# motherboard_schematic_ver_1_0.net
KiCad netlist of a schematic drawn in EAGLE
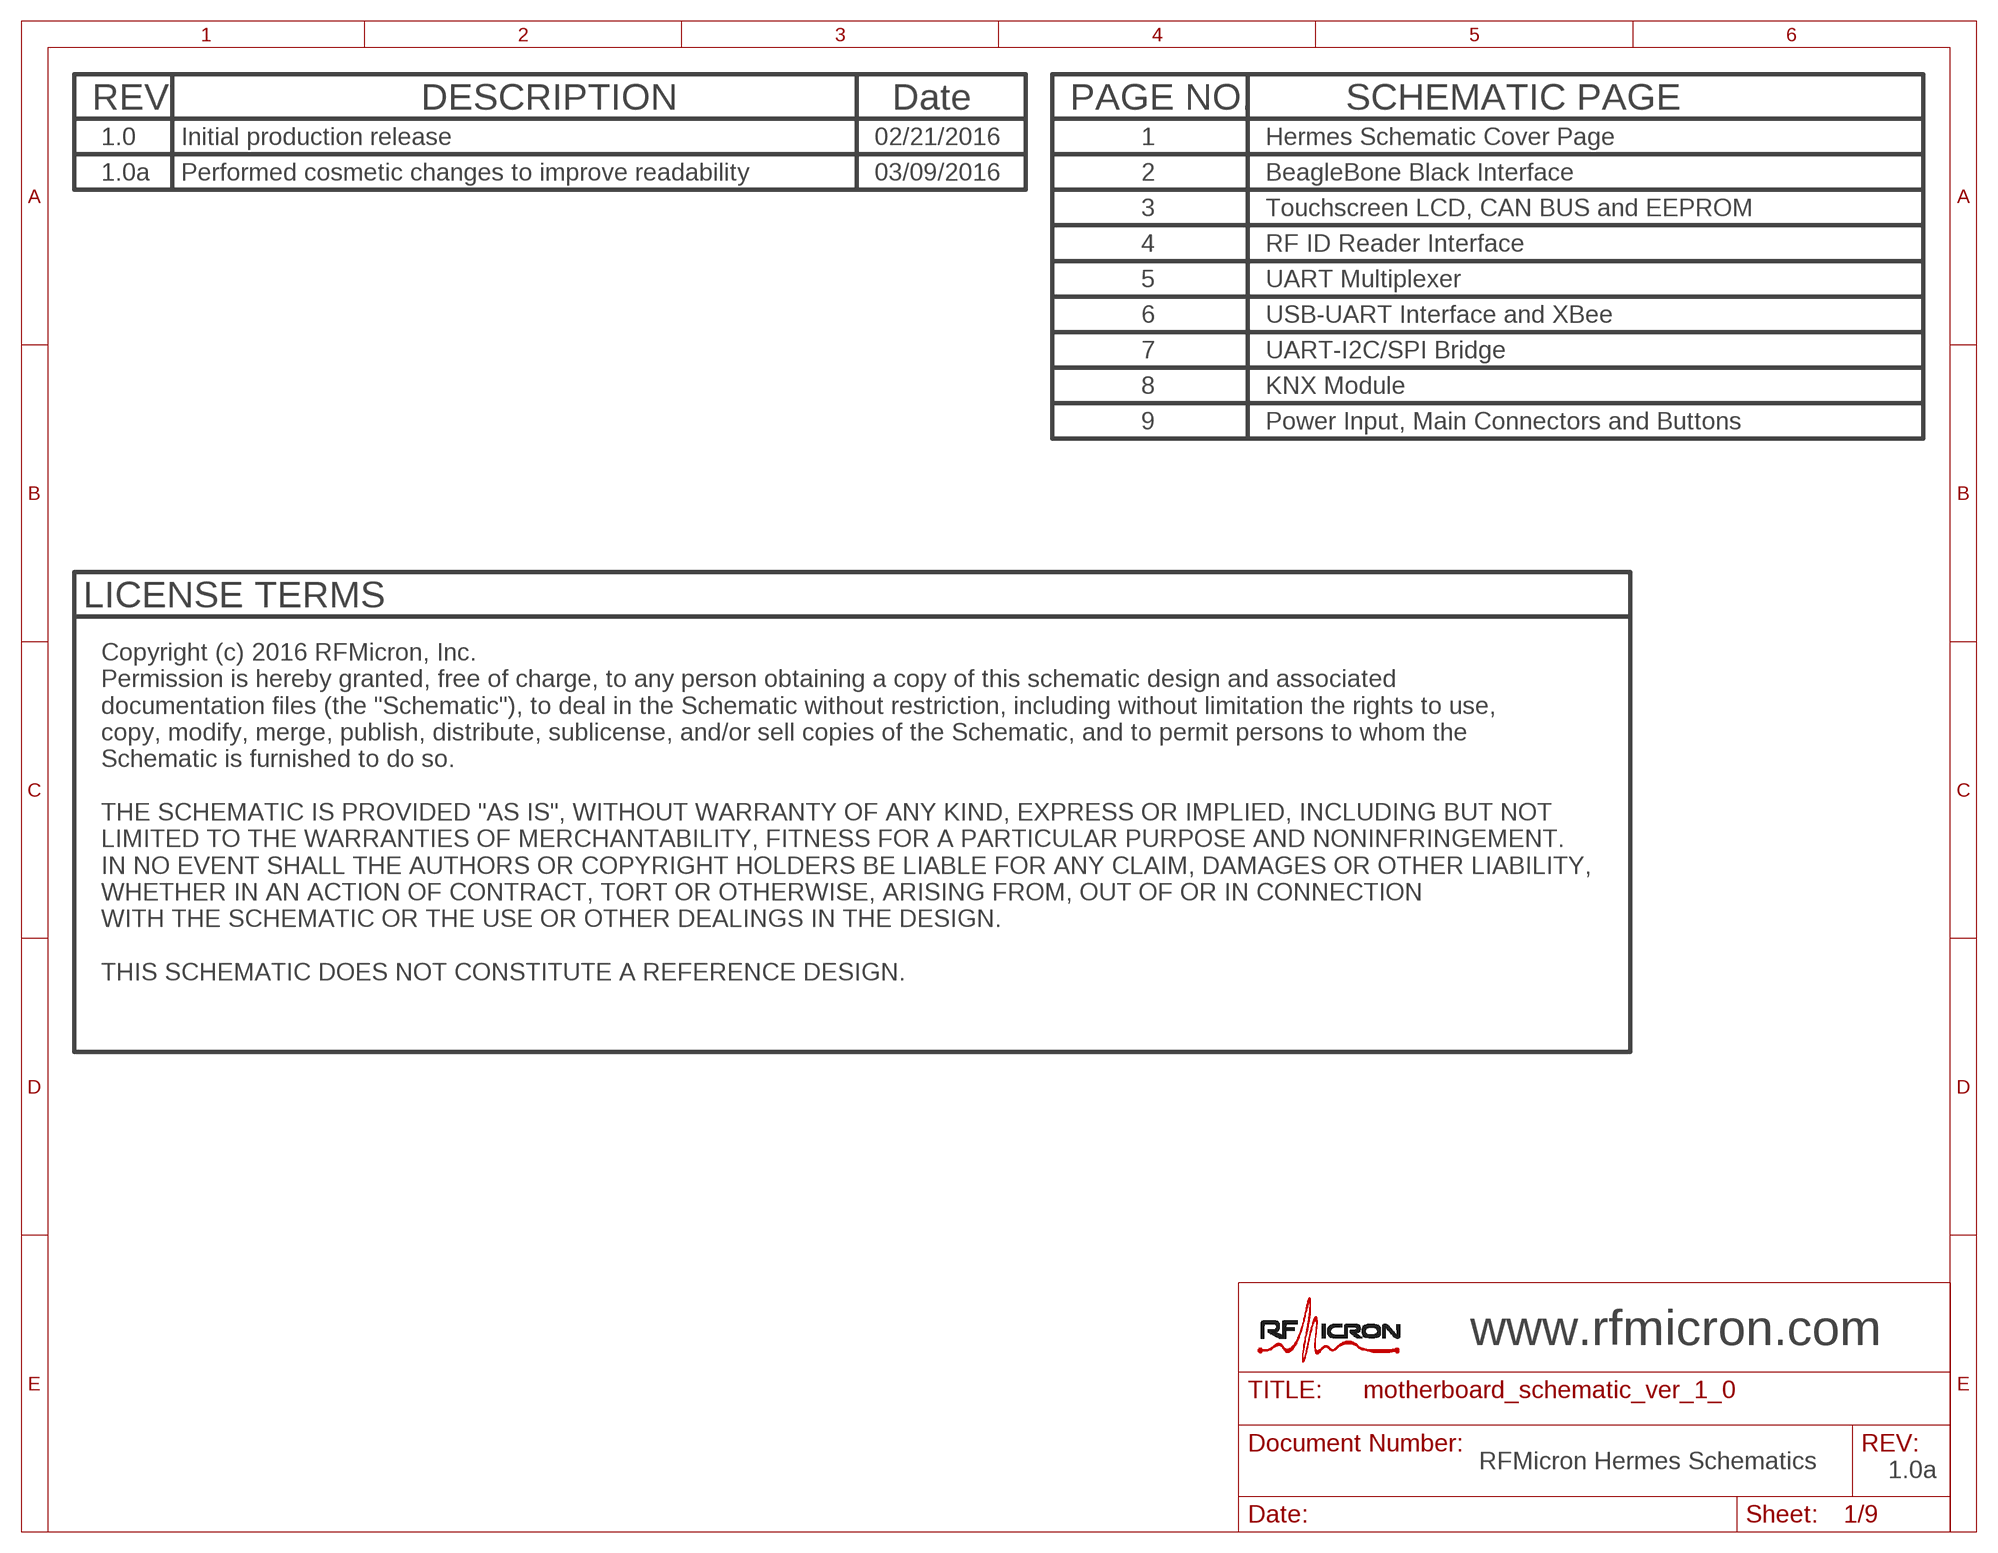
[diagram p0: schematic, sheet 1]
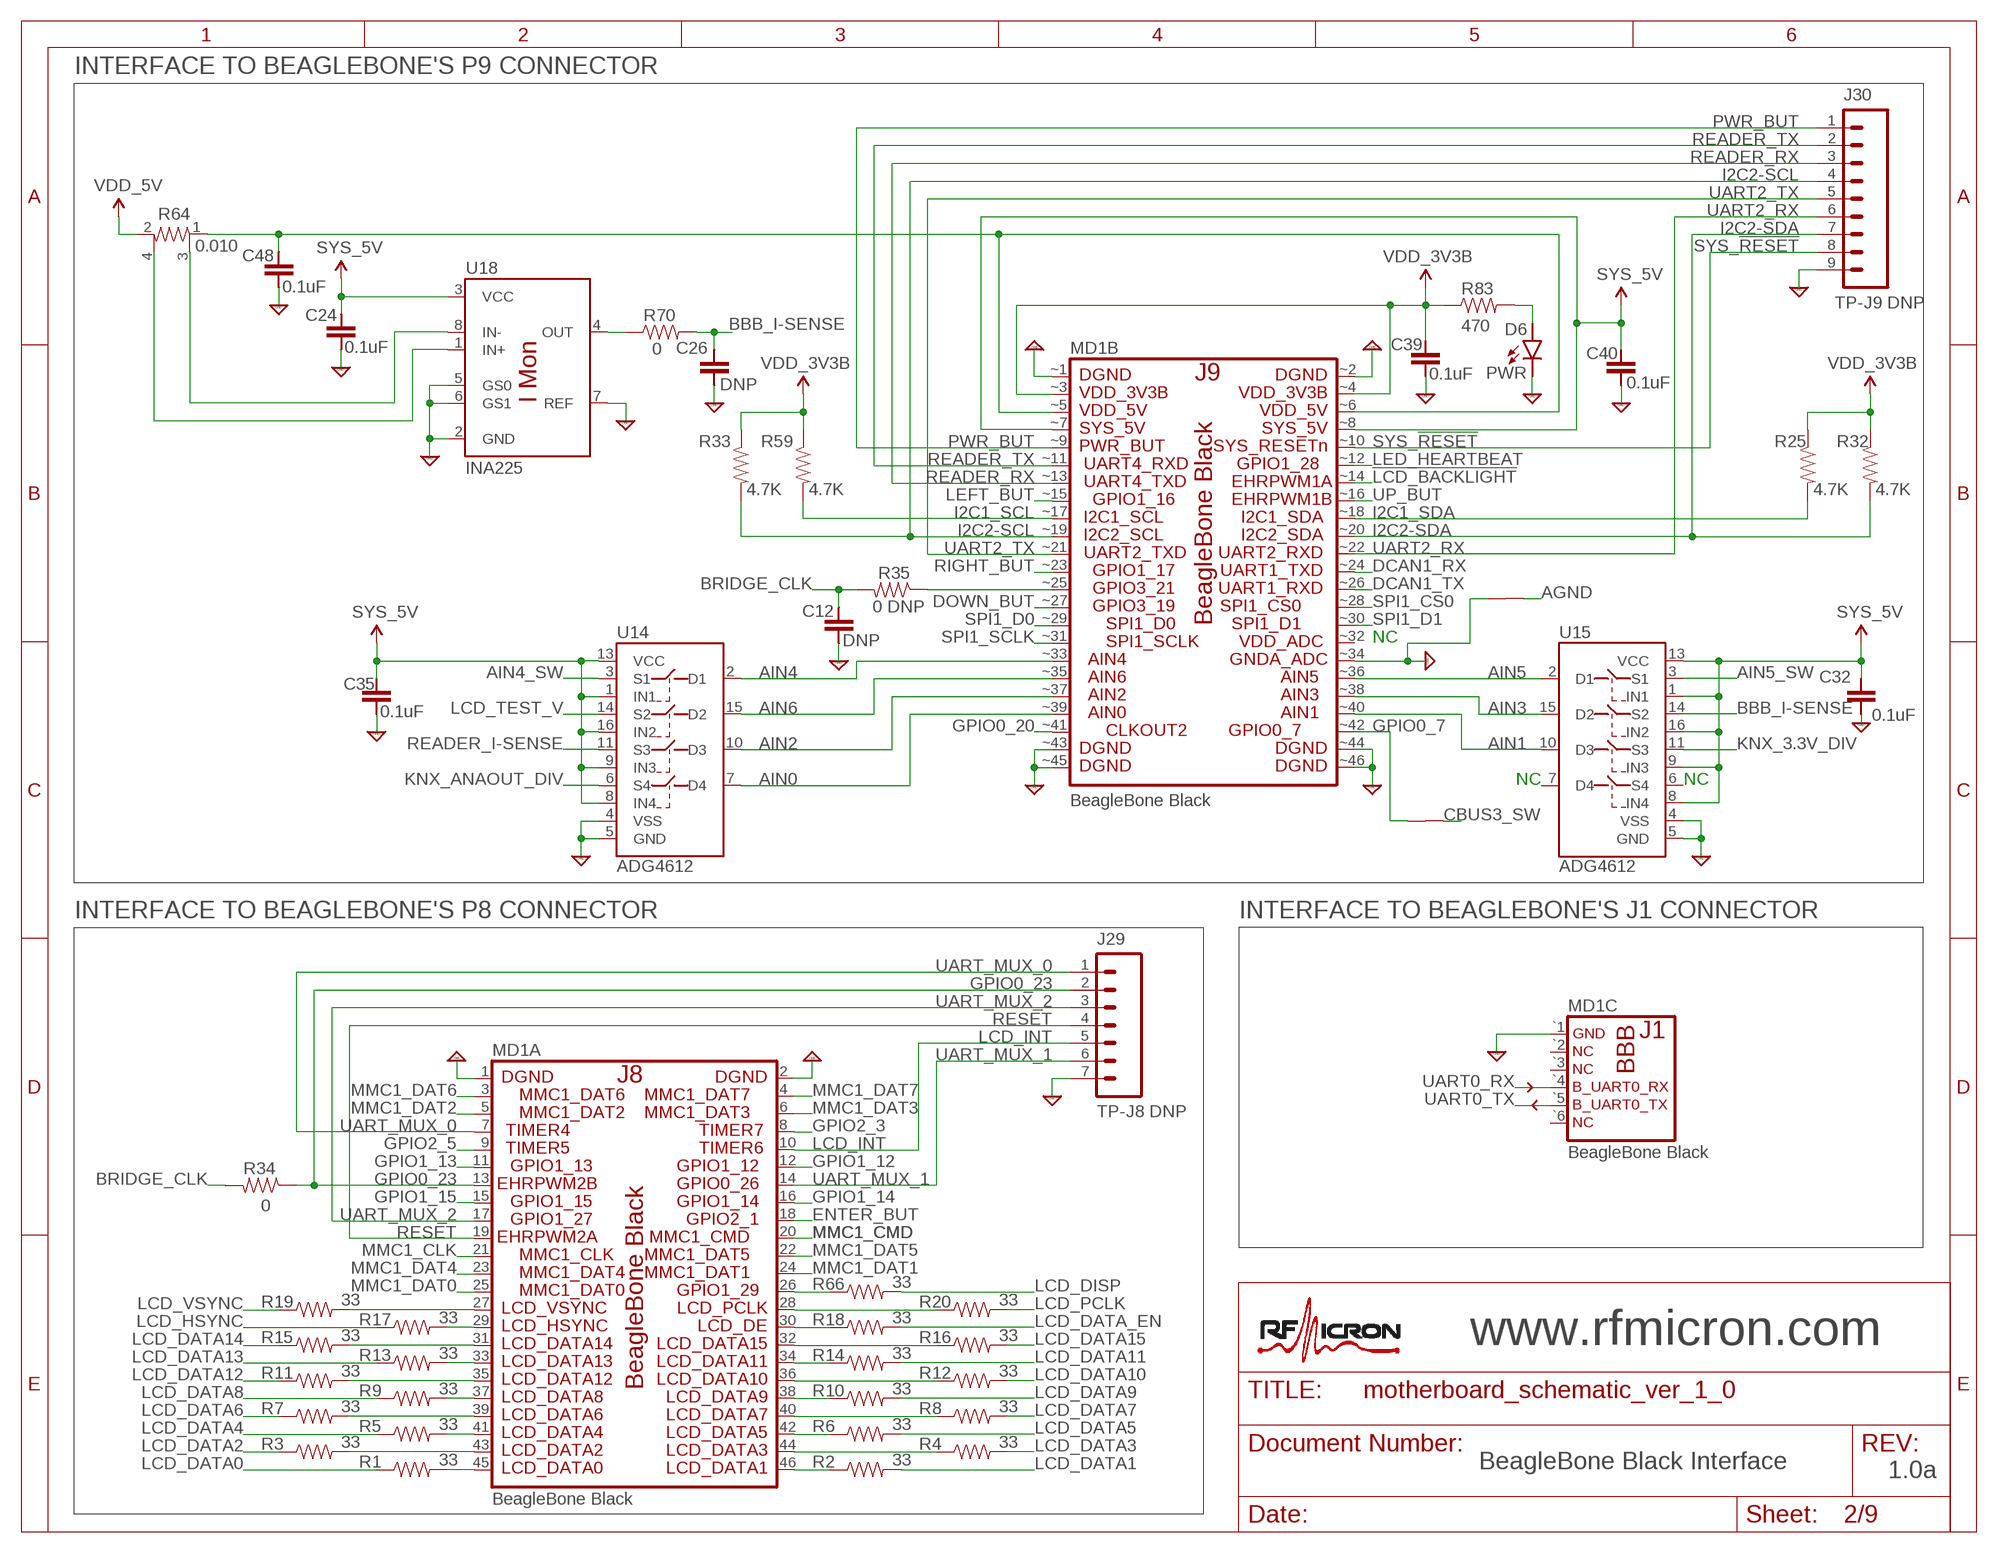
[diagram p1: schematic, sheet 2]
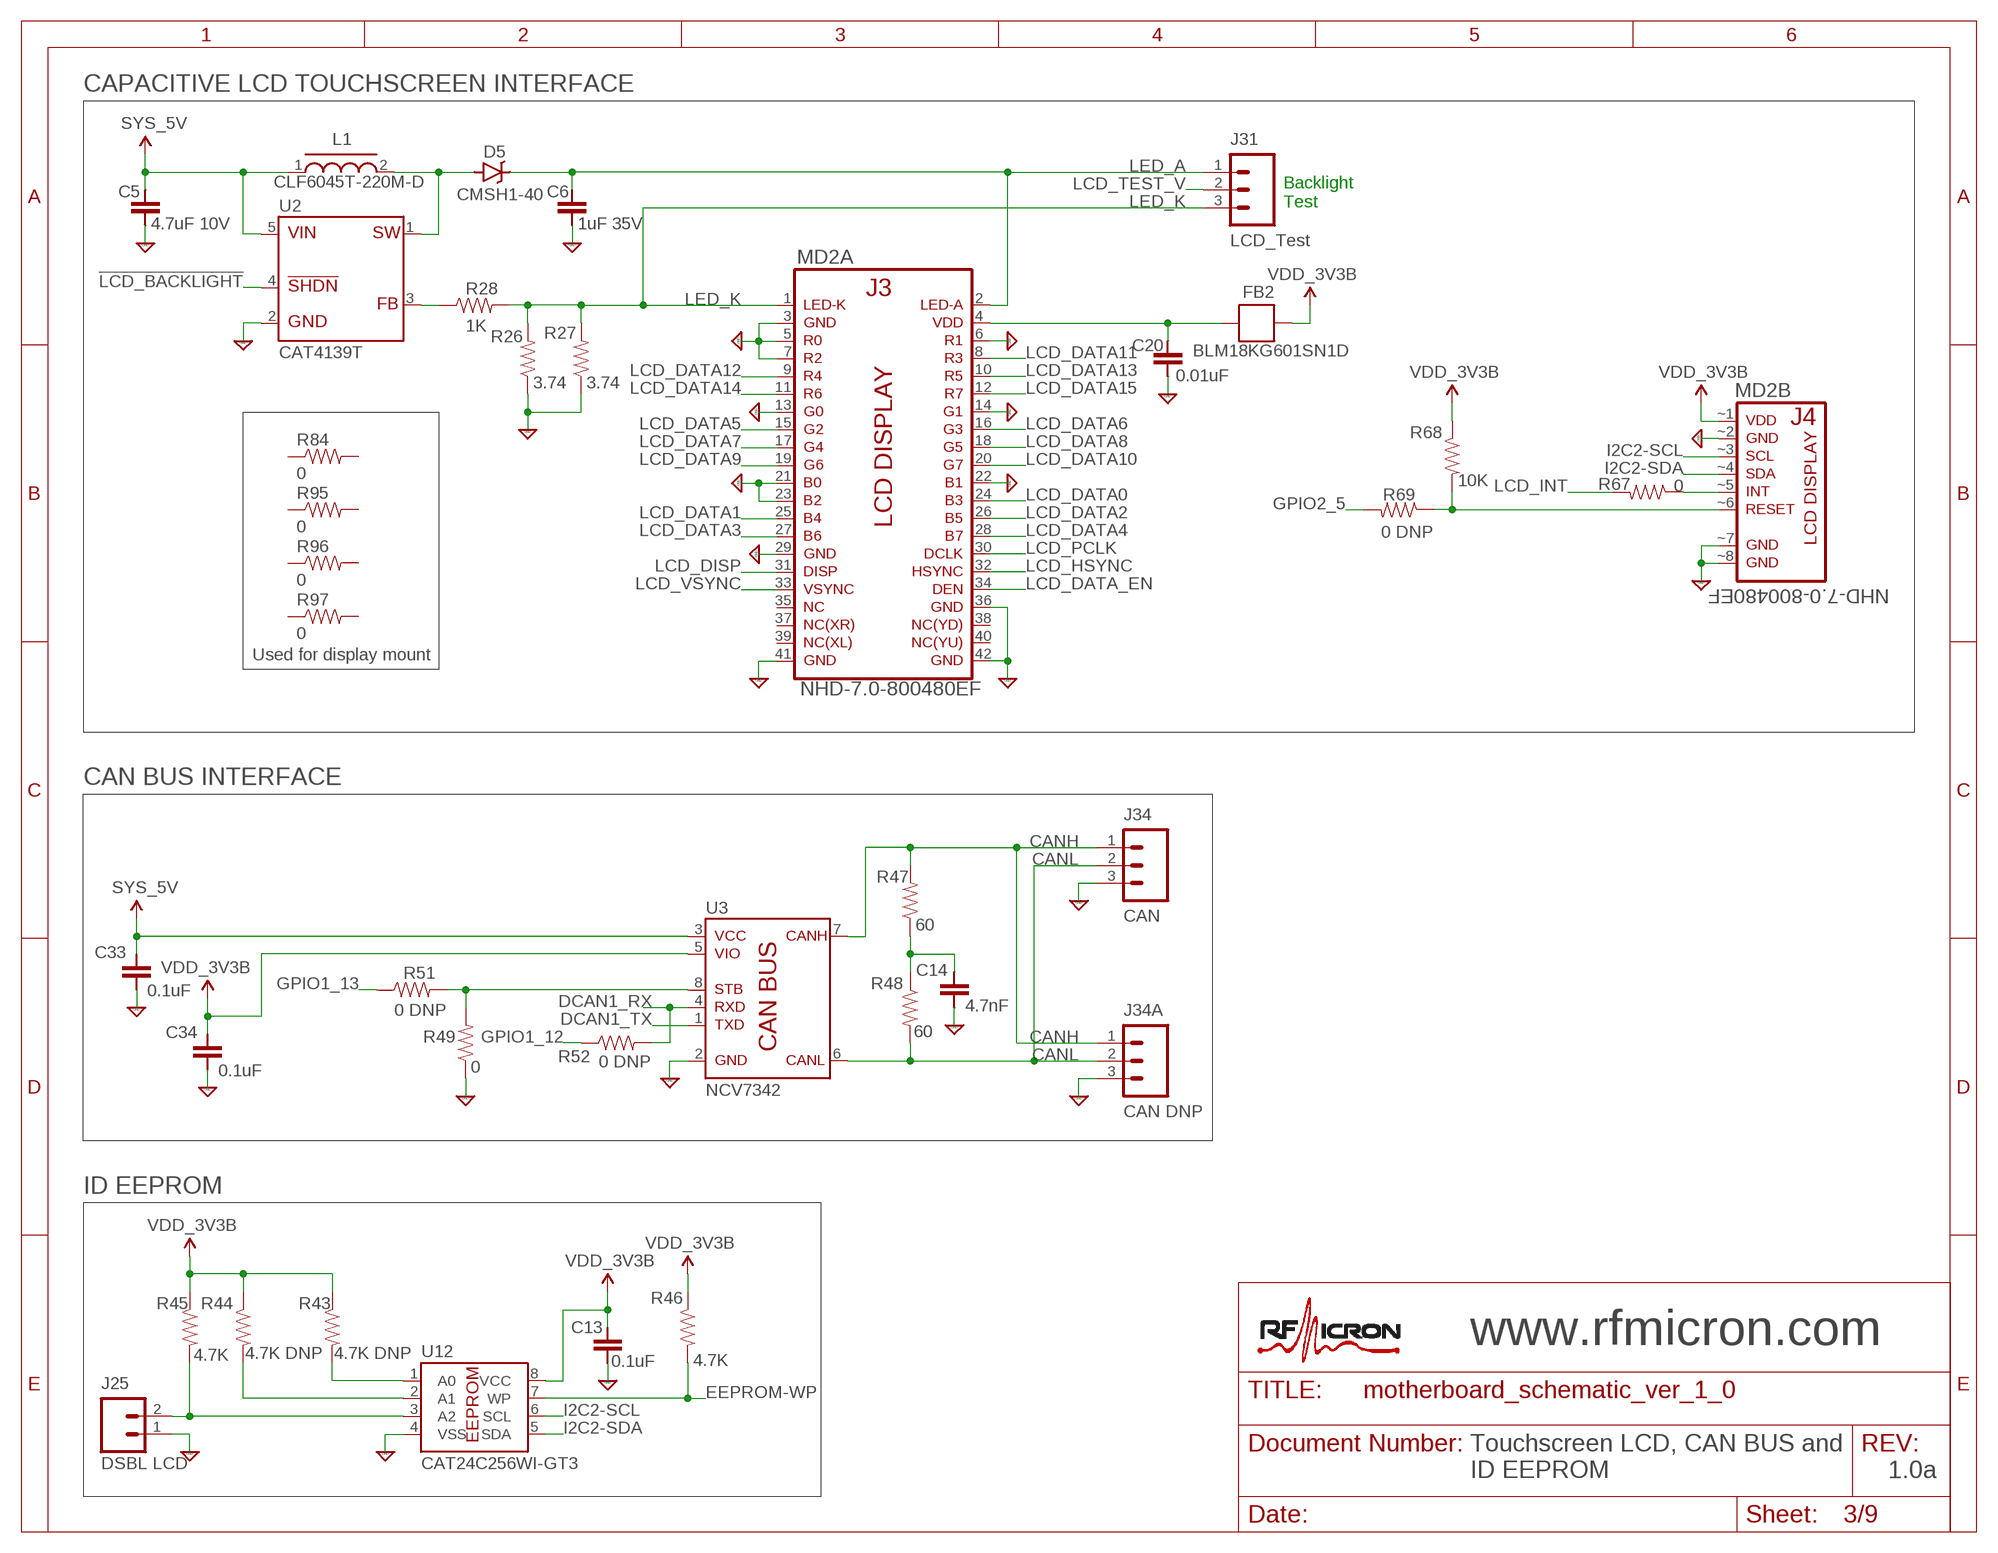
[diagram p2: schematic, sheet 3]
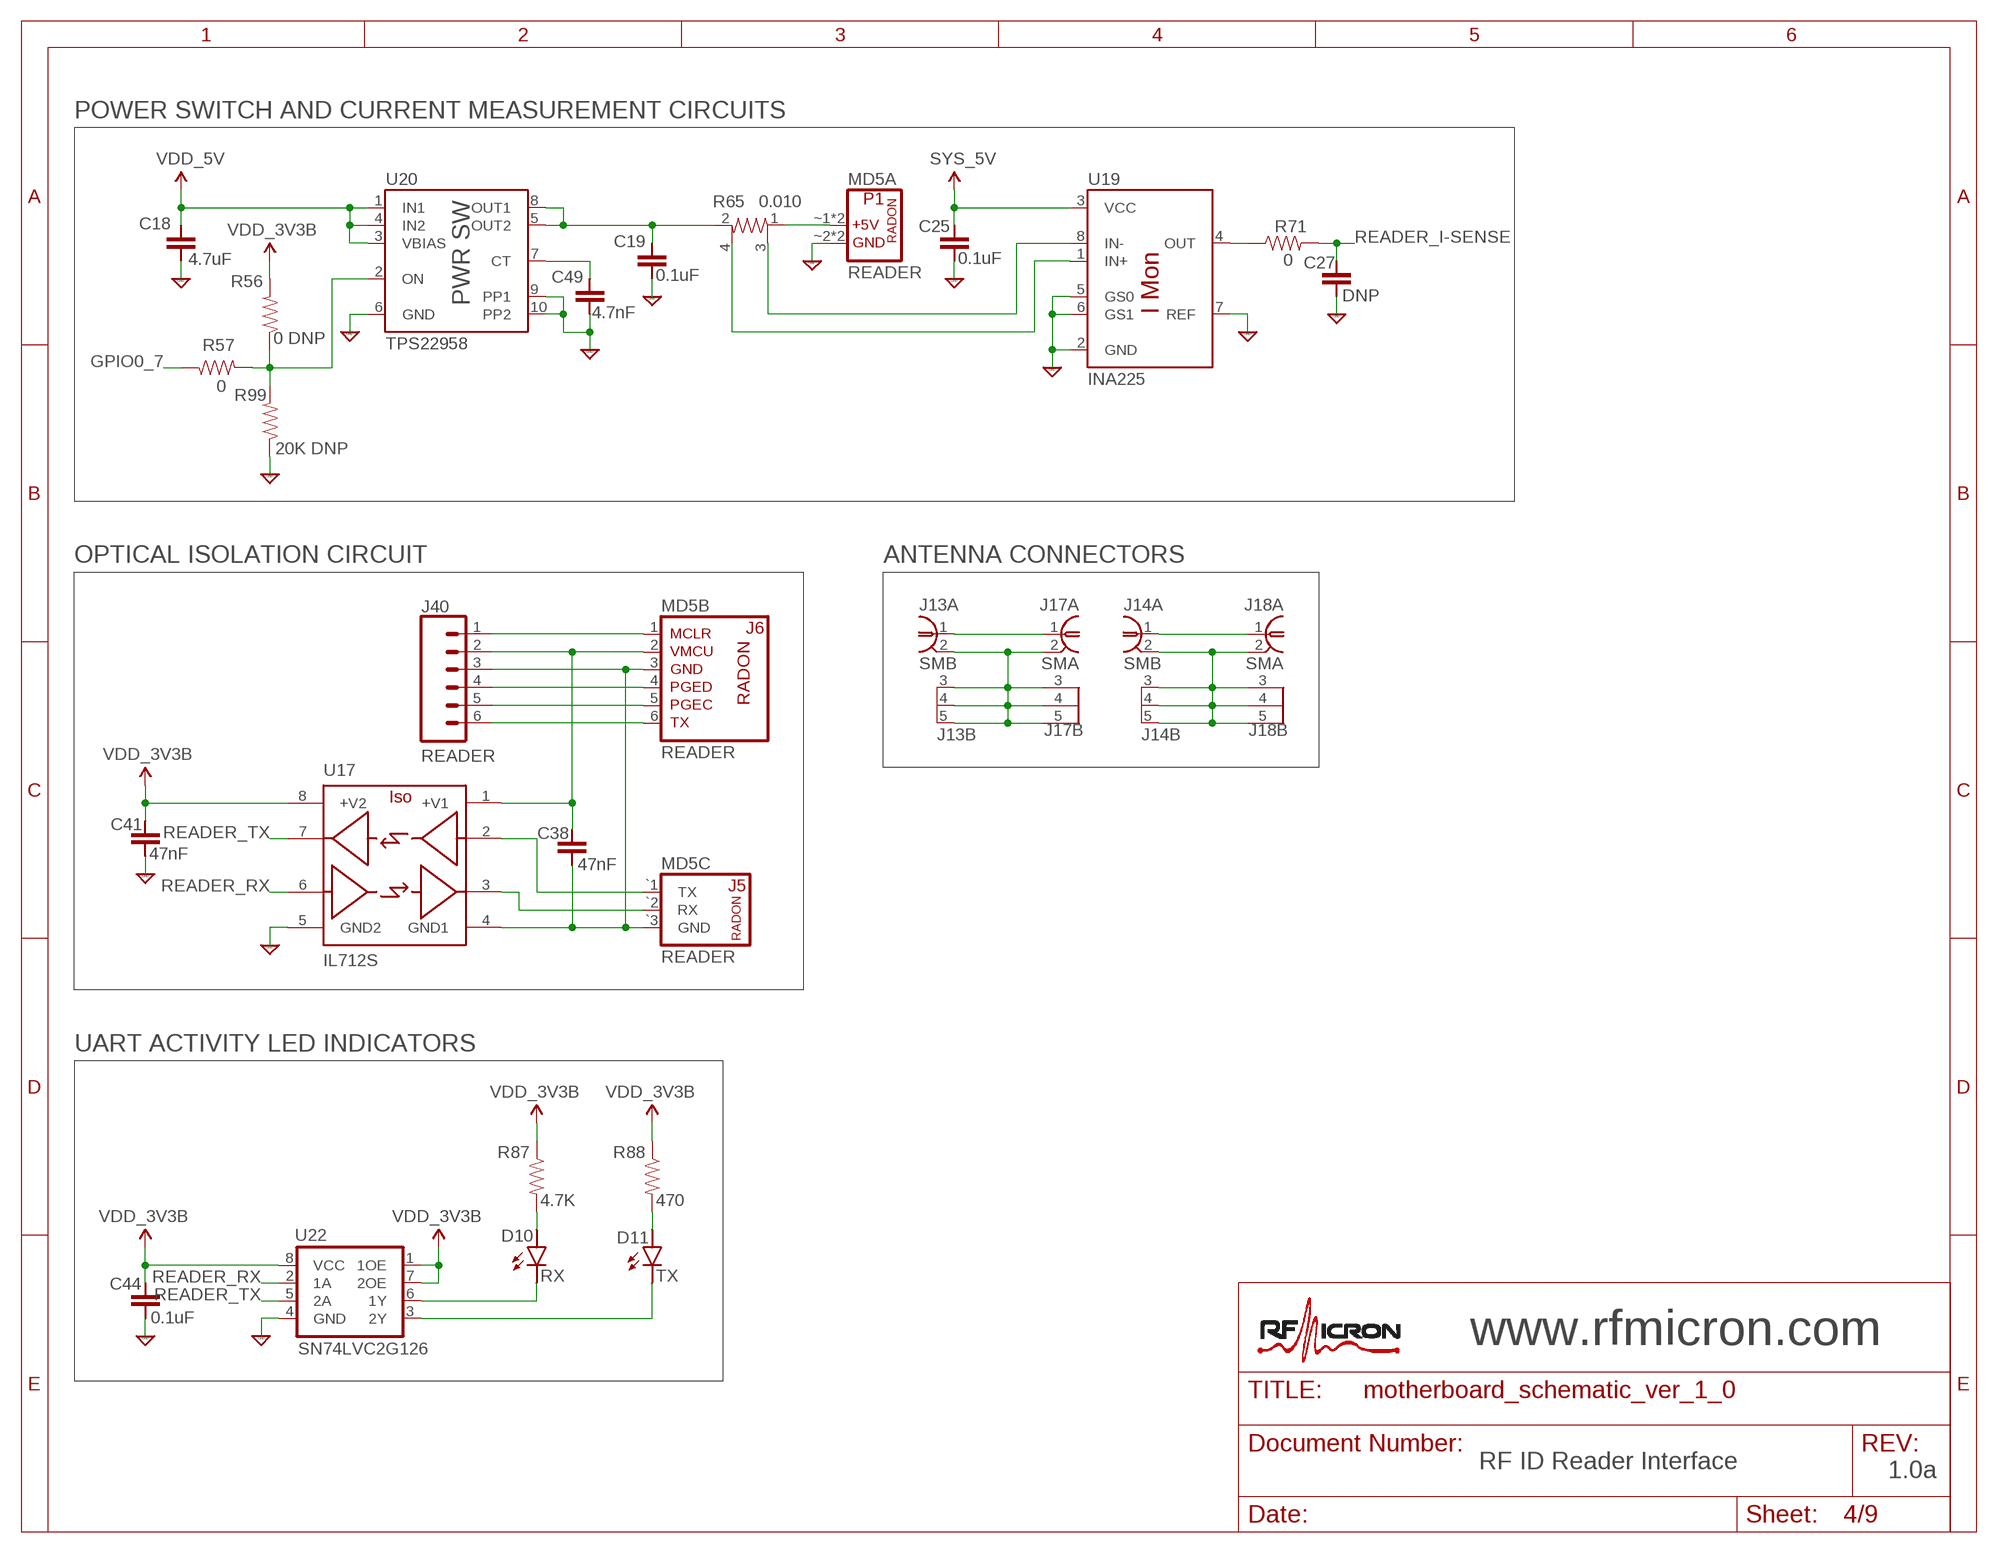
[diagram p3: schematic, sheet 4]
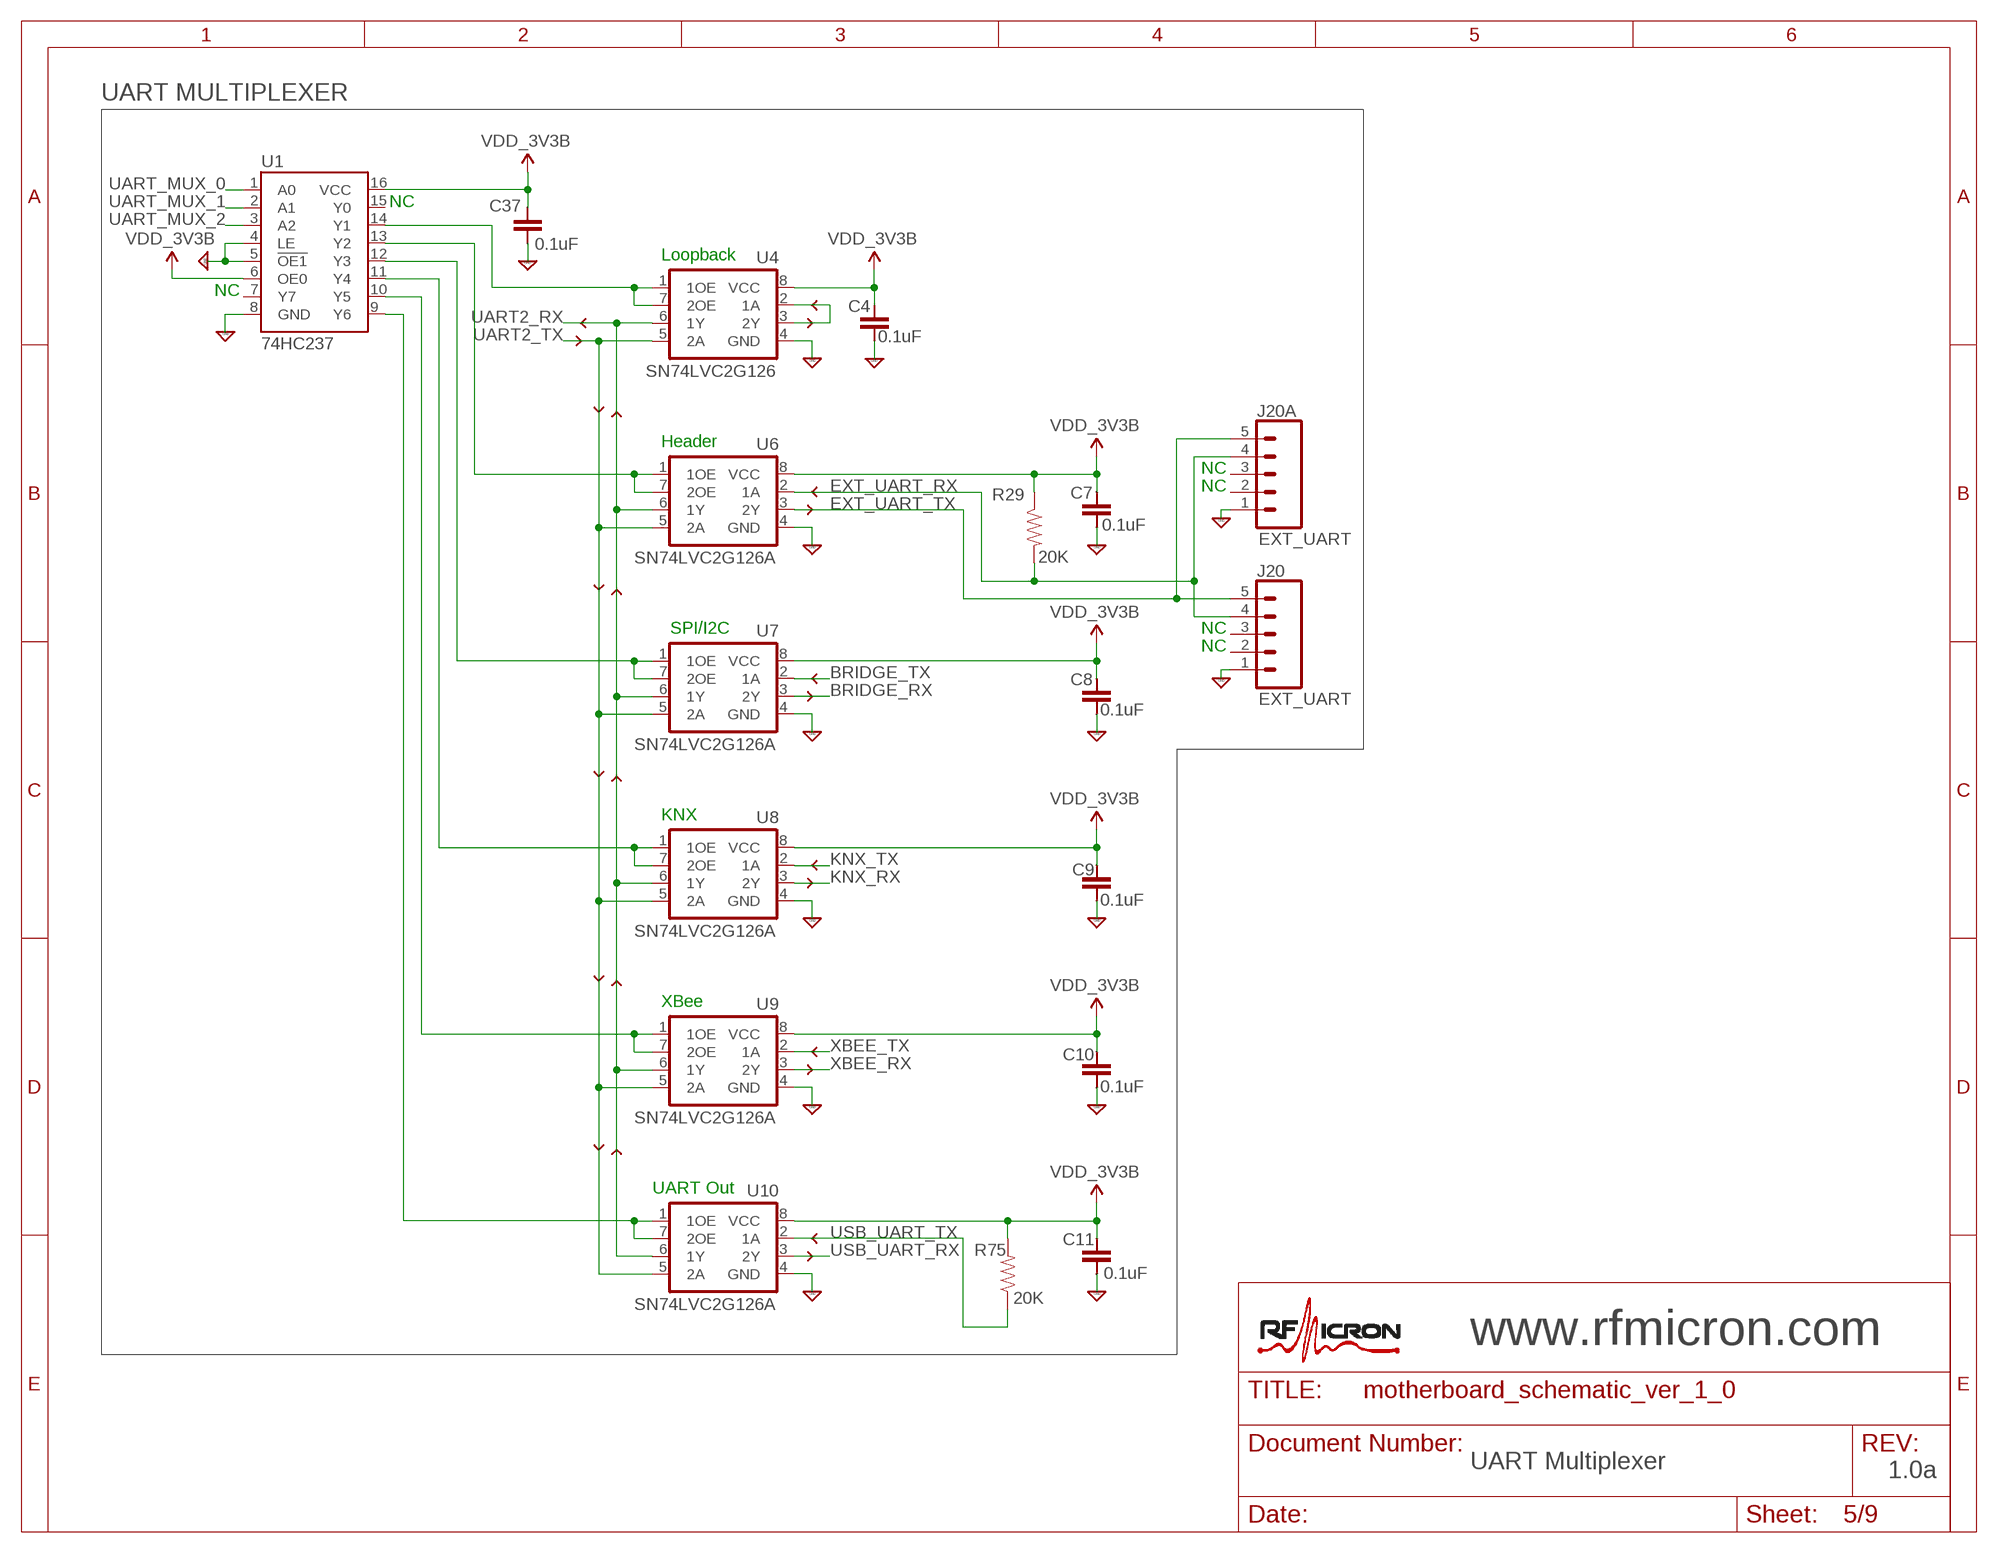
[diagram p4: schematic, sheet 5]
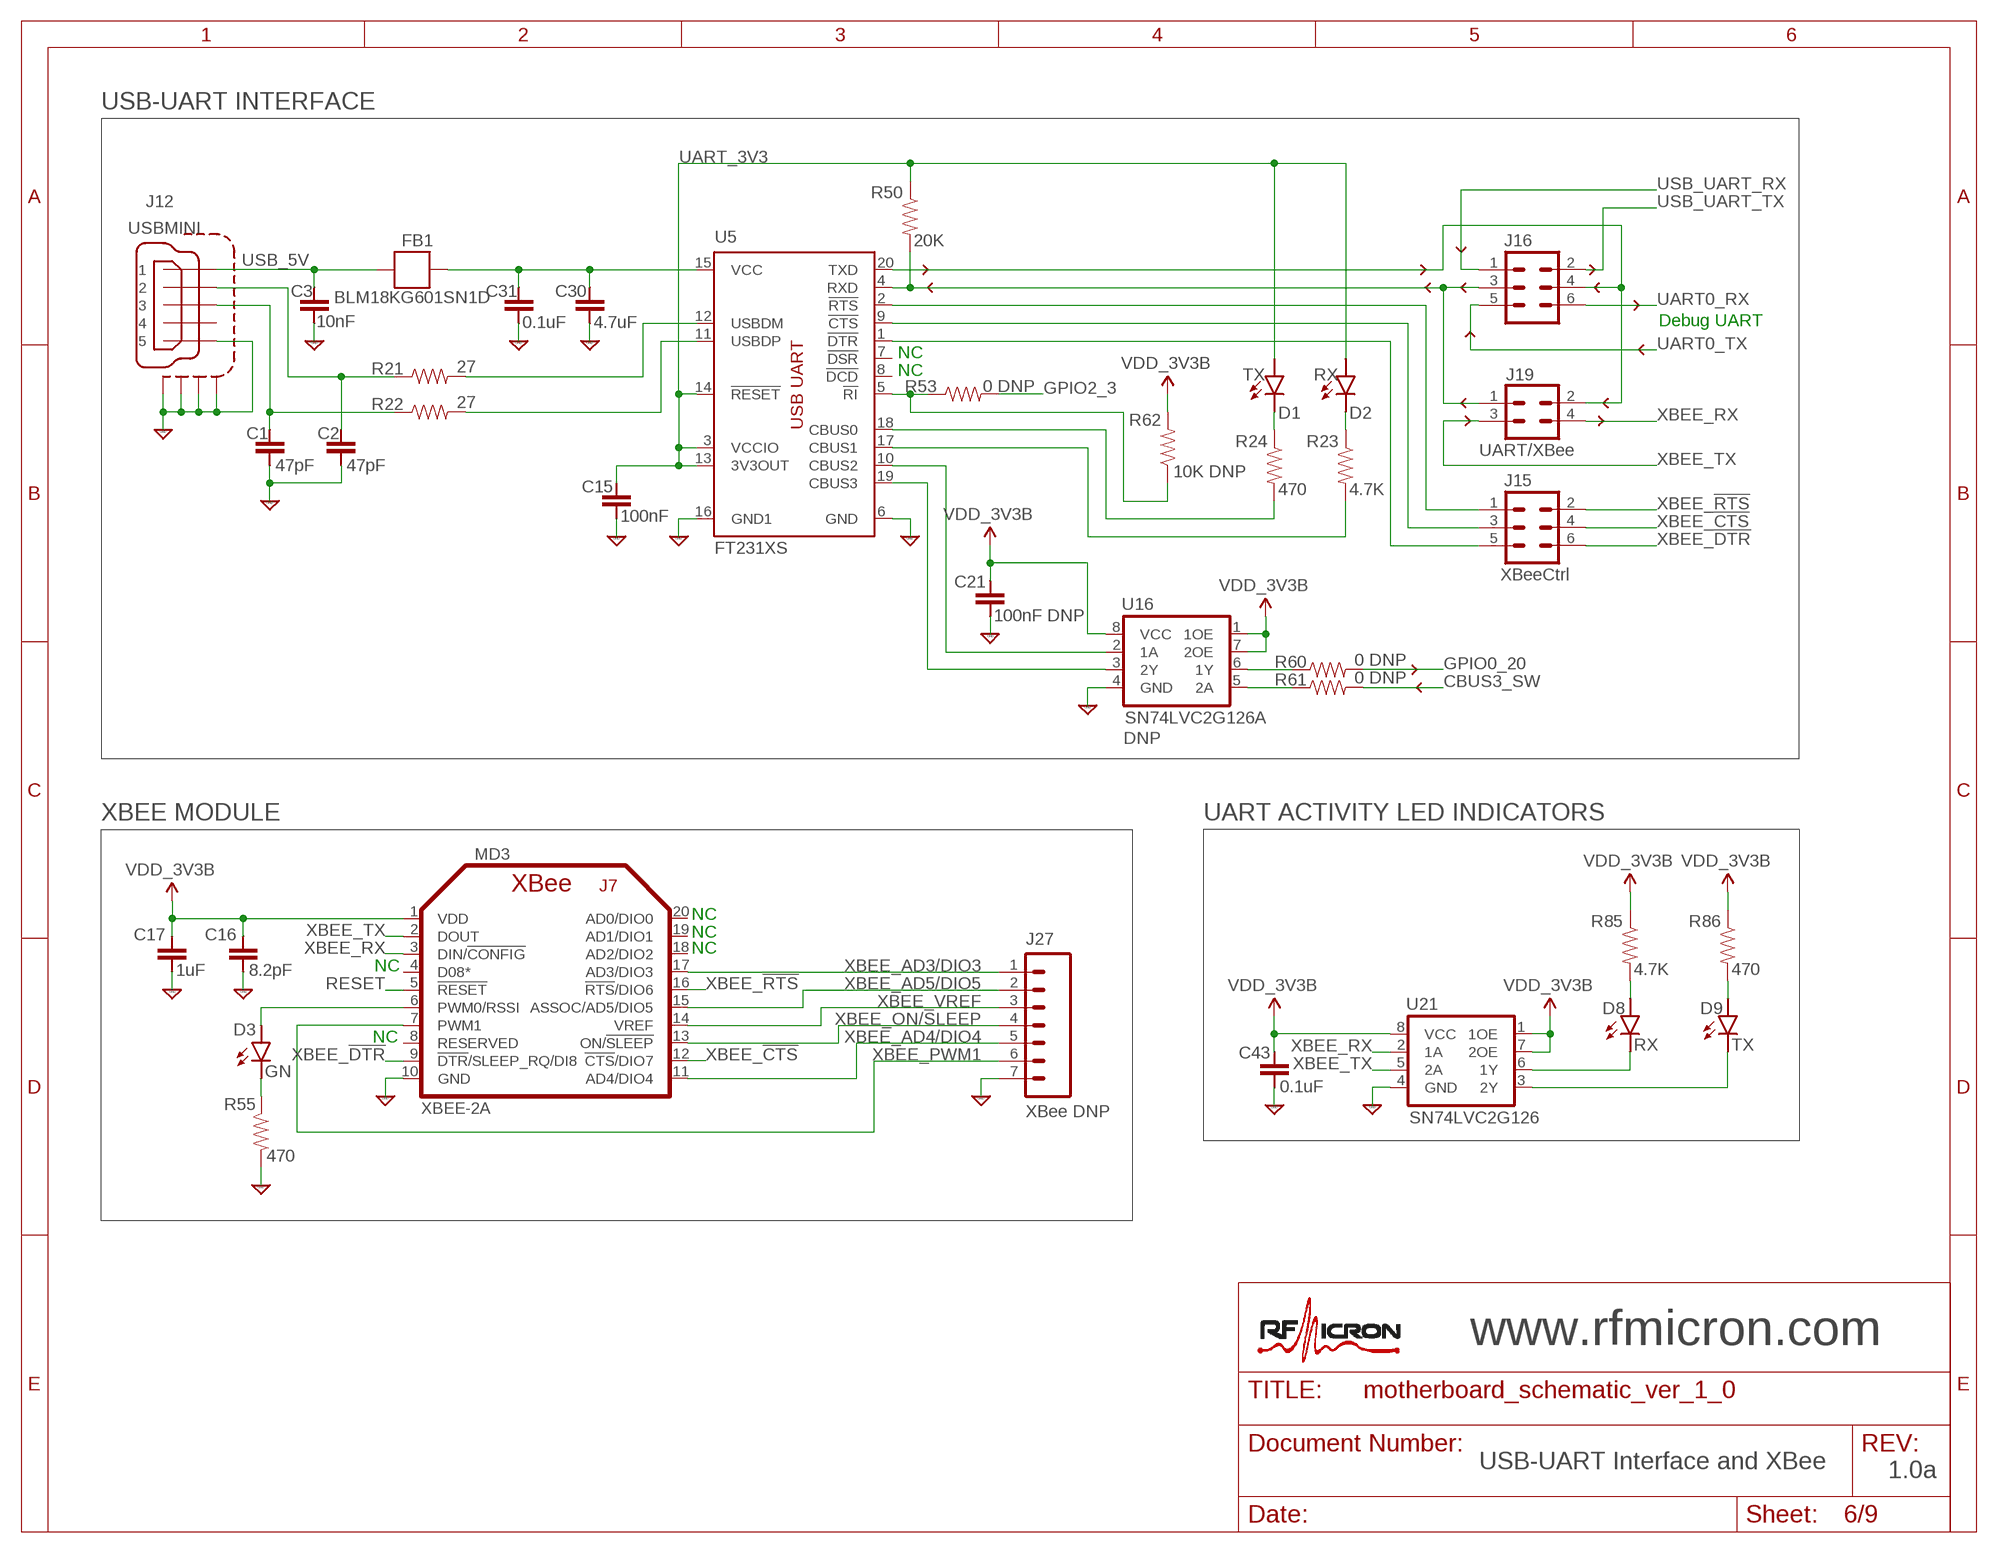
[diagram p5: schematic, sheet 6]
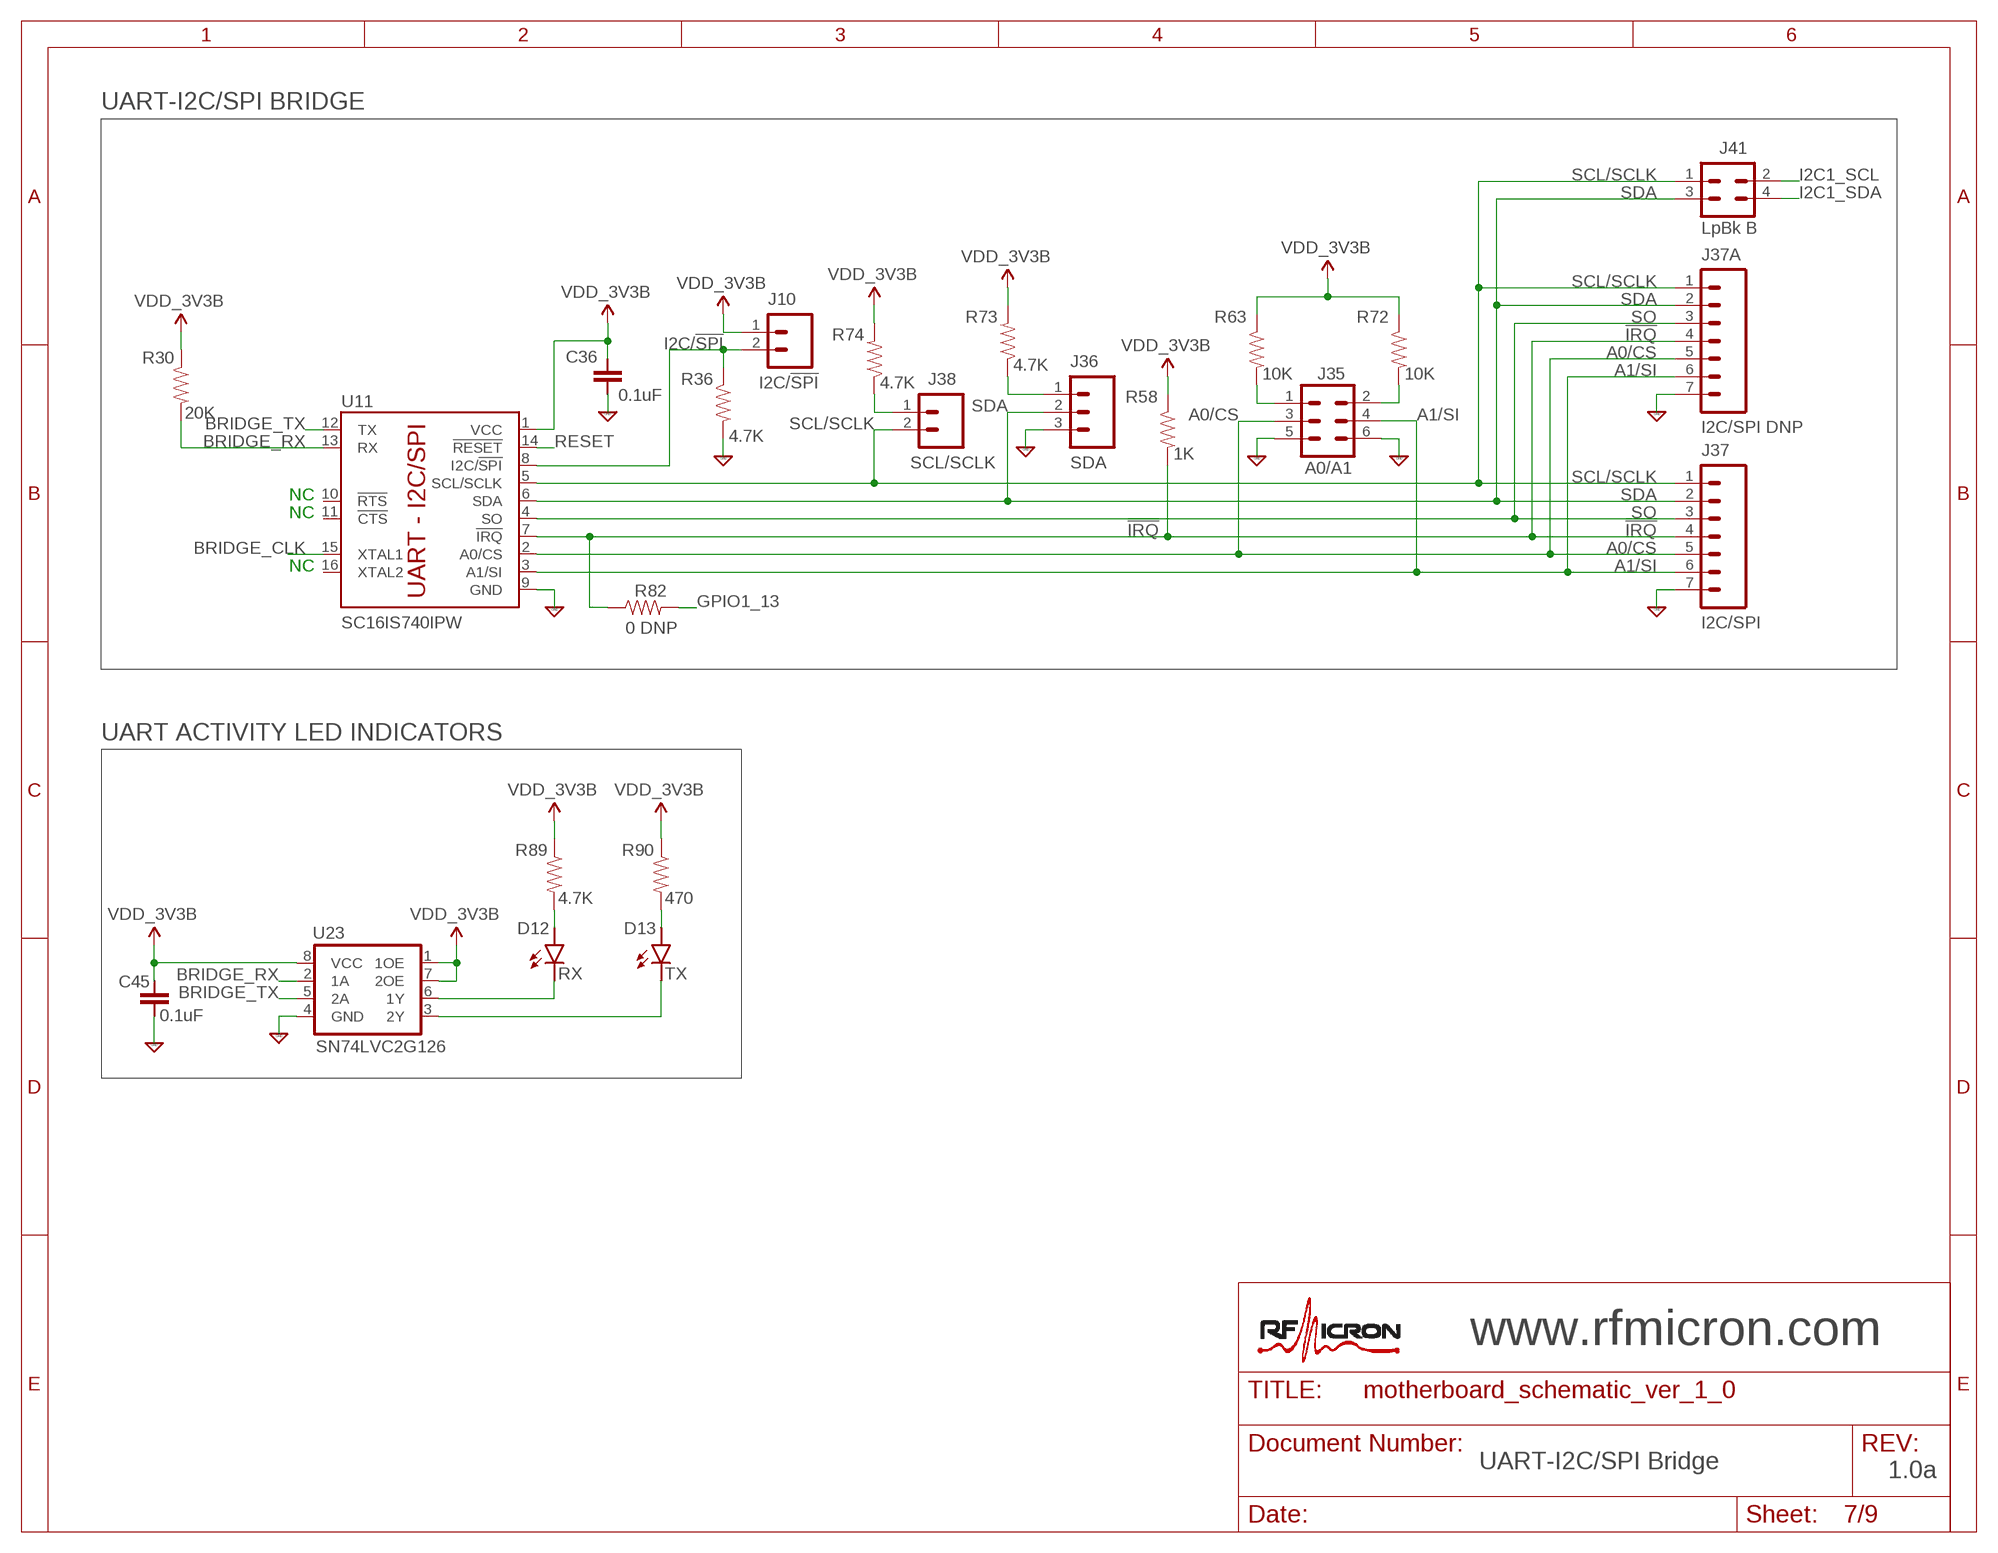
[diagram p6: schematic, sheet 7]
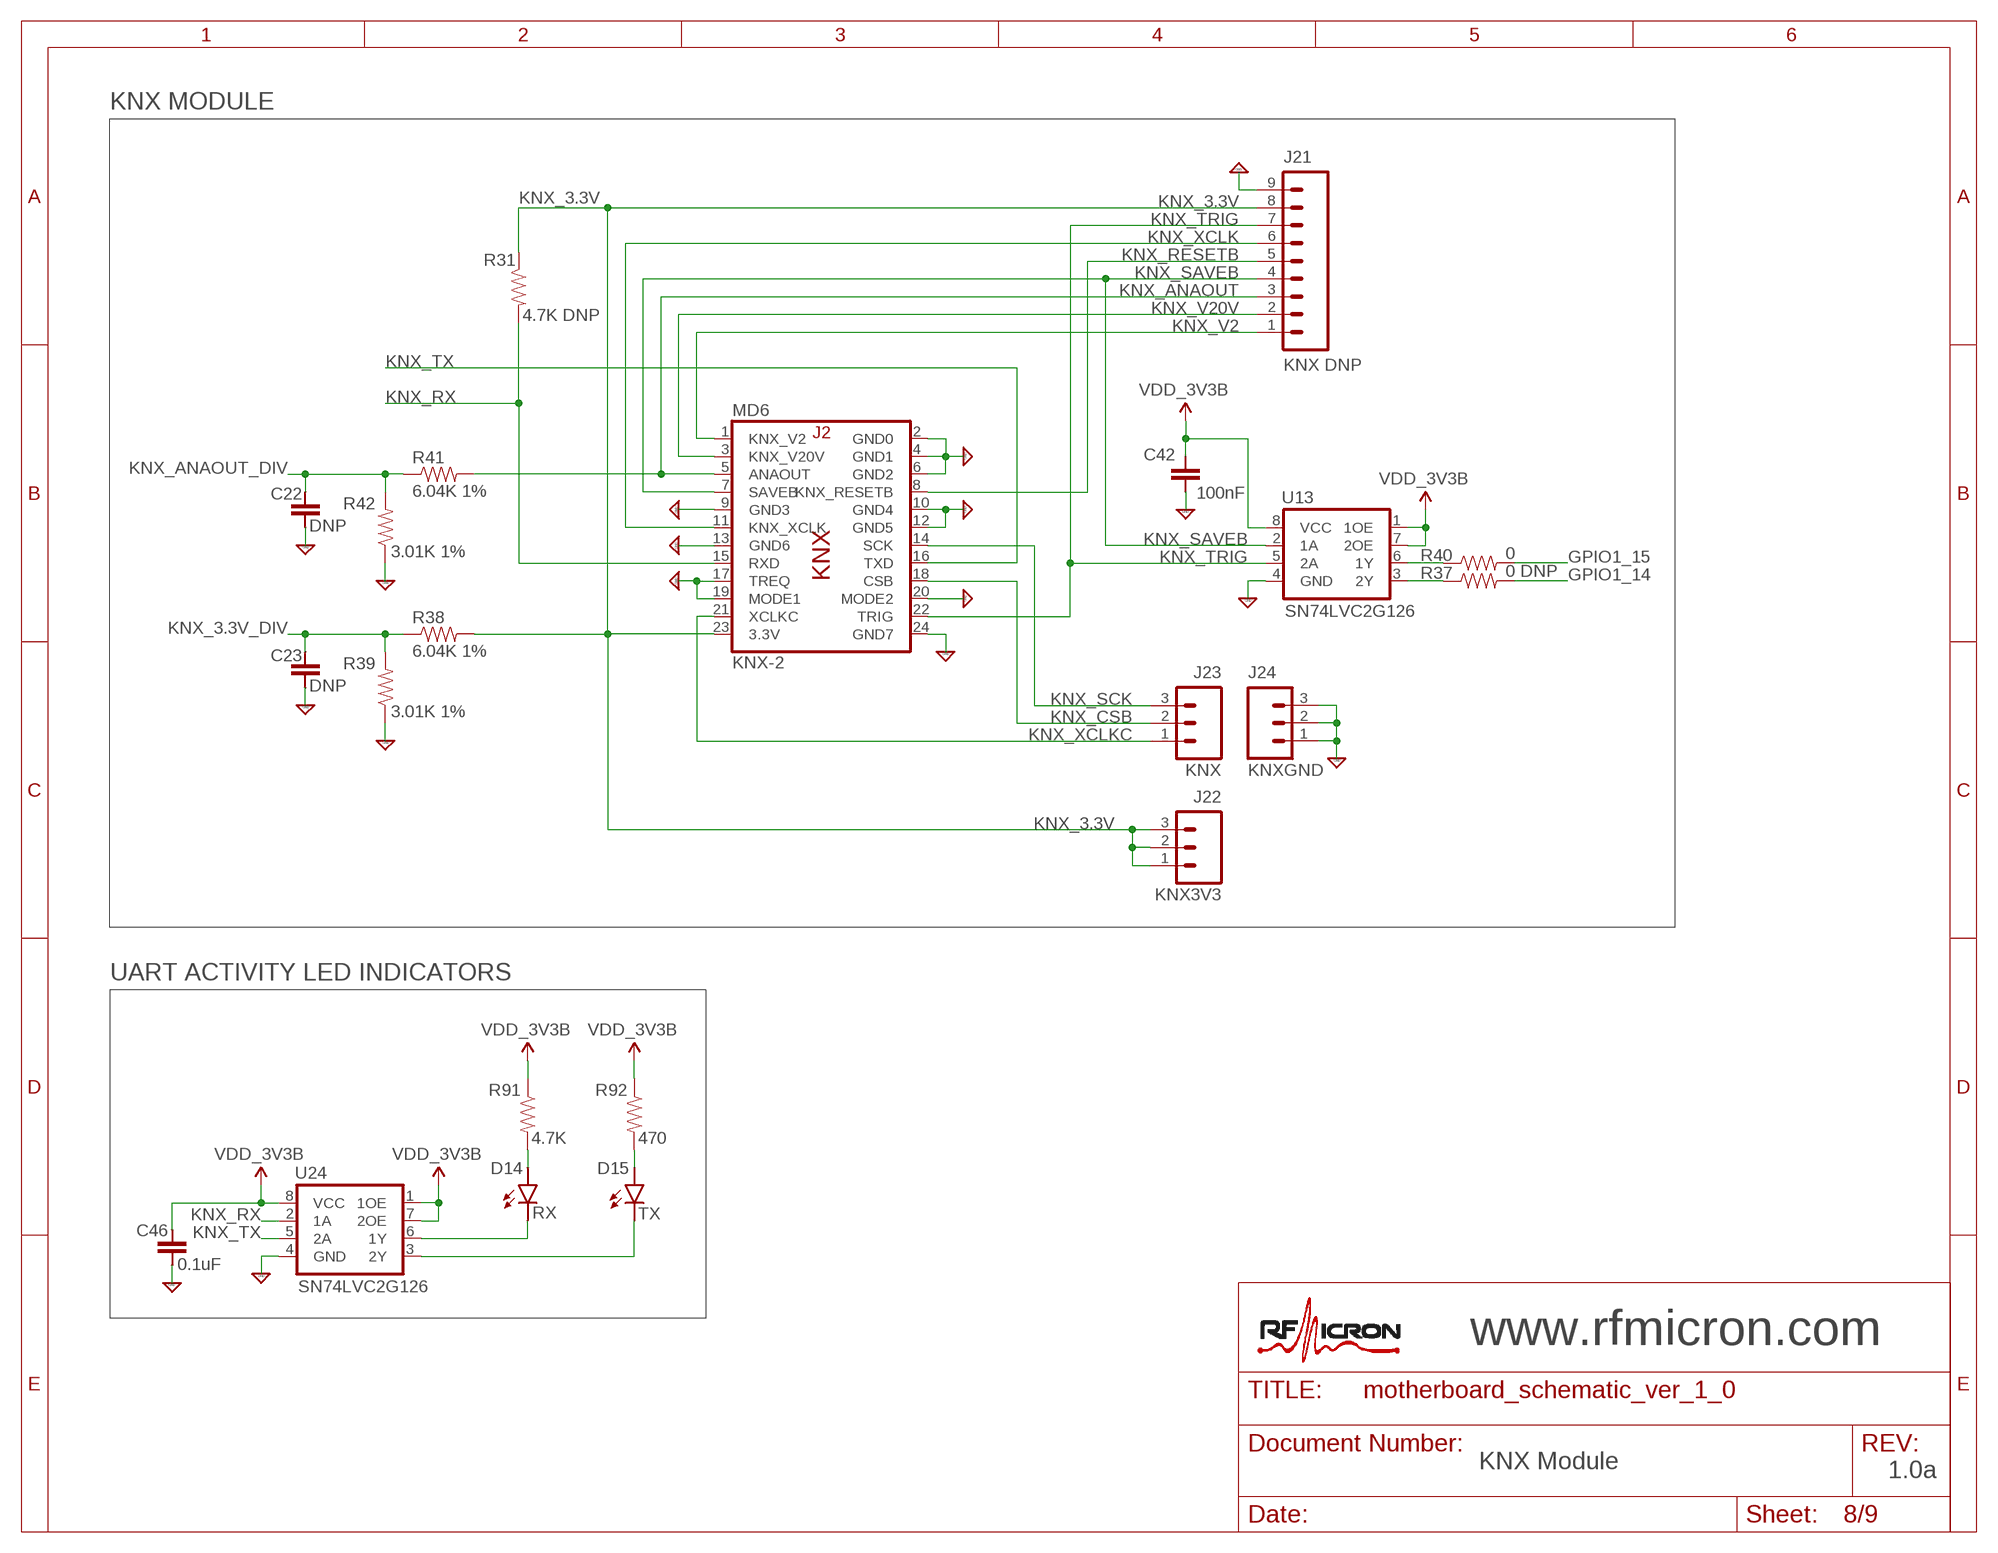
[diagram p7: schematic, sheet 8]
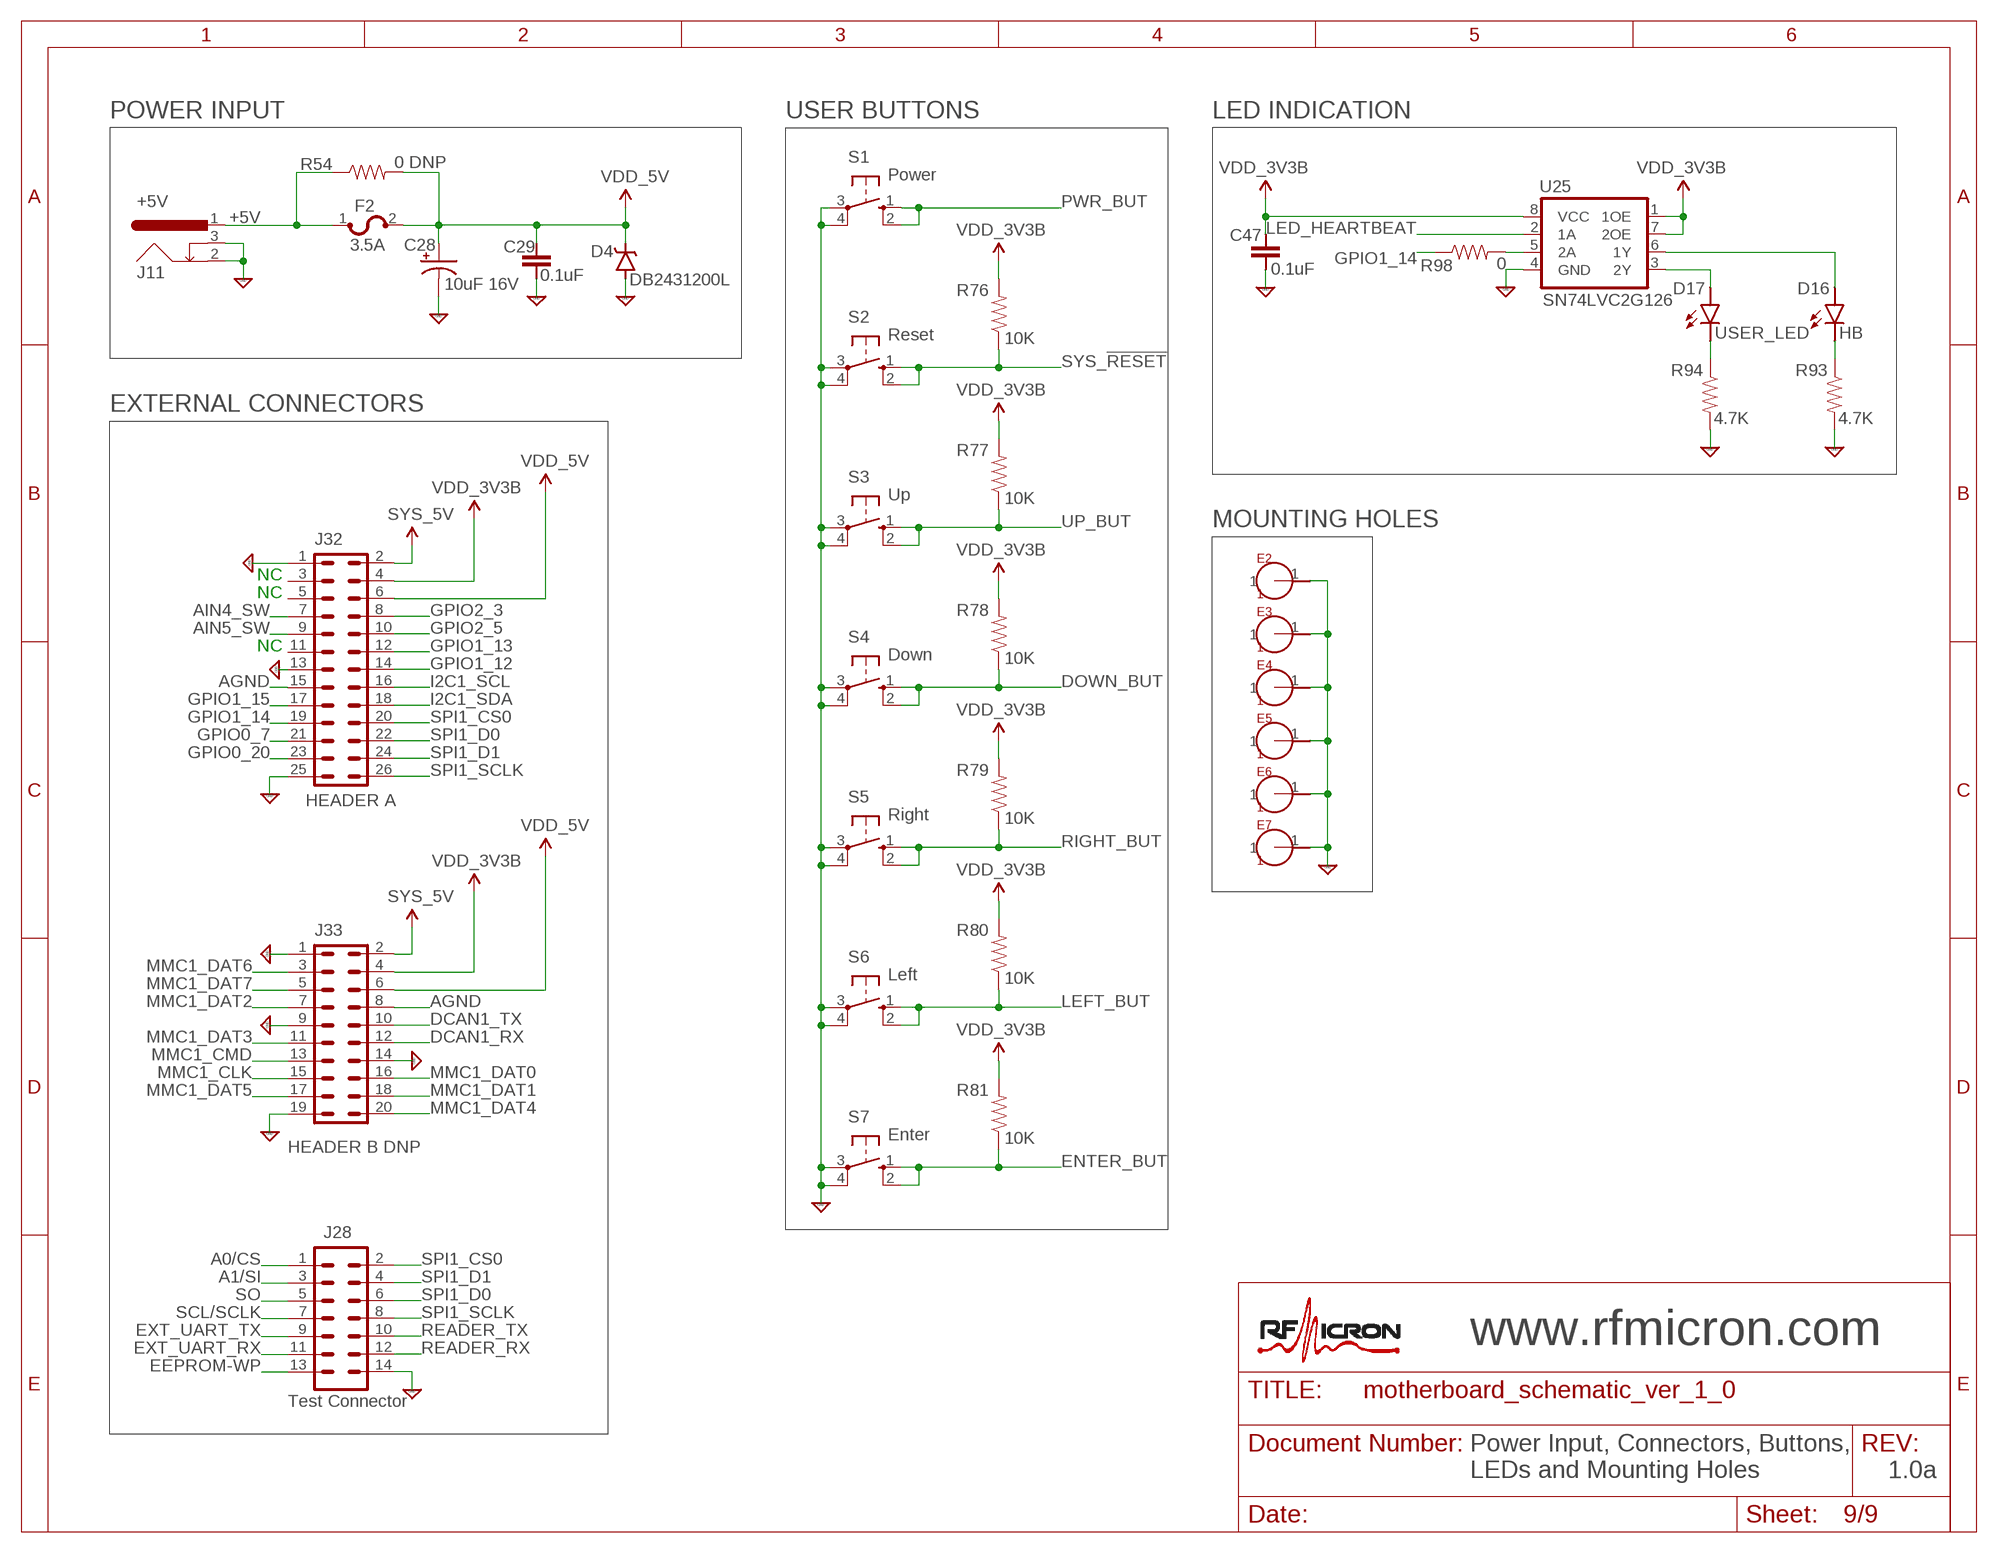
[diagram p8: schematic, sheet 9]

(export (version "E")
  (design (tool "Eeschema 10.0.6"))
  (components
    (comp (ref "C28")
      (value "10uF 16V")
      (footprint "eagle-import:EIA3216")
      (libsource (lib "eagle-import") (part "CAP_POL1206"))
    )
    (comp (ref "C29")
      (value "0.1uF")
      (footprint "eagle-import:0603-CAP")
      (libsource (lib "eagle-import") (part "CAP0603"))
    )
    (comp (ref "C47")
      (value "0.1uF")
      (footprint "eagle-import:0603-CAP")
      (libsource (lib "eagle-import") (part "CAP0603"))
    )
    (comp (ref "D4")
      (value "DB2431200L")
      (footprint "eagle-import:SC-110A-POWER_DIODE")
      (libsource (lib "eagle-import") (part "DIODE-SCHOTTKY3"))
    )
    (comp (ref "D16")
      (value "HB")
      (footprint "eagle-import:LED-1206")
      (libsource (lib "eagle-import") (part "LED1206"))
    )
    (comp (ref "D17")
      (value "USER_LED")
      (footprint "eagle-import:LED-1206")
      (libsource (lib "eagle-import") (part "LED1206"))
    )
    (comp (ref "E2")
      (value "1")
      (footprint "eagle-import:MTHOLE4-40")
      (libsource (lib "eagle-import") (part "HOLE-MOUNT1"))
    )
    (comp (ref "E3")
      (value "1")
      (footprint "eagle-import:MTHOLE4-40")
      (libsource (lib "eagle-import") (part "HOLE-MOUNT1"))
    )
    (comp (ref "E4")
      (value "1")
      (footprint "eagle-import:MTHOLE4-40")
      (libsource (lib "eagle-import") (part "HOLE-MOUNT1"))
    )
    (comp (ref "E5")
      (value "1")
      (footprint "eagle-import:MTHOLE4-40")
      (libsource (lib "eagle-import") (part "HOLE-MOUNT1"))
    )
    (comp (ref "E6")
      (value "1")
      (footprint "eagle-import:MTHOLE4-40")
      (libsource (lib "eagle-import") (part "HOLE-MOUNT1"))
    )
    (comp (ref "E7")
      (value "1")
      (footprint "eagle-import:MTHOLE4-40")
      (libsource (lib "eagle-import") (part "HOLE-MOUNT1"))
    )
    (comp (ref "F2")
      (value "3.5A")
      (footprint "eagle-import:FUSE_OMNI-BLOCK-154")
      (libsource (lib "eagle-import") (part "FUSE_OMNI-BLOCK-154-SM"))
    )
    (comp (ref "J11")
      (value "+5V")
      (footprint "eagle-import:POWER_JACK_PTH")
      (libsource (lib "eagle-import") (part "POWER_JACKPTH"))
    )
    (comp (ref "J28")
      (value "Test Connector")
      (footprint "eagle-import:2X7SM")
      (libsource (lib "eagle-import") (part "M2X7SM"))
    )
    (comp (ref "J32")
      (value "HEADER A")
      (footprint "eagle-import:2X13-SM")
      (libsource (lib "eagle-import") (part "M2X13SM"))
    )
    (comp (ref "J33")
      (value "HEADER B DNP")
      (footprint "eagle-import:2X10SM")
      (libsource (lib "eagle-import") (part "M10X2SM"))
    )
    (comp (ref "R54")
      (value "0 DNP")
      (footprint "eagle-import:1206")
      (libsource (lib "eagle-import") (part "RESISTOR1206"))
    )
    (comp (ref "R76")
      (value "10K")
      (footprint "eagle-import:0603-RES")
      (libsource (lib "eagle-import") (part "RESISTOR0603"))
    )
    (comp (ref "R77")
      (value "10K")
      (footprint "eagle-import:0603-RES")
      (libsource (lib "eagle-import") (part "RESISTOR0603"))
    )
    (comp (ref "R78")
      (value "10K")
      (footprint "eagle-import:0603-RES")
      (libsource (lib "eagle-import") (part "RESISTOR0603"))
    )
    (comp (ref "R79")
      (value "10K")
      (footprint "eagle-import:0603-RES")
      (libsource (lib "eagle-import") (part "RESISTOR0603"))
    )
    (comp (ref "R80")
      (value "10K")
      (footprint "eagle-import:0603-RES")
      (libsource (lib "eagle-import") (part "RESISTOR0603"))
    )
    (comp (ref "R81")
      (value "10K")
      (footprint "eagle-import:0603-RES")
      (libsource (lib "eagle-import") (part "RESISTOR0603"))
    )
    (comp (ref "R93")
      (value "4.7K")
      (footprint "eagle-import:0603-RES")
      (libsource (lib "eagle-import") (part "RESISTOR0603"))
    )
    (comp (ref "R94")
      (value "4.7K")
      (footprint "eagle-import:0603-RES")
      (libsource (lib "eagle-import") (part "RESISTOR0603"))
    )
    (comp (ref "R98")
      (value "0")
      (footprint "eagle-import:0603-RES")
      (libsource (lib "eagle-import") (part "RESISTOR0603"))
    )
    (comp (ref "S1")
      (value "Power")
      (footprint "eagle-import:EVQ-PAC04M")
      (libsource (lib "eagle-import") (part "10-XXT"))
    )
    (comp (ref "S2")
      (value "Reset")
      (footprint "eagle-import:EVQ-PAC04M")
      (libsource (lib "eagle-import") (part "10-XXT"))
    )
    (comp (ref "S3")
      (value "Up")
      (footprint "eagle-import:EVQ-PAC04M")
      (libsource (lib "eagle-import") (part "10-XXT"))
    )
    (comp (ref "S4")
      (value "Down")
      (footprint "eagle-import:EVQ-PAC04M")
      (libsource (lib "eagle-import") (part "10-XXT"))
    )
    (comp (ref "S5")
      (value "Right")
      (footprint "eagle-import:EVQ-PAC04M")
      (libsource (lib "eagle-import") (part "10-XXT"))
    )
    (comp (ref "S6")
      (value "Left")
      (footprint "eagle-import:EVQ-PAC04M")
      (libsource (lib "eagle-import") (part "10-XXT"))
    )
    (comp (ref "S7")
      (value "Enter")
      (footprint "eagle-import:EVQ-PAC04M")
      (libsource (lib "eagle-import") (part "10-XXT"))
    )
    (comp (ref "U25")
      (value "SN74LVC2G126")
      (footprint "eagle-import:SM8-TI-A")
      (libsource (lib "eagle-import") (part "SN74LVC2G126-ALTA"))
    )
    (comp (ref "C36")
      (value "0.1uF")
      (footprint "eagle-import:0603-CAP")
      (libsource (lib "eagle-import") (part "CAP0603"))
    )
    (comp (ref "C45")
      (value "0.1uF")
      (footprint "eagle-import:0603-CAP")
      (libsource (lib "eagle-import") (part "CAP0603"))
    )
    (comp (ref "D12")
      (value "RX")
      (footprint "eagle-import:LED-1206")
      (libsource (lib "eagle-import") (part "LED1206"))
    )
    (comp (ref "D13")
      (value "TX")
      (footprint "eagle-import:LED-1206")
      (libsource (lib "eagle-import") (part "LED1206"))
    )
    (comp (ref "J10")
      (value "I2C/!SPI")
      (footprint "eagle-import:1X2")
      (libsource (lib "eagle-import") (part "M02ATH"))
    )
    (comp (ref "J35")
      (value "A0/A1")
      (footprint "eagle-import:2X3SM")
      (libsource (lib "eagle-import") (part "M03X2SM"))
    )
    (comp (ref "J36")
      (value "SDA")
      (footprint "eagle-import:1X03-SPECIAL")
      (libsource (lib "eagle-import") (part "M03SP"))
    )
    (comp (ref "J37")
      (value "I2C/SPI")
      (footprint "eagle-import:PHOENIX1725708-7")
      (libsource (lib "eagle-import") (part "M07PH"))
    )
    (comp (ref "J37A")
      (value "I2C/SPI DNP")
      (footprint "eagle-import:1X07-SPECIAL")
      (libsource (lib "eagle-import") (part "M07SP"))
    )
    (comp (ref "J38")
      (value "SCL/SCLK")
      (footprint "eagle-import:1X2")
      (libsource (lib "eagle-import") (part "M02ATH"))
    )
    (comp (ref "J41")
      (value "LpBk B")
      (footprint "eagle-import:2X2SM")
      (libsource (lib "eagle-import") (part "2X2SM"))
    )
    (comp (ref "R30")
      (value "20K")
      (footprint "eagle-import:0603-RES")
      (libsource (lib "eagle-import") (part "RESISTOR0603"))
    )
    (comp (ref "R36")
      (value "4.7K")
      (footprint "eagle-import:0603-RES")
      (libsource (lib "eagle-import") (part "RESISTOR0603"))
    )
    (comp (ref "R58")
      (value "1K")
      (footprint "eagle-import:0603-RES")
      (libsource (lib "eagle-import") (part "RESISTOR0603"))
    )
    (comp (ref "R63")
      (value "10K")
      (footprint "eagle-import:0603-RES")
      (libsource (lib "eagle-import") (part "RESISTOR0603"))
    )
    (comp (ref "R72")
      (value "10K")
      (footprint "eagle-import:0603-RES")
      (libsource (lib "eagle-import") (part "RESISTOR0603"))
    )
    (comp (ref "R73")
      (value "4.7K")
      (footprint "eagle-import:0603-RES")
      (libsource (lib "eagle-import") (part "RESISTOR0603"))
    )
    (comp (ref "R74")
      (value "4.7K")
      (footprint "eagle-import:0603-RES")
      (libsource (lib "eagle-import") (part "RESISTOR0603"))
    )
    (comp (ref "R82")
      (value "0 DNP")
      (footprint "eagle-import:0603-RES")
      (libsource (lib "eagle-import") (part "RESISTOR0603"))
    )
    (comp (ref "R89")
      (value "4.7K")
      (footprint "eagle-import:0603-RES")
      (libsource (lib "eagle-import") (part "RESISTOR0603"))
    )
    (comp (ref "R90")
      (value "470")
      (footprint "eagle-import:0603-RES")
      (libsource (lib "eagle-import") (part "RESISTOR0603"))
    )
    (comp (ref "U11")
      (value "SC16IS740IPW")
      (footprint "eagle-import:TSSOP16")
      (libsource (lib "eagle-import") (part "SC16IS740IPW"))
    )
    (comp (ref "U23")
      (value "SN74LVC2G126")
      (footprint "eagle-import:SM8-TI-A")
      (libsource (lib "eagle-import") (part "SN74LVC2G126-ALTA"))
    )
    (comp (ref "C5")
      (value "4.7uF 10V")
      (footprint "eagle-import:0603-CAP")
      (libsource (lib "eagle-import") (part "CAP0603"))
    )
    (comp (ref "C6")
      (value "1uF 35V")
      (footprint "eagle-import:0603-CAP")
      (libsource (lib "eagle-import") (part "CAP0603"))
    )
    (comp (ref "C13")
      (value "0.1uF")
      (footprint "eagle-import:0603-CAP")
      (libsource (lib "eagle-import") (part "CAP0603"))
    )
    (comp (ref "C14")
      (value "4.7nF")
      (footprint "eagle-import:0603-CAP")
      (libsource (lib "eagle-import") (part "CAP0603"))
    )
    (comp (ref "C20")
      (value "0.01uF")
      (footprint "eagle-import:0603-CAP")
      (libsource (lib "eagle-import") (part "CAP0603"))
    )
    (comp (ref "C33")
      (value "0.1uF")
      (footprint "eagle-import:0603-CAP")
      (libsource (lib "eagle-import") (part "CAP0603"))
    )
    (comp (ref "C34")
      (value "0.1uF")
      (footprint "eagle-import:0603-CAP")
      (libsource (lib "eagle-import") (part "CAP0603"))
    )
    (comp (ref "D5")
      (value "CMSH1-40")
      (footprint "eagle-import:SMB-DIODE")
      (libsource (lib "eagle-import") (part "DIODE-SCHOTTKY1"))
    )
    (comp (ref "FB2")
      (value "BLM18KG601SN1D")
      (footprint "eagle-import:0603")
      (libsource (lib "eagle-import") (part "FERRITEBEAD"))
    )
    (comp (ref "J25")
      (value "DSBL LCD")
      (footprint "eagle-import:1X2SM")
      (libsource (lib "eagle-import") (part "M02ASM"))
    )
    (comp (ref "J31")
      (value "LCD_Test")
      (footprint "eagle-import:1X03-SPECIAL")
      (libsource (lib "eagle-import") (part "M03SP"))
    )
    (comp (ref "J34")
      (value "CAN")
      (footprint "eagle-import:PHOENIX1725669-3")
      (libsource (lib "eagle-import") (part "M03PH"))
    )
    (comp (ref "J34A")
      (value "CAN DNP")
      (footprint "eagle-import:1X03-SPECIAL")
      (libsource (lib "eagle-import") (part "M03SP"))
    )
    (comp (ref "L1")
      (value "CLF6045T-220M-D")
      (footprint "eagle-import:TDK_CA")
      (libsource (lib "eagle-import") (part "TDK-CA_INDUCT"))
    )
    (comp (ref "MD2")
      (value "NHD-7.0-800480EF")
      (footprint "eagle-import:NEWHAVEN_LCD_NHD-7.0-800480EF")
      (libsource (lib "eagle-import") (part "NEWHAVEN_LCD_NHD-7.0-800480EF"))
    )
    (comp (ref "R26")
      (value "3.74")
      (footprint "eagle-import:0603-RES")
      (libsource (lib "eagle-import") (part "RESISTOR0603"))
    )
    (comp (ref "R27")
      (value "3.74")
      (footprint "eagle-import:0603-RES")
      (libsource (lib "eagle-import") (part "RESISTOR0603"))
    )
    (comp (ref "R28")
      (value "1K")
      (footprint "eagle-import:0603-RES")
      (libsource (lib "eagle-import") (part "RESISTOR0603"))
    )
    (comp (ref "R43")
      (value "4.7K DNP")
      (footprint "eagle-import:0603-RES")
      (libsource (lib "eagle-import") (part "RESISTOR0603"))
    )
    (comp (ref "R44")
      (value "4.7K DNP")
      (footprint "eagle-import:0603-RES")
      (libsource (lib "eagle-import") (part "RESISTOR0603"))
    )
    (comp (ref "R45")
      (value "4.7K")
      (footprint "eagle-import:0603-RES")
      (libsource (lib "eagle-import") (part "RESISTOR0603"))
    )
    (comp (ref "R46")
      (value "4.7K")
      (footprint "eagle-import:0603-RES")
      (libsource (lib "eagle-import") (part "RESISTOR0603"))
    )
    (comp (ref "R47")
      (value "60")
      (footprint "eagle-import:0603-RES")
      (libsource (lib "eagle-import") (part "RESISTOR0603"))
    )
    (comp (ref "R48")
      (value "60")
      (footprint "eagle-import:0603-RES")
      (libsource (lib "eagle-import") (part "RESISTOR0603"))
    )
    (comp (ref "R49")
      (value "0")
      (footprint "eagle-import:0603-RES")
      (libsource (lib "eagle-import") (part "RESISTOR0603"))
    )
    (comp (ref "R51")
      (value "0 DNP")
      (footprint "eagle-import:0603-RES")
      (libsource (lib "eagle-import") (part "RESISTOR0603"))
    )
    (comp (ref "R52")
      (value "0 DNP")
      (footprint "eagle-import:0603-RES")
      (libsource (lib "eagle-import") (part "RESISTOR0603"))
    )
    (comp (ref "R67")
      (value "0")
      (footprint "eagle-import:0603-RES")
      (libsource (lib "eagle-import") (part "RESISTOR0603"))
    )
    (comp (ref "R68")
      (value "10K")
      (footprint "eagle-import:0603-RES")
      (libsource (lib "eagle-import") (part "RESISTOR0603"))
    )
    (comp (ref "R69")
      (value "0 DNP")
      (footprint "eagle-import:0603-RES")
      (libsource (lib "eagle-import") (part "RESISTOR0603"))
    )
    (comp (ref "R84")
      (value "0")
      (footprint "eagle-import:0805-RES")
      (libsource (lib "eagle-import") (part "RESISTOR0805"))
    )
    (comp (ref "R95")
      (value "0")
      (footprint "eagle-import:0805-RES")
      (libsource (lib "eagle-import") (part "RESISTOR0805"))
    )
    (comp (ref "R96")
      (value "0")
      (footprint "eagle-import:0805-RES")
      (libsource (lib "eagle-import") (part "RESISTOR0805"))
    )
    (comp (ref "R97")
      (value "0")
      (footprint "eagle-import:0805-RES")
      (libsource (lib "eagle-import") (part "RESISTOR0805"))
    )
    (comp (ref "U2")
      (value "CAT4139T")
      (footprint "eagle-import:TSOT-23-5")
      (libsource (lib "eagle-import") (part "CAT4139T"))
    )
    (comp (ref "U3")
      (value "NCV7342")
      (footprint "eagle-import:SOIC08")
      (libsource (lib "eagle-import") (part "NCV7342"))
    )
    (comp (ref "U12")
      (value "CAT24C256WI-GT3")
      (footprint "eagle-import:SO08")
      (libsource (lib "eagle-import") (part "EEPROM-I2CSMD"))
    )
    (comp (ref "C12")
      (value "DNP")
      (footprint "eagle-import:0603-CAP")
      (libsource (lib "eagle-import") (part "CAP0603"))
    )
    (comp (ref "C24")
      (value "0.1uF")
      (footprint "eagle-import:0603-CAP")
      (libsource (lib "eagle-import") (part "CAP0603"))
    )
    (comp (ref "C26")
      (value "DNP")
      (footprint "eagle-import:0603-CAP")
      (libsource (lib "eagle-import") (part "CAP0603"))
    )
    (comp (ref "C32")
      (value "0.1uF")
      (footprint "eagle-import:0603-CAP")
      (libsource (lib "eagle-import") (part "CAP0603"))
    )
    (comp (ref "C35")
      (value "0.1uF")
      (footprint "eagle-import:0603-CAP")
      (libsource (lib "eagle-import") (part "CAP0603"))
    )
    (comp (ref "C39")
      (value "0.1uF")
      (footprint "eagle-import:0603-CAP")
      (libsource (lib "eagle-import") (part "CAP0603"))
    )
    (comp (ref "C40")
      (value "0.1uF")
      (footprint "eagle-import:0603-CAP")
      (libsource (lib "eagle-import") (part "CAP0603"))
    )
    (comp (ref "C48")
      (value "0.1uF")
      (footprint "eagle-import:0603-CAP")
      (libsource (lib "eagle-import") (part "CAP0603"))
    )
    (comp (ref "D6")
      (value "PWR")
      (footprint "eagle-import:LED-1206")
      (libsource (lib "eagle-import") (part "LED1206"))
    )
    (comp (ref "E1")
      (value "NAMECHANGE")
      (footprint "eagle-import:NAMECHANGE")
      (libsource (lib "eagle-import") (part "NAMECHANGE"))
    )
    (comp (ref "E8")
      (value "NAMECHANGE")
      (footprint "eagle-import:NAMECHANGE")
      (libsource (lib "eagle-import") (part "NAMECHANGE"))
    )
    (comp (ref "J29")
      (value "TP-J8 DNP")
      (footprint "eagle-import:1X07-SPECIAL")
      (libsource (lib "eagle-import") (part "M07SP"))
    )
    (comp (ref "J30")
      (value "TP-J9 DNP")
      (footprint "eagle-import:1X09-SPECIAL")
      (libsource (lib "eagle-import") (part "M09SPECIAL"))
    )
    (comp (ref "MD1")
      (value "BeagleBone Black")
      (footprint "eagle-import:BBONE_BK")
      (libsource (lib "eagle-import") (part "BBONE_BKBOT_UP"))
    )
    (comp (ref "R1")
      (value "33")
      (footprint "eagle-import:0603-RES")
      (libsource (lib "eagle-import") (part "RESISTOR0603"))
    )
    (comp (ref "R2")
      (value "33")
      (footprint "eagle-import:0603-RES")
      (libsource (lib "eagle-import") (part "RESISTOR0603"))
    )
    (comp (ref "R3")
      (value "33")
      (footprint "eagle-import:0603-RES")
      (libsource (lib "eagle-import") (part "RESISTOR0603"))
    )
    (comp (ref "R4")
      (value "33")
      (footprint "eagle-import:0603-RES")
      (libsource (lib "eagle-import") (part "RESISTOR0603"))
    )
    (comp (ref "R5")
      (value "33")
      (footprint "eagle-import:0603-RES")
      (libsource (lib "eagle-import") (part "RESISTOR0603"))
    )
    (comp (ref "R6")
      (value "33")
      (footprint "eagle-import:0603-RES")
      (libsource (lib "eagle-import") (part "RESISTOR0603"))
    )
    (comp (ref "R7")
      (value "33")
      (footprint "eagle-import:0603-RES")
      (libsource (lib "eagle-import") (part "RESISTOR0603"))
    )
    (comp (ref "R8")
      (value "33")
      (footprint "eagle-import:0603-RES")
      (libsource (lib "eagle-import") (part "RESISTOR0603"))
    )
    (comp (ref "R9")
      (value "33")
      (footprint "eagle-import:0603-RES")
      (libsource (lib "eagle-import") (part "RESISTOR0603"))
    )
    (comp (ref "R10")
      (value "33")
      (footprint "eagle-import:0603-RES")
      (libsource (lib "eagle-import") (part "RESISTOR0603"))
    )
    (comp (ref "R11")
      (value "33")
      (footprint "eagle-import:0603-RES")
      (libsource (lib "eagle-import") (part "RESISTOR0603"))
    )
    (comp (ref "R12")
      (value "33")
      (footprint "eagle-import:0603-RES")
      (libsource (lib "eagle-import") (part "RESISTOR0603"))
    )
    (comp (ref "R13")
      (value "33")
      (footprint "eagle-import:0603-RES")
      (libsource (lib "eagle-import") (part "RESISTOR0603"))
    )
    (comp (ref "R14")
      (value "33")
      (footprint "eagle-import:0603-RES")
      (libsource (lib "eagle-import") (part "RESISTOR0603"))
    )
    (comp (ref "R15")
      (value "33")
      (footprint "eagle-import:0603-RES")
      (libsource (lib "eagle-import") (part "RESISTOR0603"))
    )
    (comp (ref "R16")
      (value "33")
      (footprint "eagle-import:0603-RES")
      (libsource (lib "eagle-import") (part "RESISTOR0603"))
    )
    (comp (ref "R17")
      (value "33")
      (footprint "eagle-import:0603-RES")
      (libsource (lib "eagle-import") (part "RESISTOR0603"))
    )
    (comp (ref "R18")
      (value "33")
      (footprint "eagle-import:0603-RES")
      (libsource (lib "eagle-import") (part "RESISTOR0603"))
    )
    (comp (ref "R19")
      (value "33")
      (footprint "eagle-import:0603-RES")
      (libsource (lib "eagle-import") (part "RESISTOR0603"))
    )
    (comp (ref "R20")
      (value "33")
      (footprint "eagle-import:0603-RES")
      (libsource (lib "eagle-import") (part "RESISTOR0603"))
    )
    (comp (ref "R25")
      (value "4.7K")
      (footprint "eagle-import:0603-RES")
      (libsource (lib "eagle-import") (part "RESISTOR0603"))
    )
    (comp (ref "R32")
      (value "4.7K")
      (footprint "eagle-import:0603-RES")
      (libsource (lib "eagle-import") (part "RESISTOR0603"))
    )
    (comp (ref "R33")
      (value "4.7K")
      (footprint "eagle-import:0603-RES")
      (libsource (lib "eagle-import") (part "RESISTOR0603"))
    )
    (comp (ref "R34")
      (value "0")
      (footprint "eagle-import:0603-RES")
      (libsource (lib "eagle-import") (part "RESISTOR0603"))
    )
    (comp (ref "R35")
      (value "0 DNP")
      (footprint "eagle-import:0603-RES")
      (libsource (lib "eagle-import") (part "RESISTOR0603"))
    )
    (comp (ref "R59")
      (value "4.7K")
      (footprint "eagle-import:0603-RES")
      (libsource (lib "eagle-import") (part "RESISTOR0603"))
    )
    (comp (ref "R64")
      (value "0.010")
      (footprint "eagle-import:RESIST_4-TERM_VISHAY")
      (libsource (lib "eagle-import") (part "RESISTOR_4-TERM1"))
    )
    (comp (ref "R66")
      (value "33")
      (footprint "eagle-import:0603-RES")
      (libsource (lib "eagle-import") (part "RESISTOR0603"))
    )
    (comp (ref "R70")
      (value "0")
      (footprint "eagle-import:0603-RES")
      (libsource (lib "eagle-import") (part "RESISTOR0603"))
    )
    (comp (ref "R83")
      (value "470")
      (footprint "eagle-import:0603-RES")
      (libsource (lib "eagle-import") (part "RESISTOR0603"))
    )
    (comp (ref "U14")
      (value "ADG4612")
      (footprint "eagle-import:TSSOP16")
      (libsource (lib "eagle-import") (part "ADG4612"))
    )
    (comp (ref "U15")
      (value "ADG4612")
      (footprint "eagle-import:TSSOP16")
      (libsource (lib "eagle-import") (part "ADG4612"))
    )
    (comp (ref "U18")
      (value "INA225")
      (footprint "eagle-import:MSOP8")
      (libsource (lib "eagle-import") (part "INA225"))
    )
    (comp (ref "C1")
      (value "47pF")
      (footprint "eagle-import:0603-CAP")
      (libsource (lib "eagle-import") (part "CAP0603"))
    )
    (comp (ref "C2")
      (value "47pF")
      (footprint "eagle-import:0603-CAP")
      (libsource (lib "eagle-import") (part "CAP0603"))
    )
    (comp (ref "C3")
      (value "10nF")
      (footprint "eagle-import:0603-CAP")
      (libsource (lib "eagle-import") (part "CAP0603"))
    )
    (comp (ref "C15")
      (value "100nF")
      (footprint "eagle-import:0603-CAP")
      (libsource (lib "eagle-import") (part "CAP0603"))
    )
    (comp (ref "C16")
      (value "8.2pF")
      (footprint "eagle-import:0603-CAP")
      (libsource (lib "eagle-import") (part "CAP0603"))
    )
    (comp (ref "C17")
      (value "1uF")
      (footprint "eagle-import:0603-CAP")
      (libsource (lib "eagle-import") (part "CAP0603"))
    )
    (comp (ref "C21")
      (value "100nF DNP")
      (footprint "eagle-import:0603-CAP")
      (libsource (lib "eagle-import") (part "CAP0603"))
    )
    (comp (ref "C30")
      (value "4.7uF")
      (footprint "eagle-import:0603-CAP")
      (libsource (lib "eagle-import") (part "CAP0603"))
    )
    (comp (ref "C31")
      (value "0.1uF")
      (footprint "eagle-import:0603-CAP")
      (libsource (lib "eagle-import") (part "CAP0603"))
    )
    (comp (ref "C43")
      (value "0.1uF")
      (footprint "eagle-import:0603-CAP")
      (libsource (lib "eagle-import") (part "CAP0603"))
    )
    (comp (ref "D1")
      (value "TX")
      (footprint "eagle-import:LED-1206")
      (libsource (lib "eagle-import") (part "LED1206"))
    )
    (comp (ref "D2")
      (value "RX")
      (footprint "eagle-import:LED-1206")
      (libsource (lib "eagle-import") (part "LED1206"))
    )
    (comp (ref "D3")
      (value "GN")
      (footprint "eagle-import:LED-1206")
      (libsource (lib "eagle-import") (part "LED1206"))
    )
    (comp (ref "D8")
      (value "RX")
      (footprint "eagle-import:LED-1206")
      (libsource (lib "eagle-import") (part "LED1206"))
    )
    (comp (ref "D9")
      (value "TX")
      (footprint "eagle-import:LED-1206")
      (libsource (lib "eagle-import") (part "LED1206"))
    )
    (comp (ref "FB1")
      (value "BLM18KG601SN1D")
      (footprint "eagle-import:0603")
      (libsource (lib "eagle-import") (part "FERRITEBEAD"))
    )
    (comp (ref "J12")
      (value "USBMINI")
      (footprint "eagle-import:USBMINI-TH")
      (libsource (lib "eagle-import") (part "USBMINI-32007-400TH"))
    )
    (comp (ref "J15")
      (value "XBeeCtrl")
      (footprint "eagle-import:2X3")
      (libsource (lib "eagle-import") (part "M03X2NL"))
    )
    (comp (ref "J16")
      (value "M03X2SM")
      (footprint "eagle-import:2X3SM")
      (libsource (lib "eagle-import") (part "M03X2SM"))
    )
    (comp (ref "J19")
      (value "UART/XBee")
      (footprint "eagle-import:2X2SM")
      (libsource (lib "eagle-import") (part "2X2SM"))
    )
    (comp (ref "J27")
      (value "XBee DNP")
      (footprint "eagle-import:1X07-SPECIAL")
      (libsource (lib "eagle-import") (part "M07SP"))
    )
    (comp (ref "MD3")
      (value "XBEE-2A")
      (footprint "eagle-import:XBEE-2")
      (libsource (lib "eagle-import") (part "XBEE-2A"))
    )
    (comp (ref "R21")
      (value "27")
      (footprint "eagle-import:0603-RES")
      (libsource (lib "eagle-import") (part "RESISTOR0603"))
    )
    (comp (ref "R22")
      (value "27")
      (footprint "eagle-import:0603-RES")
      (libsource (lib "eagle-import") (part "RESISTOR0603"))
    )
    (comp (ref "R23")
      (value "4.7K")
      (footprint "eagle-import:0603-RES")
      (libsource (lib "eagle-import") (part "RESISTOR0603"))
    )
    (comp (ref "R24")
      (value "470")
      (footprint "eagle-import:0603-RES")
      (libsource (lib "eagle-import") (part "RESISTOR0603"))
    )
    (comp (ref "R50")
      (value "20K")
      (footprint "eagle-import:0603-RES")
      (libsource (lib "eagle-import") (part "RESISTOR0603"))
    )
    (comp (ref "R53")
      (value "0 DNP")
      (footprint "eagle-import:0603-RES")
      (libsource (lib "eagle-import") (part "RESISTOR0603"))
    )
    (comp (ref "R55")
      (value "470")
      (footprint "eagle-import:0603-RES")
      (libsource (lib "eagle-import") (part "RESISTOR0603"))
    )
    (comp (ref "R60")
      (value "0 DNP")
      (footprint "eagle-import:0603-RES")
      (libsource (lib "eagle-import") (part "RESISTOR0603"))
    )
    (comp (ref "R61")
      (value "0 DNP")
      (footprint "eagle-import:0603-RES")
      (libsource (lib "eagle-import") (part "RESISTOR0603"))
    )
    (comp (ref "R62")
      (value "10K DNP")
      (footprint "eagle-import:0603-RES")
      (libsource (lib "eagle-import") (part "RESISTOR0603"))
    )
    (comp (ref "R85")
      (value "4.7K")
      (footprint "eagle-import:0603-RES")
      (libsource (lib "eagle-import") (part "RESISTOR0603"))
    )
    (comp (ref "R86")
      (value "470")
      (footprint "eagle-import:0603-RES")
      (libsource (lib "eagle-import") (part "RESISTOR0603"))
    )
    (comp (ref "U5")
      (value "FT231XS")
      (footprint "eagle-import:SSOP20-.150")
      (libsource (lib "eagle-import") (part "FT231XX"))
    )
    (comp (ref "U16")
      (value "SN74LVC2G126A")
      (footprint "eagle-import:SM8-TI-A")
      (libsource (lib "eagle-import") (part "SN74LVC2G126A"))
    )
    (comp (ref "U21")
      (value "SN74LVC2G126")
      (footprint "eagle-import:SM8-TI-A")
      (libsource (lib "eagle-import") (part "SN74LVC2G126-ALTA"))
    )
    (comp (ref "C18")
      (value "4.7uF")
      (footprint "eagle-import:0603-CAP")
      (libsource (lib "eagle-import") (part "CAP0603"))
    )
    (comp (ref "C19")
      (value "0.1uF")
      (footprint "eagle-import:0603-CAP")
      (libsource (lib "eagle-import") (part "CAP0603"))
    )
    (comp (ref "C25")
      (value "0.1uF")
      (footprint "eagle-import:0603-CAP")
      (libsource (lib "eagle-import") (part "CAP0603"))
    )
    (comp (ref "C27")
      (value "DNP")
      (footprint "eagle-import:0603-CAP")
      (libsource (lib "eagle-import") (part "CAP0603"))
    )
    (comp (ref "C38")
      (value "47nF")
      (footprint "eagle-import:0603-CAP")
      (libsource (lib "eagle-import") (part "CAP0603"))
    )
    (comp (ref "C41")
      (value "47nF")
      (footprint "eagle-import:0603-CAP")
      (libsource (lib "eagle-import") (part "CAP0603"))
    )
    (comp (ref "C44")
      (value "0.1uF")
      (footprint "eagle-import:0603-CAP")
      (libsource (lib "eagle-import") (part "CAP0603"))
    )
    (comp (ref "C49")
      (value "4.7nF")
      (footprint "eagle-import:0603-CAP")
      (libsource (lib "eagle-import") (part "CAP0603"))
    )
    (comp (ref "D10")
      (value "RX")
      (footprint "eagle-import:LED-1206")
      (libsource (lib "eagle-import") (part "LED1206"))
    )
    (comp (ref "D11")
      (value "TX")
      (footprint "eagle-import:LED-1206")
      (libsource (lib "eagle-import") (part "LED1206"))
    )
    (comp (ref "J13")
      (value "SMB")
      (footprint "eagle-import:SMB-SMD")
      (libsource (lib "eagle-import") (part "SMB-SMDA"))
    )
    (comp (ref "J14")
      (value "SMB")
      (footprint "eagle-import:SMB-SMD")
      (libsource (lib "eagle-import") (part "SMB-SMDA"))
    )
    (comp (ref "J17")
      (value "SMA")
      (footprint "eagle-import:SMA-EDGE")
      (libsource (lib "eagle-import") (part "BNC-SMA-EDGESMA-ONLY"))
    )
    (comp (ref "J18")
      (value "SMA")
      (footprint "eagle-import:SMA-EDGE")
      (libsource (lib "eagle-import") (part "BNC-SMA-EDGESMA-ONLY"))
    )
    (comp (ref "J40")
      (value "READER")
      (footprint "eagle-import:1X06")
      (libsource (lib "eagle-import") (part "M06SIP"))
    )
    (comp (ref "MD5")
      (value "READER")
      (footprint "eagle-import:RADON_RFID_READ")
      (libsource (lib "eagle-import") (part "RADON_RFID_READ"))
    )
    (comp (ref "R56")
      (value "0 DNP")
      (footprint "eagle-import:0603-RES")
      (libsource (lib "eagle-import") (part "RESISTOR0603"))
    )
    (comp (ref "R57")
      (value "0")
      (footprint "eagle-import:0603-RES")
      (libsource (lib "eagle-import") (part "RESISTOR0603"))
    )
    (comp (ref "R65")
      (value "0.010")
      (footprint "eagle-import:RESIST_4-TERM_VISHAY")
      (libsource (lib "eagle-import") (part "RESISTOR_4-TERM1"))
    )
    (comp (ref "R71")
      (value "0")
      (footprint "eagle-import:0603-RES")
      (libsource (lib "eagle-import") (part "RESISTOR0603"))
    )
    (comp (ref "R87")
      (value "4.7K")
      (footprint "eagle-import:0603-RES")
      (libsource (lib "eagle-import") (part "RESISTOR0603"))
    )
    (comp (ref "R88")
      (value "470")
      (footprint "eagle-import:0603-RES")
      (libsource (lib "eagle-import") (part "RESISTOR0603"))
    )
    (comp (ref "R99")
      (value "20K DNP")
      (footprint "eagle-import:0603-RES")
      (libsource (lib "eagle-import") (part "RESISTOR0603"))
    )
    (comp (ref "U17")
      (value "IL712S")
      (footprint "eagle-import:SOIC08")
      (libsource (lib "eagle-import") (part "IL712S"))
    )
    (comp (ref "U19")
      (value "INA225")
      (footprint "eagle-import:MSOP8")
      (libsource (lib "eagle-import") (part "INA225"))
    )
    (comp (ref "U20")
      (value "TPS22958")
      (footprint "eagle-import:MSOP8-POWERPAD")
      (libsource (lib "eagle-import") (part "TPS22958POWERSWITCH"))
    )
    (comp (ref "U22")
      (value "SN74LVC2G126")
      (footprint "eagle-import:SM8-TI-A")
      (libsource (lib "eagle-import") (part "SN74LVC2G126-ALTA"))
    )
    (comp (ref "C4")
      (value "0.1uF")
      (footprint "eagle-import:0603-CAP")
      (libsource (lib "eagle-import") (part "CAP0603"))
    )
    (comp (ref "C7")
      (value "0.1uF")
      (footprint "eagle-import:0603-CAP")
      (libsource (lib "eagle-import") (part "CAP0603"))
    )
    (comp (ref "C8")
      (value "0.1uF")
      (footprint "eagle-import:0603-CAP")
      (libsource (lib "eagle-import") (part "CAP0603"))
    )
    (comp (ref "C9")
      (value "0.1uF")
      (footprint "eagle-import:0603-CAP")
      (libsource (lib "eagle-import") (part "CAP0603"))
    )
    (comp (ref "C10")
      (value "0.1uF")
      (footprint "eagle-import:0603-CAP")
      (libsource (lib "eagle-import") (part "CAP0603"))
    )
    (comp (ref "C11")
      (value "0.1uF")
      (footprint "eagle-import:0603-CAP")
      (libsource (lib "eagle-import") (part "CAP0603"))
    )
    (comp (ref "C37")
      (value "0.1uF")
      (footprint "eagle-import:0603-CAP")
      (libsource (lib "eagle-import") (part "CAP0603"))
    )
    (comp (ref "J20")
      (value "EXT_UART")
      (footprint "eagle-import:PHOENIX1725685-5")
      (libsource (lib "eagle-import") (part "M05PH"))
    )
    (comp (ref "J20A")
      (value "EXT_UART")
      (footprint "eagle-import:1X05")
      (libsource (lib "eagle-import") (part "M051X5"))
    )
    (comp (ref "R29")
      (value "20K")
      (footprint "eagle-import:0603-RES")
      (libsource (lib "eagle-import") (part "RESISTOR0603"))
    )
    (comp (ref "R75")
      (value "20K")
      (footprint "eagle-import:0603-RES")
      (libsource (lib "eagle-import") (part "RESISTOR0603"))
    )
    (comp (ref "U1")
      (value "74HC237")
      (footprint "eagle-import:TSSOP16")
      (libsource (lib "eagle-import") (part "74HC237"))
    )
    (comp (ref "U4")
      (value "SN74LVC2G126")
      (footprint "eagle-import:SM8-TI-A")
      (libsource (lib "eagle-import") (part "SN74LVC2G126A"))
    )
    (comp (ref "U6")
      (value "SN74LVC2G126A")
      (footprint "eagle-import:SM8-TI-A")
      (libsource (lib "eagle-import") (part "SN74LVC2G126A"))
    )
    (comp (ref "U7")
      (value "SN74LVC2G126A")
      (footprint "eagle-import:SM8-TI-A")
      (libsource (lib "eagle-import") (part "SN74LVC2G126A"))
    )
    (comp (ref "U8")
      (value "SN74LVC2G126A")
      (footprint "eagle-import:SM8-TI-A")
      (libsource (lib "eagle-import") (part "SN74LVC2G126A"))
    )
    (comp (ref "U9")
      (value "SN74LVC2G126A")
      (footprint "eagle-import:SM8-TI-A")
      (libsource (lib "eagle-import") (part "SN74LVC2G126A"))
    )
    (comp (ref "U10")
      (value "SN74LVC2G126A")
      (footprint "eagle-import:SM8-TI-A")
      (libsource (lib "eagle-import") (part "SN74LVC2G126A"))
    )
    (comp (ref "C22")
      (value "DNP")
      (footprint "eagle-import:0603-CAP")
      (libsource (lib "eagle-import") (part "CAP0603"))
    )
    (comp (ref "C23")
      (value "DNP")
      (footprint "eagle-import:0603-CAP")
      (libsource (lib "eagle-import") (part "CAP0603"))
    )
    (comp (ref "C42")
      (value "100nF")
      (footprint "eagle-import:0603-CAP")
      (libsource (lib "eagle-import") (part "CAP0603"))
    )
    (comp (ref "C46")
      (value "0.1uF")
      (footprint "eagle-import:0603-CAP")
      (libsource (lib "eagle-import") (part "CAP0603"))
    )
    (comp (ref "D14")
      (value "RX")
      (footprint "eagle-import:LED-1206")
      (libsource (lib "eagle-import") (part "LED1206"))
    )
    (comp (ref "D15")
      (value "TX")
      (footprint "eagle-import:LED-1206")
      (libsource (lib "eagle-import") (part "LED1206"))
    )
    (comp (ref "J21")
      (value "KNX DNP")
      (footprint "eagle-import:1X09-SPECIAL")
      (libsource (lib "eagle-import") (part "M09SPECIAL"))
    )
    (comp (ref "J22")
      (value "KNX3V3")
      (footprint "eagle-import:1X03-SPECIAL")
      (libsource (lib "eagle-import") (part "M03SP"))
    )
    (comp (ref "J23")
      (value "KNX")
      (footprint "eagle-import:1X03-SPECIAL")
      (libsource (lib "eagle-import") (part "M03SP"))
    )
    (comp (ref "J24")
      (value "KNXGND")
      (footprint "eagle-import:1X03-SPECIAL")
      (libsource (lib "eagle-import") (part "M03SP"))
    )
    (comp (ref "MD6")
      (value "KNX-2")
      (footprint "eagle-import:KNX-1")
      (libsource (lib "eagle-import") (part "KNX-2"))
    )
    (comp (ref "R31")
      (value "4.7K DNP")
      (footprint "eagle-import:0603-RES")
      (libsource (lib "eagle-import") (part "RESISTOR0603"))
    )
    (comp (ref "R37")
      (value "0 DNP")
      (footprint "eagle-import:0603-RES")
      (libsource (lib "eagle-import") (part "RESISTOR0603"))
    )
    (comp (ref "R38")
      (value "6.04K 1%")
      (footprint "eagle-import:0603-RES")
      (libsource (lib "eagle-import") (part "RESISTOR0603"))
    )
    (comp (ref "R39")
      (value "3.01K 1%")
      (footprint "eagle-import:0603-RES")
      (libsource (lib "eagle-import") (part "RESISTOR0603"))
    )
    (comp (ref "R40")
      (value "0")
      (footprint "eagle-import:0603-RES")
      (libsource (lib "eagle-import") (part "RESISTOR0603"))
    )
    (comp (ref "R41")
      (value "6.04K 1%")
      (footprint "eagle-import:0603-RES")
      (libsource (lib "eagle-import") (part "RESISTOR0603"))
    )
    (comp (ref "R42")
      (value "3.01K 1%")
      (footprint "eagle-import:0603-RES")
      (libsource (lib "eagle-import") (part "RESISTOR0603"))
    )
    (comp (ref "R91")
      (value "4.7K")
      (footprint "eagle-import:0603-RES")
      (libsource (lib "eagle-import") (part "RESISTOR0603"))
    )
    (comp (ref "R92")
      (value "470")
      (footprint "eagle-import:0603-RES")
      (libsource (lib "eagle-import") (part "RESISTOR0603"))
    )
    (comp (ref "U13")
      (value "SN74LVC2G126")
      (footprint "eagle-import:SM8-TI-A")
      (libsource (lib "eagle-import") (part "SN74LVC2G126-ALTA"))
    )
    (comp (ref "U24")
      (value "SN74LVC2G126")
      (footprint "eagle-import:SM8-TI-A")
      (libsource (lib "eagle-import") (part "SN74LVC2G126-ALTA"))
    )
  )
  (nets
    (net (code "1") (name "+5V") (class "Default")
      (node (ref "F2") (pin "1") (pinfunction "1_1") (pintype "bidirectional"))
      (node (ref "J11") (pin "1") (pinfunction "PWR_1") (pintype "bidirectional"))
      (node (ref "R54") (pin "1") (pinfunction "1_1") (pintype "passive"))
    )
    (net (code "2") (name "A0{slash}CS") (class "Default")
      (node (ref "J28") (pin "1") (pinfunction "1_1") (pintype "passive"))
      (node (ref "J35") (pin "3") (pinfunction "3_3") (pintype "passive"))
      (node (ref "J37") (pin "5") (pinfunction "5_5") (pintype "passive"))
      (node (ref "J37A") (pin "5") (pinfunction "5_5") (pintype "passive"))
      (node (ref "U11") (pin "2") (pinfunction "A0/CS_2") (pintype "bidirectional"))
    )
    (net (code "3") (name "A1{slash}SI") (class "Default")
      (node (ref "J28") (pin "3") (pinfunction "3_3") (pintype "passive"))
      (node (ref "J35") (pin "4") (pinfunction "4_4") (pintype "passive"))
      (node (ref "J37") (pin "6") (pinfunction "6_6") (pintype "passive"))
      (node (ref "J37A") (pin "6") (pinfunction "6_6") (pintype "passive"))
      (node (ref "U11") (pin "3") (pinfunction "A1/SI_3") (pintype "bidirectional"))
    )
    (net (code "4") (name "AGND") (class "Default")
      (node (ref "E1") (pin "2") (pinfunction "2_2") (pintype "bidirectional"))
      (node (ref "J32") (pin "15") (pinfunction "15_15") (pintype "passive"))
      (node (ref "J33") (pin "8") (pinfunction "8_8") (pintype "passive"))
    )
    (net (code "5") (name "AIN0") (class "Default")
      (node (ref "MD1") (pin "~39") (pinfunction "39_~39") (pintype "bidirectional"))
      (node (ref "U14") (pin "7") (pinfunction "D4_7") (pintype "bidirectional"))
    )
    (net (code "6") (name "AIN1") (class "Default")
      (node (ref "MD1") (pin "~40") (pinfunction "40_~40") (pintype "bidirectional"))
      (node (ref "U15") (pin "10") (pinfunction "D3_10") (pintype "bidirectional"))
    )
    (net (code "7") (name "AIN2") (class "Default")
      (node (ref "MD1") (pin "~37") (pinfunction "37_~37") (pintype "bidirectional"))
      (node (ref "U14") (pin "10") (pinfunction "D3_10") (pintype "bidirectional"))
    )
    (net (code "8") (name "AIN3") (class "Default")
      (node (ref "MD1") (pin "~38") (pinfunction "38_~38") (pintype "bidirectional"))
      (node (ref "U15") (pin "15") (pinfunction "D2_15") (pintype "bidirectional"))
    )
    (net (code "9") (name "AIN4") (class "Default")
      (node (ref "MD1") (pin "~33") (pinfunction "33_~33") (pintype "bidirectional"))
      (node (ref "U14") (pin "2") (pinfunction "D1_2") (pintype "bidirectional"))
    )
    (net (code "10") (name "AIN4_SW") (class "Default")
      (node (ref "J32") (pin "7") (pinfunction "7_7") (pintype "passive"))
      (node (ref "U14") (pin "3") (pinfunction "S1_3") (pintype "bidirectional"))
    )
    (net (code "11") (name "AIN5") (class "Default")
      (node (ref "MD1") (pin "~36") (pinfunction "36_~36") (pintype "bidirectional"))
      (node (ref "U15") (pin "2") (pinfunction "D1_2") (pintype "bidirectional"))
    )
    (net (code "12") (name "AIN5_SW") (class "Default")
      (node (ref "J32") (pin "9") (pinfunction "9_9") (pintype "passive"))
      (node (ref "U15") (pin "3") (pinfunction "S1_3") (pintype "bidirectional"))
    )
    (net (code "13") (name "AIN6") (class "Default")
      (node (ref "MD1") (pin "~35") (pinfunction "35_~35") (pintype "bidirectional"))
      (node (ref "U14") (pin "15") (pinfunction "D2_15") (pintype "bidirectional"))
    )
    (net (code "14") (name "BBB_I-SENSE") (class "Default")
      (node (ref "C26") (pin "1") (pinfunction "+_1") (pintype "passive"))
      (node (ref "R70") (pin "2") (pinfunction "2_2") (pintype "passive"))
      (node (ref "U15") (pin "14") (pinfunction "S2_14") (pintype "bidirectional"))
    )
    (net (code "15") (name "BRIDGE_CLK") (class "Default")
      (node (ref "C12") (pin "1") (pinfunction "+_1") (pintype "passive"))
      (node (ref "R34") (pin "2") (pinfunction "2_2") (pintype "passive"))
      (node (ref "R35") (pin "2") (pinfunction "2_2") (pintype "passive"))
      (node (ref "U11") (pin "15") (pinfunction "XTAL1_15") (pintype "bidirectional"))
    )
    (net (code "16") (name "BRIDGE_RX") (class "Default")
      (node (ref "R30") (pin "2") (pinfunction "2_2") (pintype "passive"))
      (node (ref "U11") (pin "13") (pinfunction "RX_13") (pintype "bidirectional"))
      (node (ref "U23") (pin "2") (pinfunction "1A_2") (pintype "input"))
      (node (ref "U7") (pin "3") (pinfunction "2Y_3") (pintype "output"))
    )
    (net (code "17") (name "BRIDGE_TX") (class "Default")
      (node (ref "U11") (pin "12") (pinfunction "TX_12") (pintype "bidirectional"))
      (node (ref "U23") (pin "5") (pinfunction "2A_5") (pintype "input"))
      (node (ref "U7") (pin "2") (pinfunction "1A_2") (pintype "input"))
    )
    (net (code "18") (name "CANH") (class "Default")
      (node (ref "J34") (pin "1") (pinfunction "1_1") (pintype "passive"))
      (node (ref "J34A") (pin "1") (pinfunction "1_1") (pintype "passive"))
      (node (ref "R47") (pin "2") (pinfunction "2_2") (pintype "passive"))
      (node (ref "U3") (pin "7") (pinfunction "CANH_7") (pintype "bidirectional"))
    )
    (net (code "19") (name "CANL") (class "Default")
      (node (ref "J34") (pin "2") (pinfunction "2_2") (pintype "passive"))
      (node (ref "J34A") (pin "2") (pinfunction "2_2") (pintype "passive"))
      (node (ref "R48") (pin "2") (pinfunction "2_2") (pintype "passive"))
      (node (ref "U3") (pin "6") (pinfunction "CANL_6") (pintype "bidirectional"))
    )
    (net (code "20") (name "CBUS3_SW") (class "Default")
      (node (ref "E8") (pin "1") (pinfunction "1_1") (pintype "bidirectional"))
      (node (ref "R61") (pin "2") (pinfunction "2_2") (pintype "passive"))
    )
    (net (code "21") (name "DCAN1_RX") (class "Default")
      (node (ref "J33") (pin "12") (pinfunction "12_12") (pintype "passive"))
      (node (ref "MD1") (pin "~24") (pinfunction "24_~24") (pintype "bidirectional"))
      (node (ref "R52") (pin "2") (pinfunction "2_2") (pintype "passive"))
      (node (ref "U3") (pin "4") (pinfunction "RXD_4") (pintype "bidirectional"))
    )
    (net (code "22") (name "DCAN1_TX") (class "Default")
      (node (ref "J33") (pin "10") (pinfunction "10_10") (pintype "passive"))
      (node (ref "MD1") (pin "~26") (pinfunction "26_~26") (pintype "bidirectional"))
      (node (ref "U3") (pin "1") (pinfunction "TXD_1") (pintype "bidirectional"))
    )
    (net (code "23") (name "DOWN_BUT") (class "Default")
      (node (ref "MD1") (pin "~27") (pinfunction "27_~27") (pintype "bidirectional"))
      (node (ref "R78") (pin "1") (pinfunction "1_1") (pintype "passive"))
      (node (ref "S4") (pin "1") (pinfunction "S_1") (pintype "passive"))
      (node (ref "S4") (pin "2") (pinfunction "S1_2") (pintype "passive"))
    )
    (net (code "24") (name "EEPROM-WP") (class "Default")
      (node (ref "J28") (pin "13") (pinfunction "13_13") (pintype "passive"))
      (node (ref "R46") (pin "2") (pinfunction "2_2") (pintype "passive"))
      (node (ref "U12") (pin "7") (pinfunction "WP_7") (pintype "bidirectional"))
    )
    (net (code "25") (name "ENTER_BUT") (class "Default")
      (node (ref "MD1") (pin "18") (pinfunction "18_18") (pintype "bidirectional"))
      (node (ref "R81") (pin "1") (pinfunction "1_1") (pintype "passive"))
      (node (ref "S7") (pin "1") (pinfunction "S_1") (pintype "passive"))
      (node (ref "S7") (pin "2") (pinfunction "S1_2") (pintype "passive"))
    )
    (net (code "26") (name "EXT_UART_RX") (class "Default")
      (node (ref "J20") (pin "4") (pinfunction "4_4") (pintype "passive"))
      (node (ref "J20A") (pin "4") (pinfunction "4_4") (pintype "passive"))
      (node (ref "J28") (pin "11") (pinfunction "11_11") (pintype "passive"))
      (node (ref "R29") (pin "2") (pinfunction "2_2") (pintype "passive"))
      (node (ref "U6") (pin "2") (pinfunction "1A_2") (pintype "input"))
    )
    (net (code "27") (name "EXT_UART_TX") (class "Default")
      (node (ref "J20") (pin "5") (pinfunction "5_5") (pintype "passive"))
      (node (ref "J20A") (pin "5") (pinfunction "5_5") (pintype "passive"))
      (node (ref "J28") (pin "9") (pinfunction "9_9") (pintype "passive"))
      (node (ref "U6") (pin "3") (pinfunction "2Y_3") (pintype "output"))
    )
    (net (code "28") (name "GND") (class "Default")
      (node (ref "C1") (pin "2") (pinfunction "-_2") (pintype "passive"))
      (node (ref "C10") (pin "1") (pinfunction "+_1") (pintype "passive"))
      (node (ref "C11") (pin "1") (pinfunction "+_1") (pintype "passive"))
      (node (ref "C12") (pin "2") (pinfunction "-_2") (pintype "passive"))
      (node (ref "C13") (pin "2") (pinfunction "-_2") (pintype "passive"))
      (node (ref "C14") (pin "2") (pinfunction "-_2") (pintype "passive"))
      (node (ref "C15") (pin "2") (pinfunction "-_2") (pintype "passive"))
      (node (ref "C16") (pin "2") (pinfunction "-_2") (pintype "passive"))
      (node (ref "C17") (pin "2") (pinfunction "-_2") (pintype "passive"))
      (node (ref "C18") (pin "2") (pinfunction "-_2") (pintype "passive"))
      (node (ref "C19") (pin "2") (pinfunction "-_2") (pintype "passive"))
      (node (ref "C2") (pin "2") (pinfunction "-_2") (pintype "passive"))
      (node (ref "C20") (pin "2") (pinfunction "-_2") (pintype "passive"))
      (node (ref "C21") (pin "1") (pinfunction "+_1") (pintype "passive"))
      (node (ref "C22") (pin "2") (pinfunction "-_2") (pintype "passive"))
      (node (ref "C23") (pin "2") (pinfunction "-_2") (pintype "passive"))
      (node (ref "C24") (pin "1") (pinfunction "+_1") (pintype "passive"))
      (node (ref "C25") (pin "1") (pinfunction "+_1") (pintype "passive"))
      (node (ref "C26") (pin "2") (pinfunction "-_2") (pintype "passive"))
      (node (ref "C27") (pin "2") (pinfunction "-_2") (pintype "passive"))
      (node (ref "C28") (pin "C") (pinfunction "-_C") (pintype "passive"))
      (node (ref "C29") (pin "2") (pinfunction "-_2") (pintype "passive"))
      (node (ref "C3") (pin "2") (pinfunction "-_2") (pintype "passive"))
      (node (ref "C30") (pin "2") (pinfunction "-_2") (pintype "passive"))
      (node (ref "C31") (pin "2") (pinfunction "-_2") (pintype "passive"))
      (node (ref "C32") (pin "2") (pinfunction "-_2") (pintype "passive"))
      (node (ref "C33") (pin "2") (pinfunction "-_2") (pintype "passive"))
      (node (ref "C34") (pin "2") (pinfunction "-_2") (pintype "passive"))
      (node (ref "C35") (pin "2") (pinfunction "-_2") (pintype "passive"))
      (node (ref "C36") (pin "2") (pinfunction "-_2") (pintype "passive"))
      (node (ref "C37") (pin "2") (pinfunction "-_2") (pintype "passive"))
      (node (ref "C39") (pin "2") (pinfunction "-_2") (pintype "passive"))
      (node (ref "C4") (pin "1") (pinfunction "+_1") (pintype "passive"))
      (node (ref "C40") (pin "2") (pinfunction "-_2") (pintype "passive"))
      (node (ref "C41") (pin "2") (pinfunction "-_2") (pintype "passive"))
      (node (ref "C42") (pin "2") (pinfunction "-_2") (pintype "passive"))
      (node (ref "C43") (pin "1") (pinfunction "+_1") (pintype "passive"))
      (node (ref "C44") (pin "1") (pinfunction "+_1") (pintype "passive"))
      (node (ref "C45") (pin "1") (pinfunction "+_1") (pintype "passive"))
      (node (ref "C46") (pin "1") (pinfunction "+_1") (pintype "passive"))
      (node (ref "C47") (pin "1") (pinfunction "+_1") (pintype "passive"))
      (node (ref "C48") (pin "2") (pinfunction "-_2") (pintype "passive"))
      (node (ref "C49") (pin "2") (pinfunction "-_2") (pintype "passive"))
      (node (ref "C5") (pin "2") (pinfunction "-_2") (pintype "passive"))
      (node (ref "C6") (pin "2") (pinfunction "-_2") (pintype "passive"))
      (node (ref "C7") (pin "1") (pinfunction "+_1") (pintype "passive"))
      (node (ref "C8") (pin "1") (pinfunction "+_1") (pintype "passive"))
      (node (ref "C9") (pin "1") (pinfunction "+_1") (pintype "passive"))
      (node (ref "D4") (pin "A") (pinfunction "A_A") (pintype "passive"))
      (node (ref "D6") (pin "C") (pinfunction "C_C") (pintype "passive"))
      (node (ref "E1") (pin "1") (pinfunction "1_1") (pintype "bidirectional"))
      (node (ref "E2") (pin "1") (pinfunction "1_1") (pintype "bidirectional"))
      (node (ref "E3") (pin "1") (pinfunction "1_1") (pintype "bidirectional"))
      (node (ref "E4") (pin "1") (pinfunction "1_1") (pintype "bidirectional"))
      (node (ref "E5") (pin "1") (pinfunction "1_1") (pintype "bidirectional"))
      (node (ref "E6") (pin "1") (pinfunction "1_1") (pintype "bidirectional"))
      (node (ref "E7") (pin "1") (pinfunction "1_1") (pintype "bidirectional"))
      (node (ref "J11") (pin "2") (pinfunction "GND_2") (pintype "bidirectional"))
      (node (ref "J11") (pin "3") (pinfunction "GNDBREAK_3") (pintype "bidirectional"))
      (node (ref "J12") (pin "5") (pinfunction "5_5") (pintype "passive"))
      (node (ref "J12") (pin "6") (pinfunction "S1_6") (pintype "passive"))
      (node (ref "J12") (pin "7") (pinfunction "S2_7") (pintype "passive"))
      (node (ref "J12") (pin "8") (pinfunction "S3_8") (pintype "passive"))
      (node (ref "J12") (pin "9") (pinfunction "S4_9") (pintype "passive"))
      (node (ref "J20") (pin "1") (pinfunction "1_1") (pintype "passive"))
      (node (ref "J20A") (pin "1") (pinfunction "1_1") (pintype "passive"))
      (node (ref "J21") (pin "9") (pinfunction "9_9") (pintype "passive"))
      (node (ref "J24") (pin "1") (pinfunction "1_1") (pintype "passive"))
      (node (ref "J24") (pin "2") (pinfunction "2_2") (pintype "passive"))
      (node (ref "J24") (pin "3") (pinfunction "3_3") (pintype "passive"))
      (node (ref "J25") (pin "1") (pinfunction "1_1") (pintype "passive"))
      (node (ref "J27") (pin "7") (pinfunction "7_7") (pintype "passive"))
      (node (ref "J28") (pin "14") (pinfunction "14_14") (pintype "passive"))
      (node (ref "J29") (pin "7") (pinfunction "7_7") (pintype "passive"))
      (node (ref "J30") (pin "9") (pinfunction "9_9") (pintype "passive"))
      (node (ref "J32") (pin "1") (pinfunction "1_1") (pintype "passive"))
      (node (ref "J32") (pin "13") (pinfunction "13_13") (pintype "passive"))
      (node (ref "J32") (pin "25") (pinfunction "25_25") (pintype "passive"))
      (node (ref "J33") (pin "1") (pinfunction "1_1") (pintype "passive"))
      (node (ref "J33") (pin "14") (pinfunction "14_14") (pintype "passive"))
      (node (ref "J33") (pin "19") (pinfunction "19_19") (pintype "passive"))
      (node (ref "J33") (pin "9") (pinfunction "9_9") (pintype "passive"))
      (node (ref "J34") (pin "3") (pinfunction "3_3") (pintype "passive"))
      (node (ref "J34A") (pin "3") (pinfunction "3_3") (pintype "passive"))
      (node (ref "J35") (pin "5") (pinfunction "5_5") (pintype "passive"))
      (node (ref "J35") (pin "6") (pinfunction "6_6") (pintype "passive"))
      (node (ref "J36") (pin "3") (pinfunction "3_3") (pintype "passive"))
      (node (ref "J37") (pin "7") (pinfunction "7_7") (pintype "passive"))
      (node (ref "J37A") (pin "7") (pinfunction "7_7") (pintype "passive"))
      (node (ref "MD1") (pin "1") (pinfunction "1_1") (pintype "bidirectional"))
      (node (ref "MD1") (pin "2") (pinfunction "2_2") (pintype "bidirectional"))
      (node (ref "MD1") (pin "`1") (pinfunction "1_`1") (pintype "bidirectional"))
      (node (ref "MD1") (pin "~1") (pinfunction "1_~1") (pintype "bidirectional"))
      (node (ref "MD1") (pin "~2") (pinfunction "2_~2") (pintype "bidirectional"))
      (node (ref "MD1") (pin "~34") (pinfunction "34_~34") (pintype "bidirectional"))
      (node (ref "MD1") (pin "~43") (pinfunction "43_~43") (pintype "bidirectional"))
      (node (ref "MD1") (pin "~44") (pinfunction "44_~44") (pintype "bidirectional"))
      (node (ref "MD1") (pin "~45") (pinfunction "45_~45") (pintype "bidirectional"))
      (node (ref "MD1") (pin "~46") (pinfunction "46_~46") (pintype "bidirectional"))
      (node (ref "MD2") (pin "13") (pinfunction "13_13") (pintype "passive"))
      (node (ref "MD2") (pin "14") (pinfunction "14_14") (pintype "passive"))
      (node (ref "MD2") (pin "21") (pinfunction "21_21") (pintype "passive"))
      (node (ref "MD2") (pin "22") (pinfunction "22_22") (pintype "passive"))
      (node (ref "MD2") (pin "23") (pinfunction "23_23") (pintype "passive"))
      (node (ref "MD2") (pin "29") (pinfunction "29_29") (pintype "passive"))
      (node (ref "MD2") (pin "3") (pinfunction "3_3") (pintype "passive"))
      (node (ref "MD2") (pin "36") (pinfunction "36_36") (pintype "passive"))
      (node (ref "MD2") (pin "41") (pinfunction "41_41") (pintype "passive"))
      (node (ref "MD2") (pin "42") (pinfunction "42_42") (pintype "passive"))
      (node (ref "MD2") (pin "5") (pinfunction "5_5") (pintype "passive"))
      (node (ref "MD2") (pin "6") (pinfunction "6_6") (pintype "passive"))
      (node (ref "MD2") (pin "7") (pinfunction "7_7") (pintype "passive"))
      (node (ref "MD2") (pin "~2") (pinfunction "2_~2") (pintype "passive"))
      (node (ref "MD2") (pin "~7") (pinfunction "7_~7") (pintype "passive"))
      (node (ref "MD2") (pin "~8") (pinfunction "8_~8") (pintype "passive"))
      (node (ref "MD3") (pin "10") (pinfunction "GND_10") (pintype "power_in"))
      (node (ref "MD5") (pin "~2") (pinfunction "2_~2") (pintype "bidirectional"))
      (node (ref "MD5") (pin "~4") (pinfunction "2_~4") (pintype "bidirectional"))
      (node (ref "MD6") (pin "10") (pinfunction "GND4_10") (pintype "bidirectional"))
      (node (ref "MD6") (pin "12") (pinfunction "GND5_12") (pintype "bidirectional"))
      (node (ref "MD6") (pin "13") (pinfunction "GND6_13") (pintype "bidirectional"))
      (node (ref "MD6") (pin "17") (pinfunction "TREQ_17") (pintype "bidirectional"))
      (node (ref "MD6") (pin "19") (pinfunction "MODE1_19") (pintype "bidirectional"))
      (node (ref "MD6") (pin "2") (pinfunction "GND0_2") (pintype "bidirectional"))
      (node (ref "MD6") (pin "20") (pinfunction "MODE2_20") (pintype "bidirectional"))
      (node (ref "MD6") (pin "24") (pinfunction "GND7_24") (pintype "bidirectional"))
      (node (ref "MD6") (pin "4") (pinfunction "GND1_4") (pintype "bidirectional"))
      (node (ref "MD6") (pin "6") (pinfunction "GND2_6") (pintype "bidirectional"))
      (node (ref "MD6") (pin "9") (pinfunction "GND3_9") (pintype "bidirectional"))
      (node (ref "R26") (pin "1") (pinfunction "1_1") (pintype "passive"))
      (node (ref "R27") (pin "1") (pinfunction "1_1") (pintype "passive"))
      (node (ref "R36") (pin "2") (pinfunction "2_2") (pintype "passive"))
      (node (ref "R39") (pin "1") (pinfunction "1_1") (pintype "passive"))
      (node (ref "R42") (pin "1") (pinfunction "1_1") (pintype "passive"))
      (node (ref "R49") (pin "1") (pinfunction "1_1") (pintype "passive"))
      (node (ref "R55") (pin "2") (pinfunction "2_2") (pintype "passive"))
      (node (ref "R93") (pin "2") (pinfunction "2_2") (pintype "passive"))
      (node (ref "R94") (pin "2") (pinfunction "2_2") (pintype "passive"))
      (node (ref "R99") (pin "1") (pinfunction "1_1") (pintype "passive"))
      (node (ref "S1") (pin "3") (pinfunction "P_3") (pintype "passive"))
      (node (ref "S1") (pin "4") (pinfunction "P1_4") (pintype "passive"))
      (node (ref "S2") (pin "3") (pinfunction "P_3") (pintype "passive"))
      (node (ref "S2") (pin "4") (pinfunction "P1_4") (pintype "passive"))
      (node (ref "S3") (pin "3") (pinfunction "P_3") (pintype "passive"))
      (node (ref "S3") (pin "4") (pinfunction "P1_4") (pintype "passive"))
      (node (ref "S4") (pin "3") (pinfunction "P_3") (pintype "passive"))
      (node (ref "S4") (pin "4") (pinfunction "P1_4") (pintype "passive"))
      (node (ref "S5") (pin "3") (pinfunction "P_3") (pintype "passive"))
      (node (ref "S5") (pin "4") (pinfunction "P1_4") (pintype "passive"))
      (node (ref "S6") (pin "3") (pinfunction "P_3") (pintype "passive"))
      (node (ref "S6") (pin "4") (pinfunction "P1_4") (pintype "passive"))
      (node (ref "S7") (pin "3") (pinfunction "P_3") (pintype "passive"))
      (node (ref "S7") (pin "4") (pinfunction "P1_4") (pintype "passive"))
      (node (ref "U1") (pin "4") (pinfunction "LE_4") (pintype "bidirectional"))
      (node (ref "U1") (pin "5") (pinfunction "~{OE1}_5") (pintype "bidirectional"))
      (node (ref "U1") (pin "8") (pinfunction "GND_8") (pintype "bidirectional"))
      (node (ref "U10") (pin "4") (pinfunction "GND_4") (pintype "passive"))
      (node (ref "U11") (pin "9") (pinfunction "GND_9") (pintype "bidirectional"))
      (node (ref "U12") (pin "4") (pinfunction "VSS_4") (pintype "power_in"))
      (node (ref "U13") (pin "4") (pinfunction "GND_4") (pintype "passive"))
      (node (ref "U14") (pin "4") (pinfunction "VSS_4") (pintype "bidirectional"))
      (node (ref "U14") (pin "5") (pinfunction "GND_5") (pintype "bidirectional"))
      (node (ref "U15") (pin "4") (pinfunction "VSS_4") (pintype "bidirectional"))
      (node (ref "U15") (pin "5") (pinfunction "GND_5") (pintype "bidirectional"))
      (node (ref "U16") (pin "4") (pinfunction "GND_4") (pintype "passive"))
      (node (ref "U17") (pin "5") (pinfunction "GND2_5") (pintype "bidirectional"))
      (node (ref "U18") (pin "2") (pinfunction "GND_2") (pintype "bidirectional"))
      (node (ref "U18") (pin "5") (pinfunction "GS0_5") (pintype "bidirectional"))
      (node (ref "U18") (pin "6") (pinfunction "GS1_6") (pintype "bidirectional"))
      (node (ref "U18") (pin "7") (pinfunction "REF_7") (pintype "bidirectional"))
      (node (ref "U19") (pin "2") (pinfunction "GND_2") (pintype "bidirectional"))
      (node (ref "U19") (pin "5") (pinfunction "GS0_5") (pintype "bidirectional"))
      (node (ref "U19") (pin "6") (pinfunction "GS1_6") (pintype "bidirectional"))
      (node (ref "U19") (pin "7") (pinfunction "REF_7") (pintype "bidirectional"))
      (node (ref "U2") (pin "2") (pinfunction "GND_2") (pintype "bidirectional"))
      (node (ref "U20") (pin "10") (pinfunction "PP2_10") (pintype "bidirectional"))
      (node (ref "U20") (pin "6") (pinfunction "GND_6") (pintype "bidirectional"))
      (node (ref "U20") (pin "9") (pinfunction "PP1_9") (pintype "bidirectional"))
      (node (ref "U21") (pin "4") (pinfunction "GND_4") (pintype "passive"))
      (node (ref "U22") (pin "4") (pinfunction "GND_4") (pintype "passive"))
      (node (ref "U23") (pin "4") (pinfunction "GND_4") (pintype "passive"))
      (node (ref "U24") (pin "4") (pinfunction "GND_4") (pintype "passive"))
      (node (ref "U25") (pin "4") (pinfunction "GND_4") (pintype "passive"))
      (node (ref "U3") (pin "2") (pinfunction "GND_2") (pintype "bidirectional"))
      (node (ref "U4") (pin "4") (pinfunction "GND_4") (pintype "passive"))
      (node (ref "U5") (pin "16") (pinfunction "GND1_16") (pintype "power_in"))
      (node (ref "U5") (pin "6") (pinfunction "GND_6") (pintype "power_in"))
      (node (ref "U6") (pin "4") (pinfunction "GND_4") (pintype "passive"))
      (node (ref "U7") (pin "4") (pinfunction "GND_4") (pintype "passive"))
      (node (ref "U8") (pin "4") (pinfunction "GND_4") (pintype "passive"))
      (node (ref "U9") (pin "4") (pinfunction "GND_4") (pintype "passive"))
    )
    (net (code "29") (name "GPIO0_7") (class "Default")
      (node (ref "E8") (pin "2") (pinfunction "2_2") (pintype "bidirectional"))
      (node (ref "J32") (pin "21") (pinfunction "21_21") (pintype "passive"))
      (node (ref "MD1") (pin "~42") (pinfunction "42_~42") (pintype "bidirectional"))
      (node (ref "R57") (pin "1") (pinfunction "1_1") (pintype "passive"))
    )
    (net (code "30") (name "GPIO0_20") (class "Default")
      (node (ref "J32") (pin "23") (pinfunction "23_23") (pintype "passive"))
      (node (ref "MD1") (pin "~41") (pinfunction "41_~41") (pintype "bidirectional"))
      (node (ref "R60") (pin "2") (pinfunction "2_2") (pintype "passive"))
    )
    (net (code "31") (name "GPIO0_23") (class "Default")
      (node (ref "J29") (pin "2") (pinfunction "2_2") (pintype "passive"))
      (node (ref "MD1") (pin "13") (pinfunction "13_13") (pintype "bidirectional"))
      (node (ref "R34") (pin "1") (pinfunction "1_1") (pintype "passive"))
    )
    (net (code "32") (name "GPIO1_12") (class "Default")
      (node (ref "J32") (pin "14") (pinfunction "14_14") (pintype "passive"))
      (node (ref "MD1") (pin "12") (pinfunction "12_12") (pintype "bidirectional"))
      (node (ref "R52") (pin "1") (pinfunction "1_1") (pintype "passive"))
    )
    (net (code "33") (name "GPIO1_13") (class "Default")
      (node (ref "J32") (pin "12") (pinfunction "12_12") (pintype "passive"))
      (node (ref "MD1") (pin "11") (pinfunction "11_11") (pintype "bidirectional"))
      (node (ref "R51") (pin "1") (pinfunction "1_1") (pintype "passive"))
      (node (ref "R82") (pin "2") (pinfunction "2_2") (pintype "passive"))
    )
    (net (code "34") (name "GPIO1_14") (class "Default")
      (node (ref "J32") (pin "19") (pinfunction "19_19") (pintype "passive"))
      (node (ref "MD1") (pin "16") (pinfunction "16_16") (pintype "bidirectional"))
      (node (ref "R37") (pin "2") (pinfunction "2_2") (pintype "passive"))
      (node (ref "R98") (pin "1") (pinfunction "1_1") (pintype "passive"))
    )
    (net (code "35") (name "GPIO1_15") (class "Default")
      (node (ref "J32") (pin "17") (pinfunction "17_17") (pintype "passive"))
      (node (ref "MD1") (pin "15") (pinfunction "15_15") (pintype "bidirectional"))
      (node (ref "R40") (pin "2") (pinfunction "2_2") (pintype "passive"))
    )
    (net (code "36") (name "GPIO2_3") (class "Default")
      (node (ref "J32") (pin "8") (pinfunction "8_8") (pintype "passive"))
      (node (ref "MD1") (pin "8") (pinfunction "8_8") (pintype "bidirectional"))
      (node (ref "R53") (pin "2") (pinfunction "2_2") (pintype "passive"))
    )
    (net (code "37") (name "GPIO2_5") (class "Default")
      (node (ref "J32") (pin "10") (pinfunction "10_10") (pintype "passive"))
      (node (ref "MD1") (pin "9") (pinfunction "9_9") (pintype "bidirectional"))
      (node (ref "R69") (pin "2") (pinfunction "2_2") (pintype "passive"))
    )
    (net (code "38") (name "I2C1_SCL") (class "Default")
      (node (ref "J32") (pin "16") (pinfunction "16_16") (pintype "passive"))
      (node (ref "J41") (pin "2") (pinfunction "2_2") (pintype "passive"))
      (node (ref "MD1") (pin "~17") (pinfunction "17_~17") (pintype "bidirectional"))
      (node (ref "R59") (pin "2") (pinfunction "2_2") (pintype "passive"))
    )
    (net (code "39") (name "I2C1_SDA") (class "Default")
      (node (ref "J32") (pin "18") (pinfunction "18_18") (pintype "passive"))
      (node (ref "J41") (pin "4") (pinfunction "4_4") (pintype "passive"))
      (node (ref "MD1") (pin "~18") (pinfunction "18_~18") (pintype "bidirectional"))
      (node (ref "R25") (pin "2") (pinfunction "2_2") (pintype "passive"))
    )
    (net (code "40") (name "I2C2-SCL") (class "Default")
      (node (ref "J30") (pin "4") (pinfunction "4_4") (pintype "passive"))
      (node (ref "MD1") (pin "~19") (pinfunction "19_~19") (pintype "bidirectional"))
      (node (ref "MD2") (pin "~3") (pinfunction "3_~3") (pintype "passive"))
      (node (ref "R33") (pin "2") (pinfunction "2_2") (pintype "passive"))
      (node (ref "U12") (pin "6") (pinfunction "SCL_6") (pintype "bidirectional"))
    )
    (net (code "41") (name "I2C2-SDA") (class "Default")
      (node (ref "J30") (pin "7") (pinfunction "7_7") (pintype "passive"))
      (node (ref "MD1") (pin "~20") (pinfunction "20_~20") (pintype "bidirectional"))
      (node (ref "MD2") (pin "~4") (pinfunction "4_~4") (pintype "passive"))
      (node (ref "R32") (pin "2") (pinfunction "2_2") (pintype "passive"))
      (node (ref "U12") (pin "5") (pinfunction "SDA_5") (pintype "bidirectional"))
    )
    (net (code "42") (name "I2C{slash}~{SPI}") (class "Default")
      (node (ref "J10") (pin "2") (pinfunction "2_2") (pintype "passive"))
      (node (ref "R36") (pin "1") (pinfunction "1_1") (pintype "passive"))
      (node (ref "U11") (pin "8") (pinfunction "I2C/~{SPI}_8") (pintype "bidirectional"))
    )
    (net (code "43") (name "KNX_3.3V") (class "Default")
      (node (ref "J21") (pin "8") (pinfunction "8_8") (pintype "passive"))
      (node (ref "J22") (pin "1") (pinfunction "1_1") (pintype "passive"))
      (node (ref "J22") (pin "2") (pinfunction "2_2") (pintype "passive"))
      (node (ref "J22") (pin "3") (pinfunction "3_3") (pintype "passive"))
      (node (ref "MD6") (pin "23") (pinfunction "3.3V_23") (pintype "bidirectional"))
      (node (ref "R31") (pin "1") (pinfunction "1_1") (pintype "passive"))
      (node (ref "R38") (pin "2") (pinfunction "2_2") (pintype "passive"))
    )
    (net (code "44") (name "KNX_3.3V_DIV") (class "Default")
      (node (ref "C23") (pin "1") (pinfunction "+_1") (pintype "passive"))
      (node (ref "R38") (pin "1") (pinfunction "1_1") (pintype "passive"))
      (node (ref "R39") (pin "2") (pinfunction "2_2") (pintype "passive"))
      (node (ref "U15") (pin "11") (pinfunction "S3_11") (pintype "bidirectional"))
    )
    (net (code "45") (name "KNX_ANAOUT") (class "Default")
      (node (ref "J21") (pin "3") (pinfunction "3_3") (pintype "passive"))
      (node (ref "MD6") (pin "5") (pinfunction "ANAOUT_5") (pintype "bidirectional"))
      (node (ref "R41") (pin "2") (pinfunction "2_2") (pintype "passive"))
    )
    (net (code "46") (name "KNX_ANAOUT_DIV") (class "Default")
      (node (ref "C22") (pin "1") (pinfunction "+_1") (pintype "passive"))
      (node (ref "R41") (pin "1") (pinfunction "1_1") (pintype "passive"))
      (node (ref "R42") (pin "2") (pinfunction "2_2") (pintype "passive"))
      (node (ref "U14") (pin "6") (pinfunction "S4_6") (pintype "bidirectional"))
    )
    (net (code "47") (name "KNX_CSB") (class "Default")
      (node (ref "J23") (pin "2") (pinfunction "2_2") (pintype "passive"))
      (node (ref "MD6") (pin "18") (pinfunction "CSB_18") (pintype "bidirectional"))
    )
    (net (code "48") (name "KNX_RESETB") (class "Default")
      (node (ref "J21") (pin "5") (pinfunction "5_5") (pintype "passive"))
      (node (ref "MD6") (pin "8") (pinfunction "KNX_RESETB_8") (pintype "bidirectional"))
    )
    (net (code "49") (name "KNX_RX") (class "Default")
      (node (ref "MD6") (pin "15") (pinfunction "RXD_15") (pintype "bidirectional"))
      (node (ref "R31") (pin "2") (pinfunction "2_2") (pintype "passive"))
      (node (ref "U24") (pin "2") (pinfunction "1A_2") (pintype "input"))
      (node (ref "U8") (pin "3") (pinfunction "2Y_3") (pintype "output"))
    )
    (net (code "50") (name "KNX_SAVEB") (class "Default")
      (node (ref "J21") (pin "4") (pinfunction "4_4") (pintype "passive"))
      (node (ref "MD6") (pin "7") (pinfunction "SAVEB_7") (pintype "bidirectional"))
      (node (ref "U13") (pin "2") (pinfunction "1A_2") (pintype "input"))
    )
    (net (code "51") (name "KNX_SCK") (class "Default")
      (node (ref "J23") (pin "3") (pinfunction "3_3") (pintype "passive"))
      (node (ref "MD6") (pin "14") (pinfunction "SCK_14") (pintype "bidirectional"))
    )
    (net (code "52") (name "KNX_TRIG") (class "Default")
      (node (ref "J21") (pin "7") (pinfunction "7_7") (pintype "passive"))
      (node (ref "MD6") (pin "22") (pinfunction "TRIG_22") (pintype "bidirectional"))
      (node (ref "U13") (pin "5") (pinfunction "2A_5") (pintype "input"))
    )
    (net (code "53") (name "KNX_TX") (class "Default")
      (node (ref "MD6") (pin "16") (pinfunction "TXD_16") (pintype "bidirectional"))
      (node (ref "U24") (pin "5") (pinfunction "2A_5") (pintype "input"))
      (node (ref "U8") (pin "2") (pinfunction "1A_2") (pintype "input"))
    )
    (net (code "54") (name "KNX_V2") (class "Default")
      (node (ref "J21") (pin "1") (pinfunction "1_1") (pintype "passive"))
      (node (ref "MD6") (pin "1") (pinfunction "KNX_V2_1") (pintype "bidirectional"))
    )
    (net (code "55") (name "KNX_V20V") (class "Default")
      (node (ref "J21") (pin "2") (pinfunction "2_2") (pintype "passive"))
      (node (ref "MD6") (pin "3") (pinfunction "KNX_V20V_3") (pintype "bidirectional"))
    )
    (net (code "56") (name "KNX_XCLK") (class "Default")
      (node (ref "J21") (pin "6") (pinfunction "6_6") (pintype "passive"))
      (node (ref "MD6") (pin "11") (pinfunction "KNX_XCLK_11") (pintype "bidirectional"))
    )
    (net (code "57") (name "KNX_XCLKC") (class "Default")
      (node (ref "J23") (pin "1") (pinfunction "1_1") (pintype "passive"))
      (node (ref "MD6") (pin "21") (pinfunction "XCLKC_21") (pintype "bidirectional"))
    )
    (net (code "58") (name "LCD_DATA0") (class "Default")
      (node (ref "MD2") (pin "24") (pinfunction "24_24") (pintype "passive"))
      (node (ref "R1") (pin "1") (pinfunction "1_1") (pintype "passive"))
    )
    (net (code "59") (name "LCD_DATA1") (class "Default")
      (node (ref "MD2") (pin "25") (pinfunction "25_25") (pintype "passive"))
      (node (ref "R2") (pin "2") (pinfunction "2_2") (pintype "passive"))
    )
    (net (code "60") (name "LCD_DATA2") (class "Default")
      (node (ref "MD2") (pin "26") (pinfunction "26_26") (pintype "passive"))
      (node (ref "R3") (pin "1") (pinfunction "1_1") (pintype "passive"))
    )
    (net (code "61") (name "LCD_DATA3") (class "Default")
      (node (ref "MD2") (pin "27") (pinfunction "27_27") (pintype "passive"))
      (node (ref "R4") (pin "2") (pinfunction "2_2") (pintype "passive"))
    )
    (net (code "62") (name "LCD_DATA4") (class "Default")
      (node (ref "MD2") (pin "28") (pinfunction "28_28") (pintype "passive"))
      (node (ref "R5") (pin "1") (pinfunction "1_1") (pintype "passive"))
    )
    (net (code "63") (name "LCD_DATA5") (class "Default")
      (node (ref "MD2") (pin "15") (pinfunction "15_15") (pintype "passive"))
      (node (ref "R6") (pin "2") (pinfunction "2_2") (pintype "passive"))
    )
    (net (code "64") (name "LCD_DATA6") (class "Default")
      (node (ref "MD2") (pin "16") (pinfunction "16_16") (pintype "passive"))
      (node (ref "R7") (pin "1") (pinfunction "1_1") (pintype "passive"))
    )
    (net (code "65") (name "LCD_DATA7") (class "Default")
      (node (ref "MD2") (pin "17") (pinfunction "17_17") (pintype "passive"))
      (node (ref "R8") (pin "2") (pinfunction "2_2") (pintype "passive"))
    )
    (net (code "66") (name "LCD_DATA8") (class "Default")
      (node (ref "MD2") (pin "18") (pinfunction "18_18") (pintype "passive"))
      (node (ref "R9") (pin "1") (pinfunction "1_1") (pintype "passive"))
    )
    (net (code "67") (name "LCD_DATA9") (class "Default")
      (node (ref "MD2") (pin "19") (pinfunction "19_19") (pintype "passive"))
      (node (ref "R10") (pin "2") (pinfunction "2_2") (pintype "passive"))
    )
    (net (code "68") (name "LCD_DATA10") (class "Default")
      (node (ref "MD2") (pin "20") (pinfunction "20_20") (pintype "passive"))
      (node (ref "R12") (pin "2") (pinfunction "2_2") (pintype "passive"))
    )
    (net (code "69") (name "LCD_DATA11") (class "Default")
      (node (ref "MD2") (pin "8") (pinfunction "8_8") (pintype "passive"))
      (node (ref "R14") (pin "2") (pinfunction "2_2") (pintype "passive"))
    )
    (net (code "70") (name "LCD_DATA12") (class "Default")
      (node (ref "MD2") (pin "9") (pinfunction "9_9") (pintype "passive"))
      (node (ref "R11") (pin "1") (pinfunction "1_1") (pintype "passive"))
    )
    (net (code "71") (name "LCD_DATA13") (class "Default")
      (node (ref "MD2") (pin "10") (pinfunction "10_10") (pintype "passive"))
      (node (ref "R13") (pin "1") (pinfunction "1_1") (pintype "passive"))
    )
    (net (code "72") (name "LCD_DATA14") (class "Default")
      (node (ref "MD2") (pin "11") (pinfunction "11_11") (pintype "passive"))
      (node (ref "R15") (pin "1") (pinfunction "1_1") (pintype "passive"))
    )
    (net (code "73") (name "LCD_DATA15") (class "Default")
      (node (ref "MD2") (pin "12") (pinfunction "12_12") (pintype "passive"))
      (node (ref "R16") (pin "2") (pinfunction "2_2") (pintype "passive"))
    )
    (net (code "74") (name "LCD_DATA_EN") (class "Default")
      (node (ref "MD2") (pin "34") (pinfunction "34_34") (pintype "passive"))
      (node (ref "R18") (pin "2") (pinfunction "2_2") (pintype "passive"))
    )
    (net (code "75") (name "LCD_DISP") (class "Default")
      (node (ref "MD2") (pin "31") (pinfunction "31_31") (pintype "passive"))
      (node (ref "R66") (pin "2") (pinfunction "2_2") (pintype "passive"))
    )
    (net (code "76") (name "LCD_HSYNC") (class "Default")
      (node (ref "MD2") (pin "32") (pinfunction "32_32") (pintype "passive"))
      (node (ref "R17") (pin "1") (pinfunction "1_1") (pintype "passive"))
    )
    (net (code "77") (name "LCD_INT") (class "Default")
      (node (ref "J29") (pin "5") (pinfunction "5_5") (pintype "passive"))
      (node (ref "MD1") (pin "10") (pinfunction "10_10") (pintype "bidirectional"))
      (node (ref "R67") (pin "2") (pinfunction "2_2") (pintype "passive"))
    )
    (net (code "78") (name "LCD_PCLK") (class "Default")
      (node (ref "MD2") (pin "30") (pinfunction "30_30") (pintype "passive"))
      (node (ref "R20") (pin "2") (pinfunction "2_2") (pintype "passive"))
    )
    (net (code "79") (name "LCD_TEST_V") (class "Default")
      (node (ref "J31") (pin "2") (pinfunction "2_2") (pintype "passive"))
      (node (ref "U14") (pin "14") (pinfunction "S2_14") (pintype "bidirectional"))
    )
    (net (code "80") (name "LCD_VSYNC") (class "Default")
      (node (ref "MD2") (pin "33") (pinfunction "33_33") (pintype "passive"))
      (node (ref "R19") (pin "1") (pinfunction "1_1") (pintype "passive"))
    )
    (net (code "81") (name "LED_A") (class "Default")
      (node (ref "C6") (pin "1") (pinfunction "+_1") (pintype "passive"))
      (node (ref "D5") (pin "C") (pinfunction "C_C") (pintype "passive"))
      (node (ref "J31") (pin "1") (pinfunction "1_1") (pintype "passive"))
      (node (ref "MD2") (pin "2") (pinfunction "2_2") (pintype "passive"))
    )
    (net (code "82") (name "LED_HEARTBEAT") (class "Default")
      (node (ref "MD1") (pin "~12") (pinfunction "12_~12") (pintype "bidirectional"))
      (node (ref "U25") (pin "2") (pinfunction "1A_2") (pintype "input"))
    )
    (net (code "83") (name "LED_K") (class "Default")
      (node (ref "J31") (pin "3") (pinfunction "3_3") (pintype "passive"))
      (node (ref "MD2") (pin "1") (pinfunction "1_1") (pintype "passive"))
      (node (ref "R26") (pin "2") (pinfunction "2_2") (pintype "passive"))
      (node (ref "R27") (pin "2") (pinfunction "2_2") (pintype "passive"))
      (node (ref "R28") (pin "2") (pinfunction "2_2") (pintype "passive"))
    )
    (net (code "84") (name "LEFT_BUT") (class "Default")
      (node (ref "MD1") (pin "~15") (pinfunction "15_~15") (pintype "bidirectional"))
      (node (ref "R80") (pin "1") (pinfunction "1_1") (pintype "passive"))
      (node (ref "S6") (pin "1") (pinfunction "S_1") (pintype "passive"))
      (node (ref "S6") (pin "2") (pinfunction "S1_2") (pintype "passive"))
    )
    (net (code "85") (name "MMC1_CLK") (class "Default")
      (node (ref "J33") (pin "15") (pinfunction "15_15") (pintype "passive"))
      (node (ref "MD1") (pin "21") (pinfunction "21_21") (pintype "bidirectional"))
    )
    (net (code "86") (name "MMC1_CMD") (class "Default")
      (node (ref "J33") (pin "13") (pinfunction "13_13") (pintype "passive"))
      (node (ref "MD1") (pin "20") (pinfunction "20_20") (pintype "bidirectional"))
    )
    (net (code "87") (name "MMC1_DAT0") (class "Default")
      (node (ref "J33") (pin "16") (pinfunction "16_16") (pintype "passive"))
      (node (ref "MD1") (pin "25") (pinfunction "25_25") (pintype "bidirectional"))
    )
    (net (code "88") (name "MMC1_DAT1") (class "Default")
      (node (ref "J33") (pin "18") (pinfunction "18_18") (pintype "passive"))
      (node (ref "MD1") (pin "24") (pinfunction "24_24") (pintype "bidirectional"))
    )
    (net (code "89") (name "MMC1_DAT2") (class "Default")
      (node (ref "J33") (pin "7") (pinfunction "7_7") (pintype "passive"))
      (node (ref "MD1") (pin "5") (pinfunction "5_5") (pintype "bidirectional"))
    )
    (net (code "90") (name "MMC1_DAT3") (class "Default")
      (node (ref "J33") (pin "11") (pinfunction "11_11") (pintype "passive"))
      (node (ref "MD1") (pin "6") (pinfunction "6_6") (pintype "bidirectional"))
    )
    (net (code "91") (name "MMC1_DAT4") (class "Default")
      (node (ref "J33") (pin "20") (pinfunction "20_20") (pintype "passive"))
      (node (ref "MD1") (pin "23") (pinfunction "23_23") (pintype "bidirectional"))
    )
    (net (code "92") (name "MMC1_DAT5") (class "Default")
      (node (ref "J33") (pin "17") (pinfunction "17_17") (pintype "passive"))
      (node (ref "MD1") (pin "22") (pinfunction "22_22") (pintype "bidirectional"))
    )
    (net (code "93") (name "MMC1_DAT6") (class "Default")
      (node (ref "J33") (pin "3") (pinfunction "3_3") (pintype "passive"))
      (node (ref "MD1") (pin "3") (pinfunction "3_3") (pintype "bidirectional"))
    )
    (net (code "94") (name "MMC1_DAT7") (class "Default")
      (node (ref "J33") (pin "5") (pinfunction "5_5") (pintype "passive"))
      (node (ref "MD1") (pin "4") (pinfunction "4_4") (pintype "bidirectional"))
    )
    (net (code "95") (name "Net-(C1-+)") (class "Default")
      (node (ref "C1") (pin "1") (pinfunction "+_1") (pintype "passive"))
      (node (ref "J12") (pin "3") (pinfunction "3_3") (pintype "passive"))
      (node (ref "R22") (pin "1") (pinfunction "1_1") (pintype "passive"))
    )
    (net (code "96") (name "Net-(C2-+)") (class "Default")
      (node (ref "C2") (pin "1") (pinfunction "+_1") (pintype "passive"))
      (node (ref "J12") (pin "2") (pinfunction "2_2") (pintype "passive"))
      (node (ref "R21") (pin "1") (pinfunction "1_1") (pintype "passive"))
    )
    (net (code "97") (name "Net-(C14-+)") (class "Default")
      (node (ref "C14") (pin "1") (pinfunction "+_1") (pintype "passive"))
      (node (ref "R47") (pin "1") (pinfunction "1_1") (pintype "passive"))
      (node (ref "R48") (pin "1") (pinfunction "1_1") (pintype "passive"))
    )
    (net (code "98") (name "Net-(C19-+)") (class "Default")
      (node (ref "C19") (pin "1") (pinfunction "+_1") (pintype "passive"))
      (node (ref "R65") (pin "2") (pinfunction "2_2") (pintype "passive"))
      (node (ref "U20") (pin "5") (pinfunction "OUT2_5") (pintype "bidirectional"))
      (node (ref "U20") (pin "8") (pinfunction "OUT1_8") (pintype "bidirectional"))
    )
    (net (code "99") (name "Net-(C20-+)") (class "Default")
      (node (ref "C20") (pin "1") (pinfunction "+_1") (pintype "passive"))
      (node (ref "FB2") (pin "2") (pinfunction "P$2_2") (pintype "bidirectional"))
      (node (ref "MD2") (pin "4") (pinfunction "4_4") (pintype "passive"))
    )
    (net (code "100") (name "Net-(C30-+)") (class "Default")
      (node (ref "C30") (pin "1") (pinfunction "+_1") (pintype "passive"))
      (node (ref "C31") (pin "1") (pinfunction "+_1") (pintype "passive"))
      (node (ref "FB1") (pin "1") (pinfunction "P$1_1") (pintype "bidirectional"))
      (node (ref "U5") (pin "15") (pinfunction "VCC_15") (pintype "power_in"))
    )
    (net (code "101") (name "Net-(C38-+)") (class "Default")
      (node (ref "C38") (pin "1") (pinfunction "+_1") (pintype "passive"))
      (node (ref "J40") (pin "2") (pinfunction "2_2") (pintype "passive"))
      (node (ref "MD5") (pin "2") (pinfunction "VMCU_2") (pintype "bidirectional"))
      (node (ref "U17") (pin "1") (pinfunction "+V1_1") (pintype "bidirectional"))
    )
    (net (code "102") (name "Net-(C38--)") (class "Default")
      (node (ref "C38") (pin "2") (pinfunction "-_2") (pintype "passive"))
      (node (ref "J40") (pin "3") (pinfunction "3_3") (pintype "passive"))
      (node (ref "MD5") (pin "3") (pinfunction "3_3") (pintype "bidirectional"))
      (node (ref "MD5") (pin "`3") (pinfunction "GND_`3") (pintype "bidirectional"))
      (node (ref "U17") (pin "4") (pinfunction "GND1_4") (pintype "bidirectional"))
    )
    (net (code "103") (name "Net-(C48-+)") (class "Default")
      (node (ref "C48") (pin "1") (pinfunction "+_1") (pintype "passive"))
      (node (ref "MD1") (pin "~5") (pinfunction "5_~5") (pintype "bidirectional"))
      (node (ref "MD1") (pin "~6") (pinfunction "6_~6") (pintype "bidirectional"))
      (node (ref "R64") (pin "1") (pinfunction "1_1") (pintype "passive"))
    )
    (net (code "104") (name "Net-(C49-+)") (class "Default")
      (node (ref "C49") (pin "1") (pinfunction "+_1") (pintype "passive"))
      (node (ref "U20") (pin "7") (pinfunction "CT_7") (pintype "bidirectional"))
    )
    (net (code "105") (name "Net-(D1-PadC)") (class "Default")
      (node (ref "D1") (pin "C") (pinfunction "C_C") (pintype "passive"))
      (node (ref "R24") (pin "1") (pinfunction "1_1") (pintype "passive"))
    )
    (net (code "106") (name "Net-(D2-PadC)") (class "Default")
      (node (ref "D2") (pin "C") (pinfunction "C_C") (pintype "passive"))
      (node (ref "R23") (pin "1") (pinfunction "1_1") (pintype "passive"))
    )
    (net (code "107") (name "Net-(D3-PadC)") (class "Default")
      (node (ref "D3") (pin "C") (pinfunction "C_C") (pintype "passive"))
      (node (ref "R55") (pin "1") (pinfunction "1_1") (pintype "passive"))
    )
    (net (code "108") (name "Net-(D6-PadA)") (class "Default")
      (node (ref "D6") (pin "A") (pinfunction "A_A") (pintype "passive"))
      (node (ref "R83") (pin "2") (pinfunction "2_2") (pintype "passive"))
    )
    (net (code "109") (name "Net-(D8-PadA)") (class "Default")
      (node (ref "D8") (pin "A") (pinfunction "A_A") (pintype "passive"))
      (node (ref "R85") (pin "2") (pinfunction "2_2") (pintype "passive"))
    )
    (net (code "110") (name "Net-(D9-PadA)") (class "Default")
      (node (ref "D9") (pin "A") (pinfunction "A_A") (pintype "passive"))
      (node (ref "R86") (pin "2") (pinfunction "2_2") (pintype "passive"))
    )
    (net (code "111") (name "Net-(D10-PadA)") (class "Default")
      (node (ref "D10") (pin "A") (pinfunction "A_A") (pintype "passive"))
      (node (ref "R87") (pin "2") (pinfunction "2_2") (pintype "passive"))
    )
    (net (code "112") (name "Net-(D11-PadA)") (class "Default")
      (node (ref "D11") (pin "A") (pinfunction "A_A") (pintype "passive"))
      (node (ref "R88") (pin "2") (pinfunction "2_2") (pintype "passive"))
    )
    (net (code "113") (name "Net-(D12-PadA)") (class "Default")
      (node (ref "D12") (pin "A") (pinfunction "A_A") (pintype "passive"))
      (node (ref "R89") (pin "2") (pinfunction "2_2") (pintype "passive"))
    )
    (net (code "114") (name "Net-(D13-PadA)") (class "Default")
      (node (ref "D13") (pin "A") (pinfunction "A_A") (pintype "passive"))
      (node (ref "R90") (pin "2") (pinfunction "2_2") (pintype "passive"))
    )
    (net (code "115") (name "Net-(D14-PadA)") (class "Default")
      (node (ref "D14") (pin "A") (pinfunction "A_A") (pintype "passive"))
      (node (ref "R91") (pin "2") (pinfunction "2_2") (pintype "passive"))
    )
    (net (code "116") (name "Net-(D15-PadA)") (class "Default")
      (node (ref "D15") (pin "A") (pinfunction "A_A") (pintype "passive"))
      (node (ref "R92") (pin "2") (pinfunction "2_2") (pintype "passive"))
    )
    (net (code "117") (name "Net-(D16-PadC)") (class "Default")
      (node (ref "D16") (pin "C") (pinfunction "C_C") (pintype "passive"))
      (node (ref "R93") (pin "1") (pinfunction "1_1") (pintype "passive"))
    )
    (net (code "118") (name "Net-(D17-PadC)") (class "Default")
      (node (ref "D17") (pin "C") (pinfunction "C_C") (pintype "passive"))
      (node (ref "R94") (pin "1") (pinfunction "1_1") (pintype "passive"))
    )
    (net (code "119") (name "Net-(J13-Pad1)") (class "Default")
      (node (ref "J13") (pin "1") (pinfunction "1_1") (pintype "passive"))
      (node (ref "J17") (pin "1") (pinfunction "1_1") (pintype "passive"))
    )
    (net (code "120") (name "Net-(J13A-GND)") (class "Default")
      (node (ref "J13") (pin "2") (pinfunction "GND_2") (pintype "power_in"))
      (node (ref "J13") (pin "3") (pinfunction "GND_3") (pintype "power_in"))
      (node (ref "J13") (pin "4") (pinfunction "GND_4") (pintype "power_in"))
      (node (ref "J13") (pin "5") (pinfunction "GND_5") (pintype "power_in"))
      (node (ref "J17") (pin "2") (pinfunction "GND_2") (pintype "power_in"))
      (node (ref "J17") (pin "3") (pinfunction "GND_3") (pintype "power_in"))
      (node (ref "J17") (pin "4") (pinfunction "GND_4") (pintype "power_in"))
      (node (ref "J17") (pin "5") (pinfunction "GND_5") (pintype "power_in"))
    )
    (net (code "121") (name "Net-(J14-Pad1)") (class "Default")
      (node (ref "J14") (pin "1") (pinfunction "1_1") (pintype "passive"))
      (node (ref "J18") (pin "1") (pinfunction "1_1") (pintype "passive"))
    )
    (net (code "122") (name "Net-(J14A-GND)") (class "Default")
      (node (ref "J14") (pin "2") (pinfunction "GND_2") (pintype "power_in"))
      (node (ref "J14") (pin "3") (pinfunction "GND_3") (pintype "power_in"))
      (node (ref "J14") (pin "4") (pinfunction "GND_4") (pintype "power_in"))
      (node (ref "J14") (pin "5") (pinfunction "GND_5") (pintype "power_in"))
      (node (ref "J18") (pin "2") (pinfunction "GND_2") (pintype "power_in"))
      (node (ref "J18") (pin "3") (pinfunction "GND_3") (pintype "power_in"))
      (node (ref "J18") (pin "4") (pinfunction "GND_4") (pintype "power_in"))
      (node (ref "J18") (pin "5") (pinfunction "GND_5") (pintype "power_in"))
    )
    (net (code "123") (name "Net-(J35-Pad1)") (class "Default")
      (node (ref "J35") (pin "1") (pinfunction "1_1") (pintype "passive"))
      (node (ref "R63") (pin "2") (pinfunction "2_2") (pintype "passive"))
    )
    (net (code "124") (name "Net-(J35-Pad2)") (class "Default")
      (node (ref "J35") (pin "2") (pinfunction "2_2") (pintype "passive"))
      (node (ref "R72") (pin "2") (pinfunction "2_2") (pintype "passive"))
    )
    (net (code "125") (name "Net-(J36-Pad1)") (class "Default")
      (node (ref "J36") (pin "1") (pinfunction "1_1") (pintype "passive"))
      (node (ref "R73") (pin "1") (pinfunction "1_1") (pintype "passive"))
    )
    (net (code "126") (name "Net-(J38-Pad1)") (class "Default")
      (node (ref "J38") (pin "1") (pinfunction "1_1") (pintype "passive"))
      (node (ref "R74") (pin "1") (pinfunction "1_1") (pintype "passive"))
    )
    (net (code "127") (name "Net-(J40-Pad1)") (class "Default")
      (node (ref "J40") (pin "1") (pinfunction "1_1") (pintype "passive"))
      (node (ref "MD5") (pin "1") (pinfunction "1_1") (pintype "bidirectional"))
    )
    (net (code "128") (name "Net-(J40-Pad4)") (class "Default")
      (node (ref "J40") (pin "4") (pinfunction "4_4") (pintype "passive"))
      (node (ref "MD5") (pin "4") (pinfunction "4_4") (pintype "bidirectional"))
    )
    (net (code "129") (name "Net-(J40-Pad5)") (class "Default")
      (node (ref "J40") (pin "5") (pinfunction "5_5") (pintype "passive"))
      (node (ref "MD5") (pin "5") (pinfunction "5_5") (pintype "bidirectional"))
    )
    (net (code "130") (name "Net-(J40-Pad6)") (class "Default")
      (node (ref "J40") (pin "6") (pinfunction "6_6") (pintype "passive"))
      (node (ref "MD5") (pin "6") (pinfunction "6_6") (pintype "bidirectional"))
    )
    (net (code "131") (name "Net-(MD1-Pad26)") (class "Default")
      (node (ref "MD1") (pin "26") (pinfunction "26_26") (pintype "bidirectional"))
      (node (ref "R66") (pin "1") (pinfunction "1_1") (pintype "passive"))
    )
    (net (code "132") (name "Net-(MD1-Pad27)") (class "Default")
      (node (ref "MD1") (pin "27") (pinfunction "27_27") (pintype "bidirectional"))
      (node (ref "R19") (pin "2") (pinfunction "2_2") (pintype "passive"))
    )
    (net (code "133") (name "Net-(MD1-Pad28)") (class "Default")
      (node (ref "MD1") (pin "28") (pinfunction "28_28") (pintype "bidirectional"))
      (node (ref "R20") (pin "1") (pinfunction "1_1") (pintype "passive"))
    )
    (net (code "134") (name "Net-(MD1-Pad29)") (class "Default")
      (node (ref "MD1") (pin "29") (pinfunction "29_29") (pintype "bidirectional"))
      (node (ref "R17") (pin "2") (pinfunction "2_2") (pintype "passive"))
    )
    (net (code "135") (name "Net-(MD1-Pad30)") (class "Default")
      (node (ref "MD1") (pin "30") (pinfunction "30_30") (pintype "bidirectional"))
      (node (ref "R18") (pin "1") (pinfunction "1_1") (pintype "passive"))
    )
    (net (code "136") (name "Net-(MD1-Pad31)") (class "Default")
      (node (ref "MD1") (pin "31") (pinfunction "31_31") (pintype "bidirectional"))
      (node (ref "R15") (pin "2") (pinfunction "2_2") (pintype "passive"))
    )
    (net (code "137") (name "Net-(MD1-Pad32)") (class "Default")
      (node (ref "MD1") (pin "32") (pinfunction "32_32") (pintype "bidirectional"))
      (node (ref "R16") (pin "1") (pinfunction "1_1") (pintype "passive"))
    )
    (net (code "138") (name "Net-(MD1-Pad33)") (class "Default")
      (node (ref "MD1") (pin "33") (pinfunction "33_33") (pintype "bidirectional"))
      (node (ref "R13") (pin "2") (pinfunction "2_2") (pintype "passive"))
    )
    (net (code "139") (name "Net-(MD1-Pad34)") (class "Default")
      (node (ref "MD1") (pin "34") (pinfunction "34_34") (pintype "bidirectional"))
      (node (ref "R14") (pin "1") (pinfunction "1_1") (pintype "passive"))
    )
    (net (code "140") (name "Net-(MD1-Pad35)") (class "Default")
      (node (ref "MD1") (pin "35") (pinfunction "35_35") (pintype "bidirectional"))
      (node (ref "R11") (pin "2") (pinfunction "2_2") (pintype "passive"))
    )
    (net (code "141") (name "Net-(MD1-Pad36)") (class "Default")
      (node (ref "MD1") (pin "36") (pinfunction "36_36") (pintype "bidirectional"))
      (node (ref "R12") (pin "1") (pinfunction "1_1") (pintype "passive"))
    )
    (net (code "142") (name "Net-(MD1-Pad37)") (class "Default")
      (node (ref "MD1") (pin "37") (pinfunction "37_37") (pintype "bidirectional"))
      (node (ref "R9") (pin "2") (pinfunction "2_2") (pintype "passive"))
    )
    (net (code "143") (name "Net-(MD1-Pad38)") (class "Default")
      (node (ref "MD1") (pin "38") (pinfunction "38_38") (pintype "bidirectional"))
      (node (ref "R10") (pin "1") (pinfunction "1_1") (pintype "passive"))
    )
    (net (code "144") (name "Net-(MD1-Pad39)") (class "Default")
      (node (ref "MD1") (pin "39") (pinfunction "39_39") (pintype "bidirectional"))
      (node (ref "R7") (pin "2") (pinfunction "2_2") (pintype "passive"))
    )
    (net (code "145") (name "Net-(MD1-Pad40)") (class "Default")
      (node (ref "MD1") (pin "40") (pinfunction "40_40") (pintype "bidirectional"))
      (node (ref "R8") (pin "1") (pinfunction "1_1") (pintype "passive"))
    )
    (net (code "146") (name "Net-(MD1-Pad41)") (class "Default")
      (node (ref "MD1") (pin "41") (pinfunction "41_41") (pintype "bidirectional"))
      (node (ref "R5") (pin "2") (pinfunction "2_2") (pintype "passive"))
    )
    (net (code "147") (name "Net-(MD1-Pad42)") (class "Default")
      (node (ref "MD1") (pin "42") (pinfunction "42_42") (pintype "bidirectional"))
      (node (ref "R6") (pin "1") (pinfunction "1_1") (pintype "passive"))
    )
    (net (code "148") (name "Net-(MD1-Pad43)") (class "Default")
      (node (ref "MD1") (pin "43") (pinfunction "43_43") (pintype "bidirectional"))
      (node (ref "R3") (pin "2") (pinfunction "2_2") (pintype "passive"))
    )
    (net (code "149") (name "Net-(MD1-Pad44)") (class "Default")
      (node (ref "MD1") (pin "44") (pinfunction "44_44") (pintype "bidirectional"))
      (node (ref "R4") (pin "1") (pinfunction "1_1") (pintype "passive"))
    )
    (net (code "150") (name "Net-(MD1-Pad45)") (class "Default")
      (node (ref "MD1") (pin "45") (pinfunction "45_45") (pintype "bidirectional"))
      (node (ref "R1") (pin "2") (pinfunction "2_2") (pintype "passive"))
    )
    (net (code "151") (name "Net-(MD1-Pad46)") (class "Default")
      (node (ref "MD1") (pin "46") (pinfunction "46_46") (pintype "bidirectional"))
      (node (ref "R2") (pin "1") (pinfunction "1_1") (pintype "passive"))
    )
    (net (code "152") (name "Net-(MD1B-25)") (class "Default")
      (node (ref "MD1") (pin "~25") (pinfunction "25_~25") (pintype "bidirectional"))
      (node (ref "R35") (pin "1") (pinfunction "1_1") (pintype "passive"))
    )
    (net (code "153") (name "Net-(MD2B-5)") (class "Default")
      (node (ref "MD2") (pin "~5") (pinfunction "5_~5") (pintype "passive"))
      (node (ref "R67") (pin "1") (pinfunction "1_1") (pintype "passive"))
    )
    (net (code "154") (name "Net-(MD2B-6)") (class "Default")
      (node (ref "MD2") (pin "~6") (pinfunction "6_~6") (pintype "passive"))
      (node (ref "R68") (pin "2") (pinfunction "2_2") (pintype "passive"))
      (node (ref "R69") (pin "1") (pinfunction "1_1") (pintype "passive"))
    )
    (net (code "155") (name "Net-(MD3-PWM0{slash}RSSI)") (class "Default")
      (node (ref "D3") (pin "A") (pinfunction "A_A") (pintype "passive"))
      (node (ref "MD3") (pin "6") (pinfunction "PWM0/RSSI_6") (pintype "bidirectional"))
    )
    (net (code "156") (name "Net-(MD5A-1-Pad~1)") (class "Default")
      (node (ref "MD5") (pin "~1") (pinfunction "1_~1") (pintype "bidirectional"))
      (node (ref "MD5") (pin "~3") (pinfunction "1_~3") (pintype "bidirectional"))
      (node (ref "R65") (pin "1") (pinfunction "1_1") (pintype "passive"))
    )
    (net (code "157") (name "Net-(MD5C-RX)") (class "Default")
      (node (ref "MD5") (pin "`2") (pinfunction "RX_`2") (pintype "bidirectional"))
      (node (ref "U17") (pin "3") (pinfunction "OUT2_3") (pintype "bidirectional"))
    )
    (net (code "158") (name "Net-(MD5C-TX)") (class "Default")
      (node (ref "MD5") (pin "`1") (pinfunction "TX_`1") (pintype "bidirectional"))
      (node (ref "U17") (pin "2") (pinfunction "IN1_2") (pintype "bidirectional"))
    )
    (net (code "159") (name "Net-(U1-Y1)") (class "Default")
      (node (ref "U1") (pin "14") (pinfunction "Y1_14") (pintype "bidirectional"))
      (node (ref "U4") (pin "1") (pinfunction "1OE_1") (pintype "input"))
      (node (ref "U4") (pin "7") (pinfunction "2OE_7") (pintype "input"))
    )
    (net (code "160") (name "Net-(U1-Y2)") (class "Default")
      (node (ref "U1") (pin "13") (pinfunction "Y2_13") (pintype "bidirectional"))
      (node (ref "U6") (pin "1") (pinfunction "1OE_1") (pintype "input"))
      (node (ref "U6") (pin "7") (pinfunction "2OE_7") (pintype "input"))
    )
    (net (code "161") (name "Net-(U1-Y3)") (class "Default")
      (node (ref "U1") (pin "12") (pinfunction "Y3_12") (pintype "bidirectional"))
      (node (ref "U7") (pin "1") (pinfunction "1OE_1") (pintype "input"))
      (node (ref "U7") (pin "7") (pinfunction "2OE_7") (pintype "input"))
    )
    (net (code "162") (name "Net-(U1-Y4)") (class "Default")
      (node (ref "U1") (pin "11") (pinfunction "Y4_11") (pintype "bidirectional"))
      (node (ref "U8") (pin "1") (pinfunction "1OE_1") (pintype "input"))
      (node (ref "U8") (pin "7") (pinfunction "2OE_7") (pintype "input"))
    )
    (net (code "163") (name "Net-(U1-Y5)") (class "Default")
      (node (ref "U1") (pin "10") (pinfunction "Y5_10") (pintype "bidirectional"))
      (node (ref "U9") (pin "1") (pinfunction "1OE_1") (pintype "input"))
      (node (ref "U9") (pin "7") (pinfunction "2OE_7") (pintype "input"))
    )
    (net (code "164") (name "Net-(U1-Y6)") (class "Default")
      (node (ref "U1") (pin "9") (pinfunction "Y6_9") (pintype "bidirectional"))
      (node (ref "U10") (pin "1") (pinfunction "1OE_1") (pintype "input"))
      (node (ref "U10") (pin "7") (pinfunction "2OE_7") (pintype "input"))
    )
    (net (code "165") (name "Net-(U2-FB)") (class "Default")
      (node (ref "R28") (pin "1") (pinfunction "1_1") (pintype "passive"))
      (node (ref "U2") (pin "3") (pinfunction "FB_3") (pintype "bidirectional"))
    )
    (net (code "166") (name "Net-(U2-SW)") (class "Default")
      (node (ref "D5") (pin "A") (pinfunction "A_A") (pintype "passive"))
      (node (ref "L1") (pin "2") (pinfunction "2_2") (pintype "bidirectional"))
      (node (ref "U2") (pin "1") (pinfunction "SW_1") (pintype "bidirectional"))
    )
    (net (code "167") (name "Net-(U3-STB)") (class "Default")
      (node (ref "R49") (pin "2") (pinfunction "2_2") (pintype "passive"))
      (node (ref "R51") (pin "2") (pinfunction "2_2") (pintype "passive"))
      (node (ref "U3") (pin "8") (pinfunction "STB_8") (pintype "bidirectional"))
    )
    (net (code "168") (name "Net-(U4-1A)") (class "Default")
      (node (ref "U4") (pin "2") (pinfunction "1A_2") (pintype "input"))
      (node (ref "U4") (pin "3") (pinfunction "2Y_3") (pintype "output"))
    )
    (net (code "169") (name "Net-(U5-CBUS0)") (class "Default")
      (node (ref "R24") (pin "2") (pinfunction "2_2") (pintype "passive"))
      (node (ref "U5") (pin "18") (pinfunction "CBUS0_18") (pintype "bidirectional"))
    )
    (net (code "170") (name "Net-(U5-CBUS1)") (class "Default")
      (node (ref "R23") (pin "2") (pinfunction "2_2") (pintype "passive"))
      (node (ref "U5") (pin "17") (pinfunction "CBUS1_17") (pintype "bidirectional"))
    )
    (net (code "171") (name "Net-(U5-RXD)") (class "Default")
      (node (ref "J16") (pin "3") (pinfunction "3_3") (pintype "passive"))
      (node (ref "J19") (pin "1") (pinfunction "1_1") (pintype "passive"))
      (node (ref "R50") (pin "2") (pinfunction "2_2") (pintype "passive"))
      (node (ref "U5") (pin "4") (pinfunction "RXD_4") (pintype "input"))
    )
    (net (code "172") (name "Net-(U5-TXD)") (class "Default")
      (node (ref "J16") (pin "4") (pinfunction "4_4") (pintype "passive"))
      (node (ref "J19") (pin "2") (pinfunction "2_2") (pintype "passive"))
      (node (ref "U5") (pin "20") (pinfunction "TXD_20") (pintype "output"))
    )
    (net (code "173") (name "Net-(U5-USBDM)") (class "Default")
      (node (ref "R21") (pin "2") (pinfunction "2_2") (pintype "passive"))
      (node (ref "U5") (pin "12") (pinfunction "USBDM_12") (pintype "bidirectional"))
    )
    (net (code "174") (name "Net-(U5-USBDP)") (class "Default")
      (node (ref "R22") (pin "2") (pinfunction "2_2") (pintype "passive"))
      (node (ref "U5") (pin "11") (pinfunction "USBDP_11") (pintype "bidirectional"))
    )
    (net (code "175") (name "Net-(U5-~{CTS})") (class "Default")
      (node (ref "J15") (pin "3") (pinfunction "3_3") (pintype "passive"))
      (node (ref "U5") (pin "9") (pinfunction "~{CTS}_9") (pintype "input"))
    )
    (net (code "176") (name "Net-(U5-~{DTR})") (class "Default")
      (node (ref "J15") (pin "5") (pinfunction "5_5") (pintype "passive"))
      (node (ref "U5") (pin "1") (pinfunction "~{DTR}_1") (pintype "output"))
    )
    (net (code "177") (name "Net-(U5-~{RI})") (class "Default")
      (node (ref "R53") (pin "1") (pinfunction "1_1") (pintype "passive"))
      (node (ref "R62") (pin "1") (pinfunction "1_1") (pintype "passive"))
      (node (ref "U5") (pin "5") (pinfunction "~{RI}_5") (pintype "input"))
    )
    (net (code "178") (name "Net-(U5-~{RTS})") (class "Default")
      (node (ref "J15") (pin "1") (pinfunction "1_1") (pintype "passive"))
      (node (ref "U5") (pin "2") (pinfunction "~{RTS}_2") (pintype "output"))
    )
    (net (code "179") (name "Net-(U12-A0)") (class "Default")
      (node (ref "R43") (pin "2") (pinfunction "2_2") (pintype "passive"))
      (node (ref "U12") (pin "1") (pinfunction "A0_1") (pintype "bidirectional"))
    )
    (net (code "180") (name "Net-(U12-A1)") (class "Default")
      (node (ref "R44") (pin "2") (pinfunction "2_2") (pintype "passive"))
      (node (ref "U12") (pin "2") (pinfunction "A1_2") (pintype "bidirectional"))
    )
    (net (code "181") (name "Net-(U12-A2)") (class "Default")
      (node (ref "J25") (pin "2") (pinfunction "2_2") (pintype "passive"))
      (node (ref "R45") (pin "2") (pinfunction "2_2") (pintype "passive"))
      (node (ref "U12") (pin "3") (pinfunction "A2_3") (pintype "bidirectional"))
    )
    (net (code "182") (name "Net-(U13-1Y)") (class "Default")
      (node (ref "R40") (pin "1") (pinfunction "1_1") (pintype "passive"))
      (node (ref "U13") (pin "6") (pinfunction "1Y_6") (pintype "output"))
    )
    (net (code "183") (name "Net-(U13-2Y)") (class "Default")
      (node (ref "R37") (pin "1") (pinfunction "1_1") (pintype "passive"))
      (node (ref "U13") (pin "3") (pinfunction "2Y_3") (pintype "output"))
    )
    (net (code "184") (name "Net-(U16-1A)") (class "Default")
      (node (ref "U16") (pin "2") (pinfunction "1A_2") (pintype "input"))
      (node (ref "U5") (pin "10") (pinfunction "CBUS2_10") (pintype "bidirectional"))
    )
    (net (code "185") (name "Net-(U16-1Y)") (class "Default")
      (node (ref "R60") (pin "1") (pinfunction "1_1") (pintype "passive"))
      (node (ref "U16") (pin "6") (pinfunction "1Y_6") (pintype "output"))
    )
    (net (code "186") (name "Net-(U16-2A)") (class "Default")
      (node (ref "R61") (pin "1") (pinfunction "1_1") (pintype "passive"))
      (node (ref "U16") (pin "5") (pinfunction "2A_5") (pintype "input"))
    )
    (net (code "187") (name "Net-(U16-2Y)") (class "Default")
      (node (ref "U16") (pin "3") (pinfunction "2Y_3") (pintype "output"))
      (node (ref "U5") (pin "19") (pinfunction "CBUS3_19") (pintype "bidirectional"))
    )
    (net (code "188") (name "Net-(U18-IN+)") (class "Default")
      (node (ref "R64") (pin "4") (pinfunction "4_4") (pintype "passive"))
      (node (ref "U18") (pin "1") (pinfunction "IN+_1") (pintype "bidirectional"))
    )
    (net (code "189") (name "Net-(U18-IN-)") (class "Default")
      (node (ref "R64") (pin "3") (pinfunction "3_3") (pintype "passive"))
      (node (ref "U18") (pin "8") (pinfunction "IN-_8") (pintype "bidirectional"))
    )
    (net (code "190") (name "Net-(U18-OUT)") (class "Default")
      (node (ref "R70") (pin "1") (pinfunction "1_1") (pintype "passive"))
      (node (ref "U18") (pin "4") (pinfunction "OUT_4") (pintype "bidirectional"))
    )
    (net (code "191") (name "Net-(U19-IN+)") (class "Default")
      (node (ref "R65") (pin "4") (pinfunction "4_4") (pintype "passive"))
      (node (ref "U19") (pin "1") (pinfunction "IN+_1") (pintype "bidirectional"))
    )
    (net (code "192") (name "Net-(U19-IN-)") (class "Default")
      (node (ref "R65") (pin "3") (pinfunction "3_3") (pintype "passive"))
      (node (ref "U19") (pin "8") (pinfunction "IN-_8") (pintype "bidirectional"))
    )
    (net (code "193") (name "Net-(U19-OUT)") (class "Default")
      (node (ref "R71") (pin "1") (pinfunction "1_1") (pintype "passive"))
      (node (ref "U19") (pin "4") (pinfunction "OUT_4") (pintype "bidirectional"))
    )
    (net (code "194") (name "Net-(U20-ON)") (class "Default")
      (node (ref "R56") (pin "1") (pinfunction "1_1") (pintype "passive"))
      (node (ref "R57") (pin "2") (pinfunction "2_2") (pintype "passive"))
      (node (ref "R99") (pin "2") (pinfunction "2_2") (pintype "passive"))
      (node (ref "U20") (pin "2") (pinfunction "ON_2") (pintype "bidirectional"))
    )
    (net (code "195") (name "Net-(U21-1Y)") (class "Default")
      (node (ref "D8") (pin "C") (pinfunction "C_C") (pintype "passive"))
      (node (ref "U21") (pin "6") (pinfunction "1Y_6") (pintype "output"))
    )
    (net (code "196") (name "Net-(U21-2Y)") (class "Default")
      (node (ref "D9") (pin "C") (pinfunction "C_C") (pintype "passive"))
      (node (ref "U21") (pin "3") (pinfunction "2Y_3") (pintype "output"))
    )
    (net (code "197") (name "Net-(U22-1Y)") (class "Default")
      (node (ref "D10") (pin "C") (pinfunction "C_C") (pintype "passive"))
      (node (ref "U22") (pin "6") (pinfunction "1Y_6") (pintype "output"))
    )
    (net (code "198") (name "Net-(U22-2Y)") (class "Default")
      (node (ref "D11") (pin "C") (pinfunction "C_C") (pintype "passive"))
      (node (ref "U22") (pin "3") (pinfunction "2Y_3") (pintype "output"))
    )
    (net (code "199") (name "Net-(U23-1Y)") (class "Default")
      (node (ref "D12") (pin "C") (pinfunction "C_C") (pintype "passive"))
      (node (ref "U23") (pin "6") (pinfunction "1Y_6") (pintype "output"))
    )
    (net (code "200") (name "Net-(U23-2Y)") (class "Default")
      (node (ref "D13") (pin "C") (pinfunction "C_C") (pintype "passive"))
      (node (ref "U23") (pin "3") (pinfunction "2Y_3") (pintype "output"))
    )
    (net (code "201") (name "Net-(U24-1Y)") (class "Default")
      (node (ref "D14") (pin "C") (pinfunction "C_C") (pintype "passive"))
      (node (ref "U24") (pin "6") (pinfunction "1Y_6") (pintype "output"))
    )
    (net (code "202") (name "Net-(U24-2Y)") (class "Default")
      (node (ref "D15") (pin "C") (pinfunction "C_C") (pintype "passive"))
      (node (ref "U24") (pin "3") (pinfunction "2Y_3") (pintype "output"))
    )
    (net (code "203") (name "Net-(U25-1Y)") (class "Default")
      (node (ref "D16") (pin "A") (pinfunction "A_A") (pintype "passive"))
      (node (ref "U25") (pin "6") (pinfunction "1Y_6") (pintype "output"))
    )
    (net (code "204") (name "Net-(U25-2A)") (class "Default")
      (node (ref "R98") (pin "2") (pinfunction "2_2") (pintype "passive"))
      (node (ref "U25") (pin "5") (pinfunction "2A_5") (pintype "input"))
    )
    (net (code "205") (name "Net-(U25-2Y)") (class "Default")
      (node (ref "D17") (pin "A") (pinfunction "A_A") (pintype "passive"))
      (node (ref "U25") (pin "3") (pinfunction "2Y_3") (pintype "output"))
    )
    (net (code "206") (name "PWR_BUT") (class "Default")
      (node (ref "J30") (pin "1") (pinfunction "1_1") (pintype "passive"))
      (node (ref "MD1") (pin "~9") (pinfunction "9_~9") (pintype "bidirectional"))
      (node (ref "S1") (pin "1") (pinfunction "S_1") (pintype "passive"))
      (node (ref "S1") (pin "2") (pinfunction "S1_2") (pintype "passive"))
    )
    (net (code "207") (name "READER_I-SENSE") (class "Default")
      (node (ref "C27") (pin "1") (pinfunction "+_1") (pintype "passive"))
      (node (ref "R71") (pin "2") (pinfunction "2_2") (pintype "passive"))
      (node (ref "U14") (pin "11") (pinfunction "S3_11") (pintype "bidirectional"))
    )
    (net (code "208") (name "READER_RX") (class "Default")
      (node (ref "J28") (pin "12") (pinfunction "12_12") (pintype "passive"))
      (node (ref "J30") (pin "3") (pinfunction "3_3") (pintype "passive"))
      (node (ref "MD1") (pin "~13") (pinfunction "13_~13") (pintype "bidirectional"))
      (node (ref "U17") (pin "6") (pinfunction "IN2_6") (pintype "bidirectional"))
      (node (ref "U22") (pin "2") (pinfunction "1A_2") (pintype "input"))
    )
    (net (code "209") (name "READER_TX") (class "Default")
      (node (ref "J28") (pin "10") (pinfunction "10_10") (pintype "passive"))
      (node (ref "J30") (pin "2") (pinfunction "2_2") (pintype "passive"))
      (node (ref "MD1") (pin "~11") (pinfunction "11_~11") (pintype "bidirectional"))
      (node (ref "U17") (pin "7") (pinfunction "OUT1_7") (pintype "bidirectional"))
      (node (ref "U22") (pin "5") (pinfunction "2A_5") (pintype "input"))
    )
    (net (code "210") (name "RESET") (class "Default")
      (node (ref "J29") (pin "4") (pinfunction "4_4") (pintype "passive"))
      (node (ref "MD1") (pin "19") (pinfunction "19_19") (pintype "bidirectional"))
      (node (ref "MD3") (pin "5") (pinfunction "~{RESET}_5") (pintype "input"))
      (node (ref "U11") (pin "14") (pinfunction "~{RESET}_14") (pintype "bidirectional"))
    )
    (net (code "211") (name "RIGHT_BUT") (class "Default")
      (node (ref "MD1") (pin "~23") (pinfunction "23_~23") (pintype "bidirectional"))
      (node (ref "R79") (pin "1") (pinfunction "1_1") (pintype "passive"))
      (node (ref "S5") (pin "1") (pinfunction "S_1") (pintype "passive"))
      (node (ref "S5") (pin "2") (pinfunction "S1_2") (pintype "passive"))
    )
    (net (code "212") (name "SCL{slash}SCLK") (class "Default")
      (node (ref "J28") (pin "7") (pinfunction "7_7") (pintype "passive"))
      (node (ref "J37") (pin "1") (pinfunction "1_1") (pintype "passive"))
      (node (ref "J37A") (pin "1") (pinfunction "1_1") (pintype "passive"))
      (node (ref "J38") (pin "2") (pinfunction "2_2") (pintype "passive"))
      (node (ref "J41") (pin "1") (pinfunction "1_1") (pintype "passive"))
      (node (ref "U11") (pin "5") (pinfunction "SCL/SCLK_5") (pintype "bidirectional"))
    )
    (net (code "213") (name "SDA") (class "Default")
      (node (ref "J36") (pin "2") (pinfunction "2_2") (pintype "passive"))
      (node (ref "J37") (pin "2") (pinfunction "2_2") (pintype "passive"))
      (node (ref "J37A") (pin "2") (pinfunction "2_2") (pintype "passive"))
      (node (ref "J41") (pin "3") (pinfunction "3_3") (pintype "passive"))
      (node (ref "U11") (pin "6") (pinfunction "SDA_6") (pintype "bidirectional"))
    )
    (net (code "214") (name "SO") (class "Default")
      (node (ref "J28") (pin "5") (pinfunction "5_5") (pintype "passive"))
      (node (ref "J37") (pin "3") (pinfunction "3_3") (pintype "passive"))
      (node (ref "J37A") (pin "3") (pinfunction "3_3") (pintype "passive"))
      (node (ref "U11") (pin "4") (pinfunction "SO_4") (pintype "bidirectional"))
    )
    (net (code "215") (name "SPI1_CS0") (class "Default")
      (node (ref "J28") (pin "2") (pinfunction "2_2") (pintype "passive"))
      (node (ref "J32") (pin "20") (pinfunction "20_20") (pintype "passive"))
      (node (ref "MD1") (pin "~28") (pinfunction "28_~28") (pintype "bidirectional"))
    )
    (net (code "216") (name "SPI1_D0") (class "Default")
      (node (ref "J28") (pin "6") (pinfunction "6_6") (pintype "passive"))
      (node (ref "J32") (pin "22") (pinfunction "22_22") (pintype "passive"))
      (node (ref "MD1") (pin "~29") (pinfunction "29_~29") (pintype "bidirectional"))
    )
    (net (code "217") (name "SPI1_D1") (class "Default")
      (node (ref "J28") (pin "4") (pinfunction "4_4") (pintype "passive"))
      (node (ref "J32") (pin "24") (pinfunction "24_24") (pintype "passive"))
      (node (ref "MD1") (pin "~30") (pinfunction "30_~30") (pintype "bidirectional"))
    )
    (net (code "218") (name "SPI1_SCLK") (class "Default")
      (node (ref "J28") (pin "8") (pinfunction "8_8") (pintype "passive"))
      (node (ref "J32") (pin "26") (pinfunction "26_26") (pintype "passive"))
      (node (ref "MD1") (pin "~31") (pinfunction "31_~31") (pintype "bidirectional"))
    )
    (net (code "219") (name "SYS_5V") (class "Default")
      (node (ref "C24") (pin "2") (pinfunction "-_2") (pintype "passive"))
      (node (ref "C25") (pin "2") (pinfunction "-_2") (pintype "passive"))
      (node (ref "C32") (pin "1") (pinfunction "+_1") (pintype "passive"))
      (node (ref "C33") (pin "1") (pinfunction "+_1") (pintype "passive"))
      (node (ref "C35") (pin "1") (pinfunction "+_1") (pintype "passive"))
      (node (ref "C40") (pin "1") (pinfunction "+_1") (pintype "passive"))
      (node (ref "C5") (pin "1") (pinfunction "+_1") (pintype "passive"))
      (node (ref "J32") (pin "2") (pinfunction "2_2") (pintype "passive"))
      (node (ref "J33") (pin "2") (pinfunction "2_2") (pintype "passive"))
      (node (ref "L1") (pin "1") (pinfunction "1_1") (pintype "bidirectional"))
      (node (ref "MD1") (pin "~7") (pinfunction "7_~7") (pintype "bidirectional"))
      (node (ref "MD1") (pin "~8") (pinfunction "8_~8") (pintype "bidirectional"))
      (node (ref "U14") (pin "1") (pinfunction "IN1_1") (pintype "bidirectional"))
      (node (ref "U14") (pin "13") (pinfunction "VCC_13") (pintype "bidirectional"))
      (node (ref "U14") (pin "16") (pinfunction "IN2_16") (pintype "bidirectional"))
      (node (ref "U14") (pin "8") (pinfunction "IN4_8") (pintype "bidirectional"))
      (node (ref "U14") (pin "9") (pinfunction "IN3_9") (pintype "bidirectional"))
      (node (ref "U15") (pin "1") (pinfunction "IN1_1") (pintype "bidirectional"))
      (node (ref "U15") (pin "13") (pinfunction "VCC_13") (pintype "bidirectional"))
      (node (ref "U15") (pin "16") (pinfunction "IN2_16") (pintype "bidirectional"))
      (node (ref "U15") (pin "8") (pinfunction "IN4_8") (pintype "bidirectional"))
      (node (ref "U15") (pin "9") (pinfunction "IN3_9") (pintype "bidirectional"))
      (node (ref "U18") (pin "3") (pinfunction "VCC_3") (pintype "bidirectional"))
      (node (ref "U19") (pin "3") (pinfunction "VCC_3") (pintype "bidirectional"))
      (node (ref "U2") (pin "5") (pinfunction "VIN_5") (pintype "bidirectional"))
      (node (ref "U3") (pin "3") (pinfunction "VCC_3") (pintype "bidirectional"))
    )
    (net (code "220") (name "SYS_~{RESET}") (class "Default")
      (node (ref "J30") (pin "8") (pinfunction "8_8") (pintype "passive"))
      (node (ref "MD1") (pin "~10") (pinfunction "10_~10") (pintype "bidirectional"))
      (node (ref "R76") (pin "1") (pinfunction "1_1") (pintype "passive"))
      (node (ref "S2") (pin "1") (pinfunction "S_1") (pintype "passive"))
      (node (ref "S2") (pin "2") (pinfunction "S1_2") (pintype "passive"))
    )
    (net (code "221") (name "UART0_RX") (class "Default")
      (node (ref "J16") (pin "6") (pinfunction "6_6") (pintype "passive"))
      (node (ref "MD1") (pin "`4") (pinfunction "4_`4") (pintype "bidirectional"))
    )
    (net (code "222") (name "UART0_TX") (class "Default")
      (node (ref "J16") (pin "5") (pinfunction "5_5") (pintype "passive"))
      (node (ref "MD1") (pin "`5") (pinfunction "5_`5") (pintype "bidirectional"))
    )
    (net (code "223") (name "UART2_RX") (class "Default")
      (node (ref "J30") (pin "6") (pinfunction "6_6") (pintype "passive"))
      (node (ref "MD1") (pin "~22") (pinfunction "22_~22") (pintype "bidirectional"))
      (node (ref "U10") (pin "6") (pinfunction "1Y_6") (pintype "output"))
      (node (ref "U4") (pin "6") (pinfunction "1Y_6") (pintype "output"))
      (node (ref "U6") (pin "6") (pinfunction "1Y_6") (pintype "output"))
      (node (ref "U7") (pin "6") (pinfunction "1Y_6") (pintype "output"))
      (node (ref "U8") (pin "6") (pinfunction "1Y_6") (pintype "output"))
      (node (ref "U9") (pin "6") (pinfunction "1Y_6") (pintype "output"))
    )
    (net (code "224") (name "UART2_TX") (class "Default")
      (node (ref "J30") (pin "5") (pinfunction "5_5") (pintype "passive"))
      (node (ref "MD1") (pin "~21") (pinfunction "21_~21") (pintype "bidirectional"))
      (node (ref "U10") (pin "5") (pinfunction "2A_5") (pintype "input"))
      (node (ref "U4") (pin "5") (pinfunction "2A_5") (pintype "input"))
      (node (ref "U6") (pin "5") (pinfunction "2A_5") (pintype "input"))
      (node (ref "U7") (pin "5") (pinfunction "2A_5") (pintype "input"))
      (node (ref "U8") (pin "5") (pinfunction "2A_5") (pintype "input"))
      (node (ref "U9") (pin "5") (pinfunction "2A_5") (pintype "input"))
    )
    (net (code "225") (name "UART_3V3") (class "Default")
      (node (ref "C15") (pin "1") (pinfunction "+_1") (pintype "passive"))
      (node (ref "D1") (pin "A") (pinfunction "A_A") (pintype "passive"))
      (node (ref "D2") (pin "A") (pinfunction "A_A") (pintype "passive"))
      (node (ref "R50") (pin "1") (pinfunction "1_1") (pintype "passive"))
      (node (ref "U5") (pin "13") (pinfunction "3V3OUT_13") (pintype "output"))
      (node (ref "U5") (pin "14") (pinfunction "~{RESET}_14") (pintype "input"))
      (node (ref "U5") (pin "3") (pinfunction "VCCIO_3") (pintype "power_in"))
    )
    (net (code "226") (name "UART_MUX_0") (class "Default")
      (node (ref "J29") (pin "1") (pinfunction "1_1") (pintype "passive"))
      (node (ref "MD1") (pin "7") (pinfunction "7_7") (pintype "bidirectional"))
      (node (ref "U1") (pin "1") (pinfunction "A0_1") (pintype "bidirectional"))
    )
    (net (code "227") (name "UART_MUX_1") (class "Default")
      (node (ref "J29") (pin "6") (pinfunction "6_6") (pintype "passive"))
      (node (ref "MD1") (pin "14") (pinfunction "14_14") (pintype "bidirectional"))
      (node (ref "U1") (pin "2") (pinfunction "A1_2") (pintype "bidirectional"))
    )
    (net (code "228") (name "UART_MUX_2") (class "Default")
      (node (ref "J29") (pin "3") (pinfunction "3_3") (pintype "passive"))
      (node (ref "MD1") (pin "17") (pinfunction "17_17") (pintype "bidirectional"))
      (node (ref "U1") (pin "3") (pinfunction "A2_3") (pintype "bidirectional"))
    )
    (net (code "229") (name "UP_BUT") (class "Default")
      (node (ref "MD1") (pin "~16") (pinfunction "16_~16") (pintype "bidirectional"))
      (node (ref "R77") (pin "1") (pinfunction "1_1") (pintype "passive"))
      (node (ref "S3") (pin "1") (pinfunction "S_1") (pintype "passive"))
      (node (ref "S3") (pin "2") (pinfunction "S1_2") (pintype "passive"))
    )
    (net (code "230") (name "USB_5V") (class "Default")
      (node (ref "C3") (pin "1") (pinfunction "+_1") (pintype "passive"))
      (node (ref "FB1") (pin "2") (pinfunction "P$2_2") (pintype "bidirectional"))
      (node (ref "J12") (pin "1") (pinfunction "1_1") (pintype "passive"))
    )
    (net (code "231") (name "USB_UART_RX") (class "Default")
      (node (ref "J16") (pin "1") (pinfunction "1_1") (pintype "passive"))
      (node (ref "U10") (pin "3") (pinfunction "2Y_3") (pintype "output"))
    )
    (net (code "232") (name "USB_UART_TX") (class "Default")
      (node (ref "J16") (pin "2") (pinfunction "2_2") (pintype "passive"))
      (node (ref "R75") (pin "1") (pinfunction "1_1") (pintype "passive"))
      (node (ref "U10") (pin "2") (pinfunction "1A_2") (pintype "input"))
    )
    (net (code "233") (name "VDD_3V3B") (class "Default")
      (node (ref "C10") (pin "2") (pinfunction "-_2") (pintype "passive"))
      (node (ref "C11") (pin "2") (pinfunction "-_2") (pintype "passive"))
      (node (ref "C13") (pin "1") (pinfunction "+_1") (pintype "passive"))
      (node (ref "C16") (pin "1") (pinfunction "+_1") (pintype "passive"))
      (node (ref "C17") (pin "1") (pinfunction "+_1") (pintype "passive"))
      (node (ref "C21") (pin "2") (pinfunction "-_2") (pintype "passive"))
      (node (ref "C34") (pin "1") (pinfunction "+_1") (pintype "passive"))
      (node (ref "C36") (pin "1") (pinfunction "+_1") (pintype "passive"))
      (node (ref "C37") (pin "1") (pinfunction "+_1") (pintype "passive"))
      (node (ref "C39") (pin "1") (pinfunction "+_1") (pintype "passive"))
      (node (ref "C4") (pin "2") (pinfunction "-_2") (pintype "passive"))
      (node (ref "C41") (pin "1") (pinfunction "+_1") (pintype "passive"))
      (node (ref "C42") (pin "1") (pinfunction "+_1") (pintype "passive"))
      (node (ref "C43") (pin "2") (pinfunction "-_2") (pintype "passive"))
      (node (ref "C44") (pin "2") (pinfunction "-_2") (pintype "passive"))
      (node (ref "C45") (pin "2") (pinfunction "-_2") (pintype "passive"))
      (node (ref "C46") (pin "2") (pinfunction "-_2") (pintype "passive"))
      (node (ref "C47") (pin "2") (pinfunction "-_2") (pintype "passive"))
      (node (ref "C7") (pin "2") (pinfunction "-_2") (pintype "passive"))
      (node (ref "C8") (pin "2") (pinfunction "-_2") (pintype "passive"))
      (node (ref "C9") (pin "2") (pinfunction "-_2") (pintype "passive"))
      (node (ref "FB2") (pin "1") (pinfunction "P$1_1") (pintype "bidirectional"))
      (node (ref "J10") (pin "1") (pinfunction "1_1") (pintype "passive"))
      (node (ref "J32") (pin "4") (pinfunction "4_4") (pintype "passive"))
      (node (ref "J33") (pin "4") (pinfunction "4_4") (pintype "passive"))
      (node (ref "MD1") (pin "~3") (pinfunction "3_~3") (pintype "bidirectional"))
      (node (ref "MD1") (pin "~4") (pinfunction "4_~4") (pintype "bidirectional"))
      (node (ref "MD2") (pin "~1") (pinfunction "1_~1") (pintype "passive"))
      (node (ref "MD3") (pin "1") (pinfunction "VDD_1") (pintype "power_in"))
      (node (ref "R25") (pin "1") (pinfunction "1_1") (pintype "passive"))
      (node (ref "R29") (pin "1") (pinfunction "1_1") (pintype "passive"))
      (node (ref "R30") (pin "1") (pinfunction "1_1") (pintype "passive"))
      (node (ref "R32") (pin "1") (pinfunction "1_1") (pintype "passive"))
      (node (ref "R33") (pin "1") (pinfunction "1_1") (pintype "passive"))
      (node (ref "R43") (pin "1") (pinfunction "1_1") (pintype "passive"))
      (node (ref "R44") (pin "1") (pinfunction "1_1") (pintype "passive"))
      (node (ref "R45") (pin "1") (pinfunction "1_1") (pintype "passive"))
      (node (ref "R46") (pin "1") (pinfunction "1_1") (pintype "passive"))
      (node (ref "R56") (pin "2") (pinfunction "2_2") (pintype "passive"))
      (node (ref "R58") (pin "1") (pinfunction "1_1") (pintype "passive"))
      (node (ref "R59") (pin "1") (pinfunction "1_1") (pintype "passive"))
      (node (ref "R62") (pin "2") (pinfunction "2_2") (pintype "passive"))
      (node (ref "R63") (pin "1") (pinfunction "1_1") (pintype "passive"))
      (node (ref "R68") (pin "1") (pinfunction "1_1") (pintype "passive"))
      (node (ref "R72") (pin "1") (pinfunction "1_1") (pintype "passive"))
      (node (ref "R73") (pin "2") (pinfunction "2_2") (pintype "passive"))
      (node (ref "R74") (pin "2") (pinfunction "2_2") (pintype "passive"))
      (node (ref "R75") (pin "2") (pinfunction "2_2") (pintype "passive"))
      (node (ref "R76") (pin "2") (pinfunction "2_2") (pintype "passive"))
      (node (ref "R77") (pin "2") (pinfunction "2_2") (pintype "passive"))
      (node (ref "R78") (pin "2") (pinfunction "2_2") (pintype "passive"))
      (node (ref "R79") (pin "2") (pinfunction "2_2") (pintype "passive"))
      (node (ref "R80") (pin "2") (pinfunction "2_2") (pintype "passive"))
      (node (ref "R81") (pin "2") (pinfunction "2_2") (pintype "passive"))
      (node (ref "R83") (pin "1") (pinfunction "1_1") (pintype "passive"))
      (node (ref "R85") (pin "1") (pinfunction "1_1") (pintype "passive"))
      (node (ref "R86") (pin "1") (pinfunction "1_1") (pintype "passive"))
      (node (ref "R87") (pin "1") (pinfunction "1_1") (pintype "passive"))
      (node (ref "R88") (pin "1") (pinfunction "1_1") (pintype "passive"))
      (node (ref "R89") (pin "1") (pinfunction "1_1") (pintype "passive"))
      (node (ref "R90") (pin "1") (pinfunction "1_1") (pintype "passive"))
      (node (ref "R91") (pin "1") (pinfunction "1_1") (pintype "passive"))
      (node (ref "R92") (pin "1") (pinfunction "1_1") (pintype "passive"))
      (node (ref "U1") (pin "16") (pinfunction "VCC_16") (pintype "bidirectional"))
      (node (ref "U1") (pin "6") (pinfunction "OE0_6") (pintype "bidirectional"))
      (node (ref "U10") (pin "8") (pinfunction "VCC_8") (pintype "power_in"))
      (node (ref "U11") (pin "1") (pinfunction "VCC_1") (pintype "bidirectional"))
      (node (ref "U12") (pin "8") (pinfunction "VCC_8") (pintype "power_in"))
      (node (ref "U13") (pin "1") (pinfunction "1OE_1") (pintype "input"))
      (node (ref "U13") (pin "7") (pinfunction "2OE_7") (pintype "input"))
      (node (ref "U13") (pin "8") (pinfunction "VCC_8") (pintype "power_in"))
      (node (ref "U16") (pin "1") (pinfunction "1OE_1") (pintype "input"))
      (node (ref "U16") (pin "7") (pinfunction "2OE_7") (pintype "input"))
      (node (ref "U16") (pin "8") (pinfunction "VCC_8") (pintype "power_in"))
      (node (ref "U17") (pin "8") (pinfunction "+V2_8") (pintype "bidirectional"))
      (node (ref "U21") (pin "1") (pinfunction "1OE_1") (pintype "input"))
      (node (ref "U21") (pin "7") (pinfunction "2OE_7") (pintype "input"))
      (node (ref "U21") (pin "8") (pinfunction "VCC_8") (pintype "power_in"))
      (node (ref "U22") (pin "1") (pinfunction "1OE_1") (pintype "input"))
      (node (ref "U22") (pin "7") (pinfunction "2OE_7") (pintype "input"))
      (node (ref "U22") (pin "8") (pinfunction "VCC_8") (pintype "power_in"))
      (node (ref "U23") (pin "1") (pinfunction "1OE_1") (pintype "input"))
      (node (ref "U23") (pin "7") (pinfunction "2OE_7") (pintype "input"))
      (node (ref "U23") (pin "8") (pinfunction "VCC_8") (pintype "power_in"))
      (node (ref "U24") (pin "1") (pinfunction "1OE_1") (pintype "input"))
      (node (ref "U24") (pin "7") (pinfunction "2OE_7") (pintype "input"))
      (node (ref "U24") (pin "8") (pinfunction "VCC_8") (pintype "power_in"))
      (node (ref "U25") (pin "1") (pinfunction "1OE_1") (pintype "input"))
      (node (ref "U25") (pin "7") (pinfunction "2OE_7") (pintype "input"))
      (node (ref "U25") (pin "8") (pinfunction "VCC_8") (pintype "power_in"))
      (node (ref "U3") (pin "5") (pinfunction "VIO_5") (pintype "bidirectional"))
      (node (ref "U4") (pin "8") (pinfunction "VCC_8") (pintype "power_in"))
      (node (ref "U6") (pin "8") (pinfunction "VCC_8") (pintype "power_in"))
      (node (ref "U7") (pin "8") (pinfunction "VCC_8") (pintype "power_in"))
      (node (ref "U8") (pin "8") (pinfunction "VCC_8") (pintype "power_in"))
      (node (ref "U9") (pin "8") (pinfunction "VCC_8") (pintype "power_in"))
    )
    (net (code "234") (name "VDD_5V") (class "Default")
      (node (ref "C18") (pin "1") (pinfunction "+_1") (pintype "passive"))
      (node (ref "C28") (pin "A") (pinfunction "+_A") (pintype "passive"))
      (node (ref "C29") (pin "1") (pinfunction "+_1") (pintype "passive"))
      (node (ref "D4") (pin "C") (pinfunction "C_C") (pintype "passive"))
      (node (ref "F2") (pin "2") (pinfunction "2_2") (pintype "bidirectional"))
      (node (ref "J32") (pin "6") (pinfunction "6_6") (pintype "passive"))
      (node (ref "J33") (pin "6") (pinfunction "6_6") (pintype "passive"))
      (node (ref "R54") (pin "2") (pinfunction "2_2") (pintype "passive"))
      (node (ref "R64") (pin "2") (pinfunction "2_2") (pintype "passive"))
      (node (ref "U20") (pin "1") (pinfunction "IN1_1") (pintype "bidirectional"))
      (node (ref "U20") (pin "3") (pinfunction "VBIAS_3") (pintype "bidirectional"))
      (node (ref "U20") (pin "4") (pinfunction "IN2_4") (pintype "bidirectional"))
    )
    (net (code "235") (name "XBEE_AD3{slash}DIO3") (class "Default")
      (node (ref "J27") (pin "1") (pinfunction "1_1") (pintype "passive"))
      (node (ref "MD3") (pin "17") (pinfunction "AD3/DIO3_17") (pintype "bidirectional"))
    )
    (net (code "236") (name "XBEE_AD4{slash}DIO4") (class "Default")
      (node (ref "J27") (pin "5") (pinfunction "5_5") (pintype "passive"))
      (node (ref "MD3") (pin "11") (pinfunction "AD4/DIO4_11") (pintype "bidirectional"))
    )
    (net (code "237") (name "XBEE_AD5{slash}DIO5") (class "Default")
      (node (ref "J27") (pin "2") (pinfunction "2_2") (pintype "passive"))
      (node (ref "MD3") (pin "15") (pinfunction "ASSOC/AD5/DIO5_15") (pintype "bidirectional"))
    )
    (net (code "238") (name "XBEE_ON{slash}SLEEP") (class "Default")
      (node (ref "J27") (pin "4") (pinfunction "4_4") (pintype "passive"))
      (node (ref "MD3") (pin "13") (pinfunction "ON/~{SLEEP}_13") (pintype "bidirectional"))
    )
    (net (code "239") (name "XBEE_PWM1") (class "Default")
      (node (ref "J27") (pin "6") (pinfunction "6_6") (pintype "passive"))
      (node (ref "MD3") (pin "7") (pinfunction "PWM1_7") (pintype "bidirectional"))
    )
    (net (code "240") (name "XBEE_RX") (class "Default")
      (node (ref "J19") (pin "4") (pinfunction "4_4") (pintype "passive"))
      (node (ref "MD3") (pin "3") (pinfunction "DIN/~{CONFIG}_3") (pintype "input"))
      (node (ref "U21") (pin "2") (pinfunction "1A_2") (pintype "input"))
      (node (ref "U9") (pin "3") (pinfunction "2Y_3") (pintype "output"))
    )
    (net (code "241") (name "XBEE_TX") (class "Default")
      (node (ref "J19") (pin "3") (pinfunction "3_3") (pintype "passive"))
      (node (ref "MD3") (pin "2") (pinfunction "DOUT_2") (pintype "output"))
      (node (ref "U21") (pin "5") (pinfunction "2A_5") (pintype "input"))
      (node (ref "U9") (pin "2") (pinfunction "1A_2") (pintype "input"))
    )
    (net (code "242") (name "XBEE_VREF") (class "Default")
      (node (ref "J27") (pin "3") (pinfunction "3_3") (pintype "passive"))
      (node (ref "MD3") (pin "14") (pinfunction "VREF_14") (pintype "bidirectional"))
    )
    (net (code "243") (name "XBEE_~{CTS}") (class "Default")
      (node (ref "J15") (pin "4") (pinfunction "4_4") (pintype "passive"))
      (node (ref "MD3") (pin "12") (pinfunction "~{CTS}/DIO7_12") (pintype "output"))
    )
    (net (code "244") (name "XBEE_~{DTR}") (class "Default")
      (node (ref "J15") (pin "6") (pinfunction "6_6") (pintype "passive"))
      (node (ref "MD3") (pin "9") (pinfunction "~{DTR}/SLEEP_RQ/DI8_9") (pintype "bidirectional"))
    )
    (net (code "245") (name "XBEE_~{RTS}") (class "Default")
      (node (ref "J15") (pin "2") (pinfunction "2_2") (pintype "passive"))
      (node (ref "MD3") (pin "16") (pinfunction "~{RTS}/DIO6_16") (pintype "input"))
    )
    (net (code "246") (name "unconnected-(J12-Pad4)") (class "Default")
      (node (ref "J12") (pin "4") (pinfunction "4_4") (pintype "passive"))
    )
    (net (code "247") (name "unconnected-(J20-Pad2)") (class "Default")
      (node (ref "J20") (pin "2") (pinfunction "2_2") (pintype "passive"))
    )
    (net (code "248") (name "unconnected-(J20-Pad3)") (class "Default")
      (node (ref "J20") (pin "3") (pinfunction "3_3") (pintype "passive"))
    )
    (net (code "249") (name "unconnected-(J20A-Pad2)") (class "Default")
      (node (ref "J20A") (pin "2") (pinfunction "2_2") (pintype "passive"))
    )
    (net (code "250") (name "unconnected-(J20A-Pad3)") (class "Default")
      (node (ref "J20A") (pin "3") (pinfunction "3_3") (pintype "passive"))
    )
    (net (code "251") (name "unconnected-(J32-Pad3)") (class "Default")
      (node (ref "J32") (pin "3") (pinfunction "3_3") (pintype "passive"))
    )
    (net (code "252") (name "unconnected-(J32-Pad5)") (class "Default")
      (node (ref "J32") (pin "5") (pinfunction "5_5") (pintype "passive"))
    )
    (net (code "253") (name "unconnected-(J32-Pad11)") (class "Default")
      (node (ref "J32") (pin "11") (pinfunction "11_11") (pintype "passive"))
    )
    (net (code "254") (name "unconnected-(MD1B-32-Pad~32)") (class "Default")
      (node (ref "MD1") (pin "~32") (pinfunction "32_~32") (pintype "bidirectional"))
    )
    (net (code "255") (name "unconnected-(MD1C-2-Pad`2)") (class "Default")
      (node (ref "MD1") (pin "`2") (pinfunction "2_`2") (pintype "bidirectional"))
    )
    (net (code "256") (name "unconnected-(MD1C-3-Pad`3)") (class "Default")
      (node (ref "MD1") (pin "`3") (pinfunction "3_`3") (pintype "bidirectional"))
    )
    (net (code "257") (name "unconnected-(MD1C-6-Pad`6)") (class "Default")
      (node (ref "MD1") (pin "`6") (pinfunction "6_`6") (pintype "bidirectional"))
    )
    (net (code "258") (name "unconnected-(MD2-Pad35)") (class "Default")
      (node (ref "MD2") (pin "35") (pinfunction "35_35") (pintype "passive"))
    )
    (net (code "259") (name "unconnected-(MD2-Pad37)") (class "Default")
      (node (ref "MD2") (pin "37") (pinfunction "37_37") (pintype "passive"))
    )
    (net (code "260") (name "unconnected-(MD2-Pad38)") (class "Default")
      (node (ref "MD2") (pin "38") (pinfunction "38_38") (pintype "passive"))
    )
    (net (code "261") (name "unconnected-(MD2-Pad39)") (class "Default")
      (node (ref "MD2") (pin "39") (pinfunction "39_39") (pintype "passive"))
    )
    (net (code "262") (name "unconnected-(MD2-Pad40)") (class "Default")
      (node (ref "MD2") (pin "40") (pinfunction "40_40") (pintype "passive"))
    )
    (net (code "263") (name "unconnected-(MD3-AD0{slash}DIO0-Pad20)") (class "Default")
      (node (ref "MD3") (pin "20") (pinfunction "AD0/DIO0_20") (pintype "bidirectional"))
    )
    (net (code "264") (name "unconnected-(MD3-AD1{slash}DIO1-Pad19)") (class "Default")
      (node (ref "MD3") (pin "19") (pinfunction "AD1/DIO1_19") (pintype "bidirectional"))
    )
    (net (code "265") (name "unconnected-(MD3-AD2{slash}DIO2-Pad18)") (class "Default")
      (node (ref "MD3") (pin "18") (pinfunction "AD2/DIO2_18") (pintype "bidirectional"))
    )
    (net (code "266") (name "unconnected-(MD3-D08*-Pad4)") (class "Default")
      (node (ref "MD3") (pin "4") (pinfunction "D08*_4") (pintype "bidirectional"))
    )
    (net (code "267") (name "unconnected-(MD3-RESERVED-Pad8)") (class "Default")
      (node (ref "MD3") (pin "8") (pinfunction "RESERVED_8") (pintype "bidirectional"))
    )
    (net (code "268") (name "unconnected-(R84-Pad1)") (class "Default")
      (node (ref "R84") (pin "1") (pinfunction "1_1") (pintype "passive"))
    )
    (net (code "269") (name "unconnected-(R84-Pad2)") (class "Default")
      (node (ref "R84") (pin "2") (pinfunction "2_2") (pintype "passive"))
    )
    (net (code "270") (name "unconnected-(R95-Pad1)") (class "Default")
      (node (ref "R95") (pin "1") (pinfunction "1_1") (pintype "passive"))
    )
    (net (code "271") (name "unconnected-(R95-Pad2)") (class "Default")
      (node (ref "R95") (pin "2") (pinfunction "2_2") (pintype "passive"))
    )
    (net (code "272") (name "unconnected-(R96-Pad1)") (class "Default")
      (node (ref "R96") (pin "1") (pinfunction "1_1") (pintype "passive"))
    )
    (net (code "273") (name "unconnected-(R96-Pad2)") (class "Default")
      (node (ref "R96") (pin "2") (pinfunction "2_2") (pintype "passive"))
    )
    (net (code "274") (name "unconnected-(R97-Pad1)") (class "Default")
      (node (ref "R97") (pin "1") (pinfunction "1_1") (pintype "passive"))
    )
    (net (code "275") (name "unconnected-(R97-Pad2)") (class "Default")
      (node (ref "R97") (pin "2") (pinfunction "2_2") (pintype "passive"))
    )
    (net (code "276") (name "unconnected-(U1-Y0-Pad15)") (class "Default")
      (node (ref "U1") (pin "15") (pinfunction "Y0_15") (pintype "bidirectional"))
    )
    (net (code "277") (name "unconnected-(U1-Y7-Pad7)") (class "Default")
      (node (ref "U1") (pin "7") (pinfunction "Y7_7") (pintype "bidirectional"))
    )
    (net (code "278") (name "unconnected-(U5-~{DCD}-Pad8)") (class "Default")
      (node (ref "U5") (pin "8") (pinfunction "~{DCD}_8") (pintype "input"))
    )
    (net (code "279") (name "unconnected-(U5-~{DSR}-Pad7)") (class "Default")
      (node (ref "U5") (pin "7") (pinfunction "~{DSR}_7") (pintype "input"))
    )
    (net (code "280") (name "unconnected-(U11-XTAL2-Pad16)") (class "Default")
      (node (ref "U11") (pin "16") (pinfunction "XTAL2_16") (pintype "bidirectional"))
    )
    (net (code "281") (name "unconnected-(U11-~{CTS}-Pad11)") (class "Default")
      (node (ref "U11") (pin "11") (pinfunction "~{CTS}_11") (pintype "bidirectional"))
    )
    (net (code "282") (name "unconnected-(U11-~{RTS}-Pad10)") (class "Default")
      (node (ref "U11") (pin "10") (pinfunction "~{RTS}_10") (pintype "bidirectional"))
    )
    (net (code "283") (name "unconnected-(U15-D4-Pad7)") (class "Default")
      (node (ref "U15") (pin "7") (pinfunction "D4_7") (pintype "bidirectional"))
    )
    (net (code "284") (name "unconnected-(U15-S4-Pad6)") (class "Default")
      (node (ref "U15") (pin "6") (pinfunction "S4_6") (pintype "bidirectional"))
    )
    (net (code "285") (name "~{IRQ}") (class "Default")
      (node (ref "J37") (pin "4") (pinfunction "4_4") (pintype "passive"))
      (node (ref "J37A") (pin "4") (pinfunction "4_4") (pintype "passive"))
      (node (ref "R58") (pin "2") (pinfunction "2_2") (pintype "passive"))
      (node (ref "R82") (pin "1") (pinfunction "1_1") (pintype "passive"))
      (node (ref "U11") (pin "7") (pinfunction "~{IRQ}_7") (pintype "bidirectional"))
    )
    (net (code "286") (name "~{LCD_BACKLIGHT}") (class "Default")
      (node (ref "MD1") (pin "~14") (pinfunction "14_~14") (pintype "bidirectional"))
      (node (ref "U2") (pin "4") (pinfunction "~{SHDN}_4") (pintype "bidirectional"))
    )
  )
)
